# MDCBoard.net
KiCad netlist of a schematic drawn in EAGLE
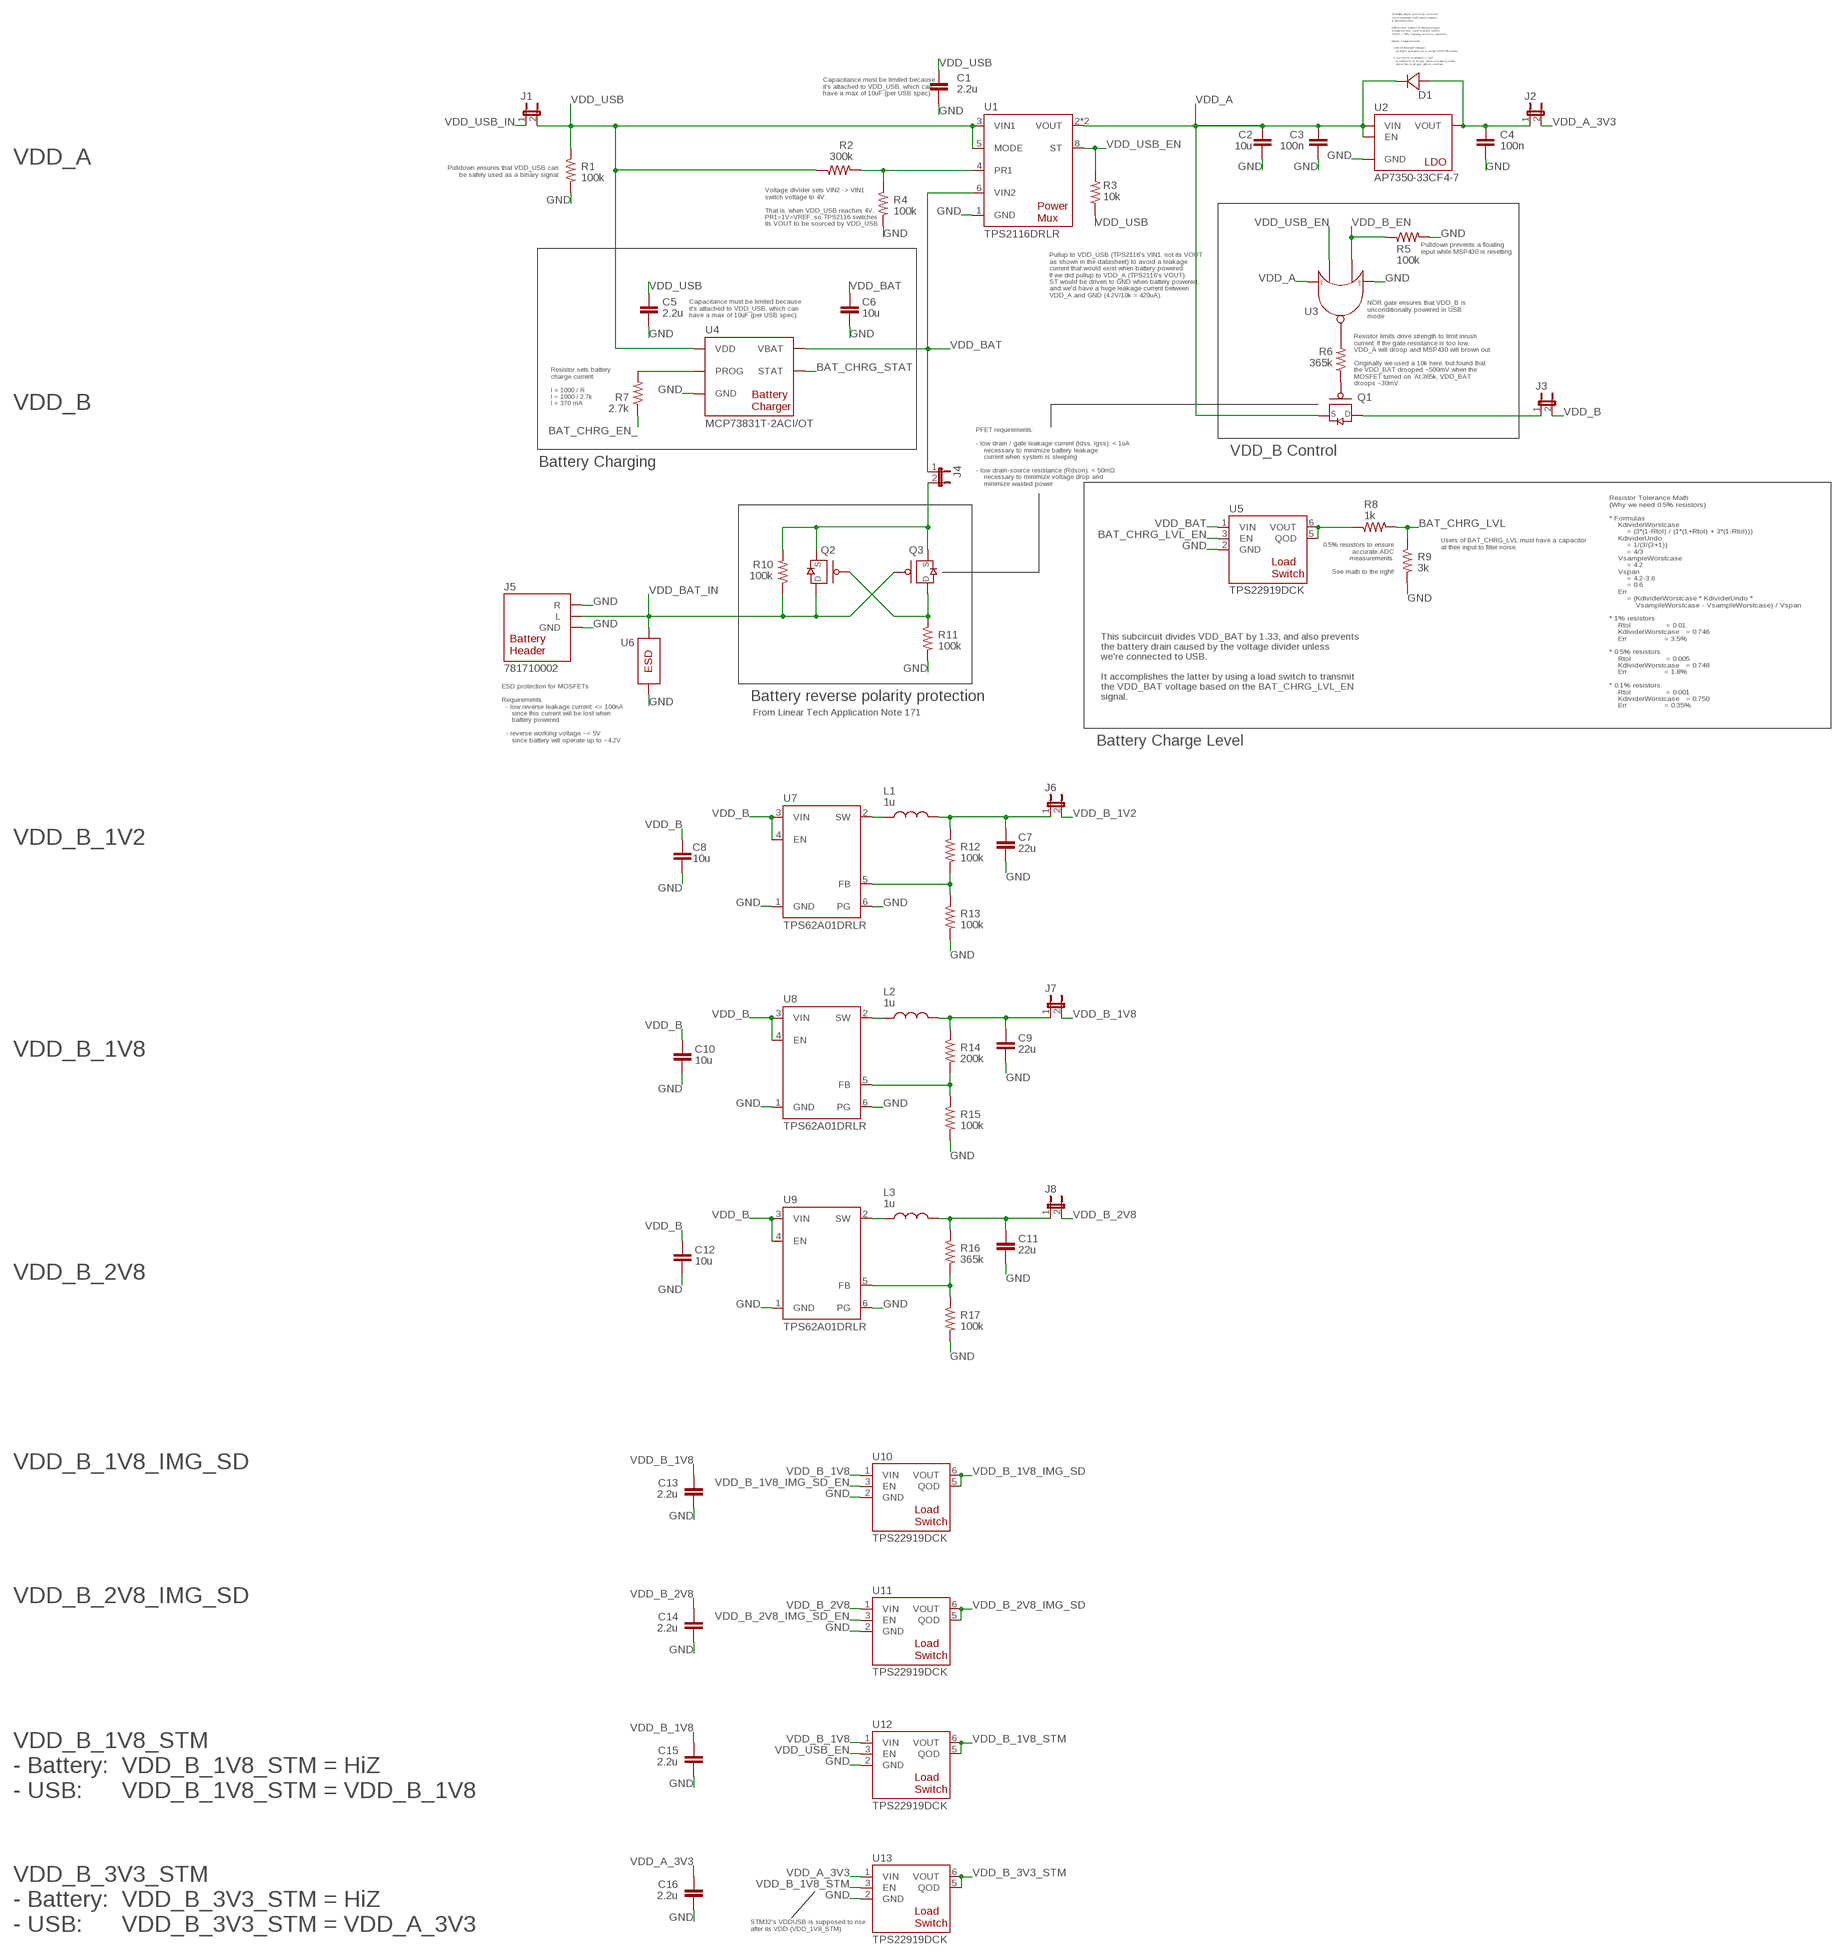
[diagram p0: schematic, sheet 1]
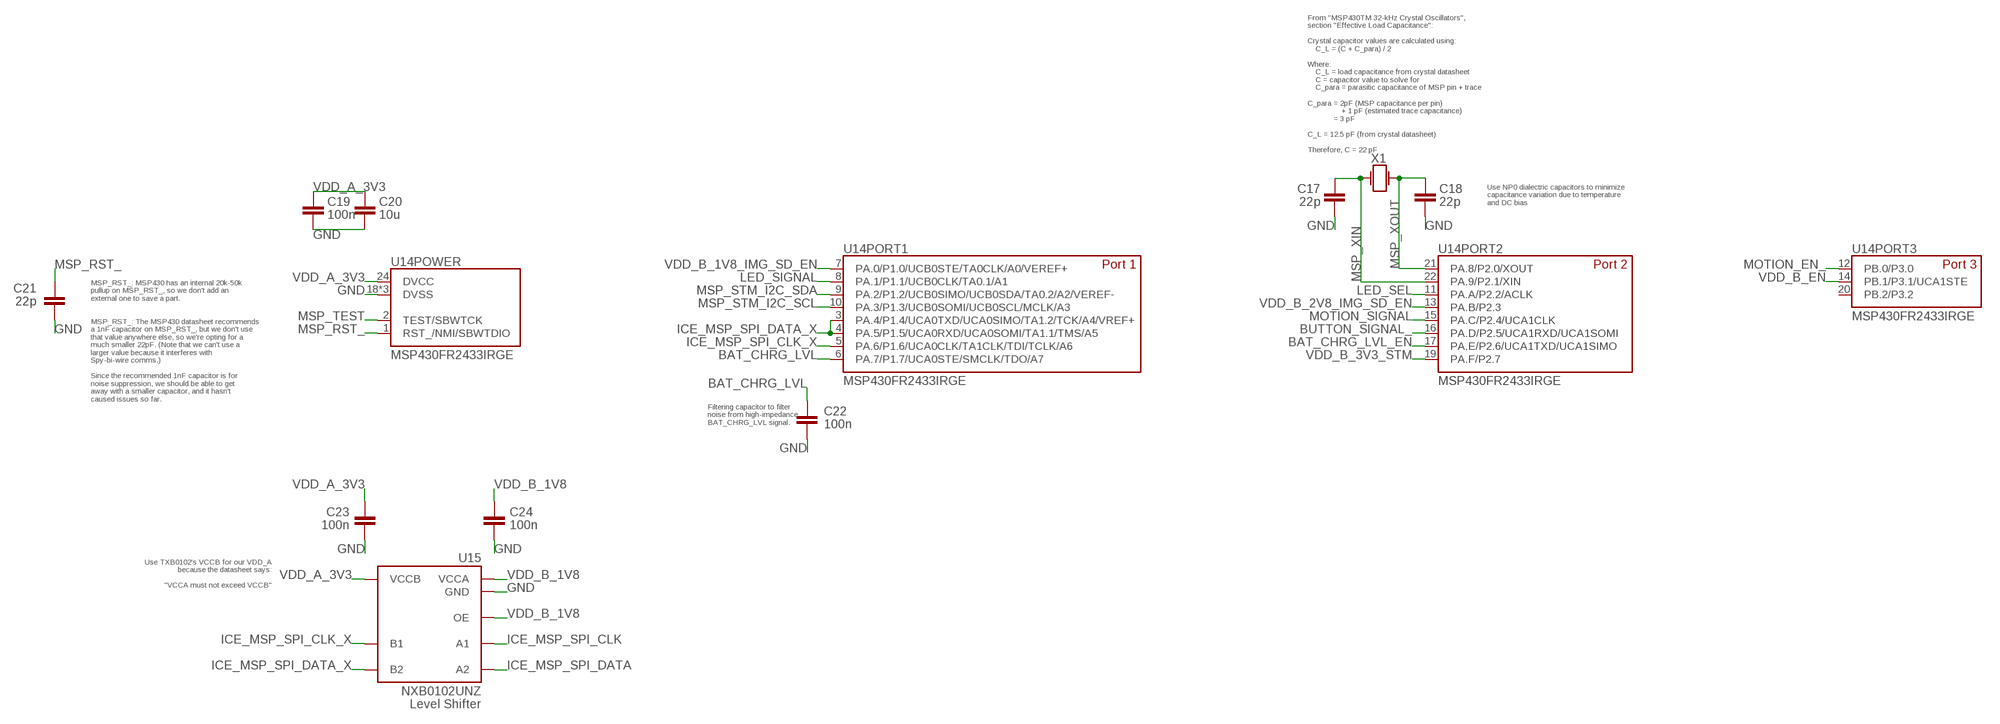
[diagram p1: schematic, sheet 2]
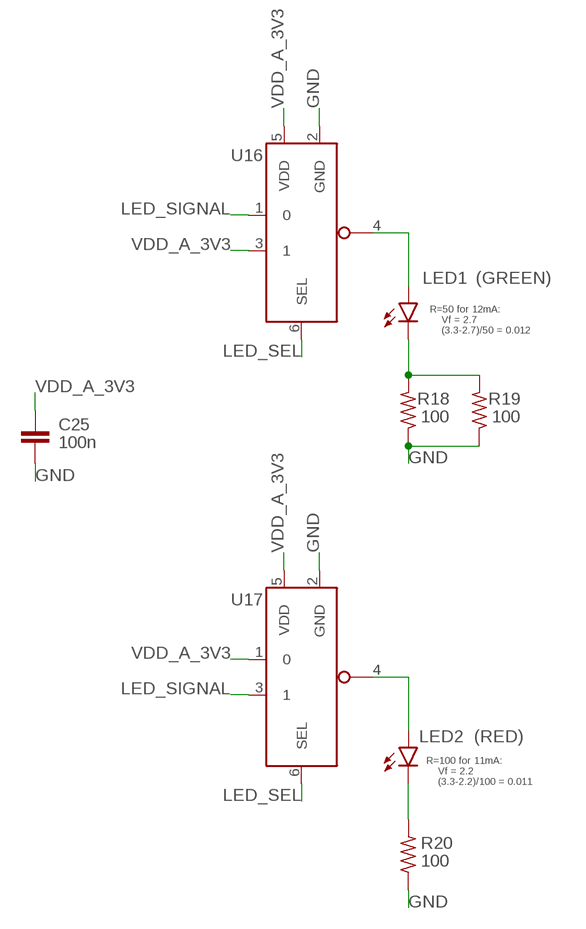
[diagram p2: schematic, sheet 3]
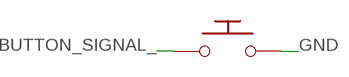
[diagram p3: schematic, sheet 4]
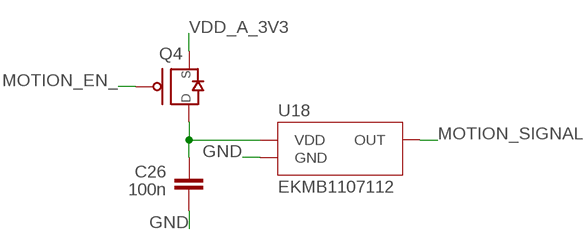
[diagram p4: schematic, sheet 5]
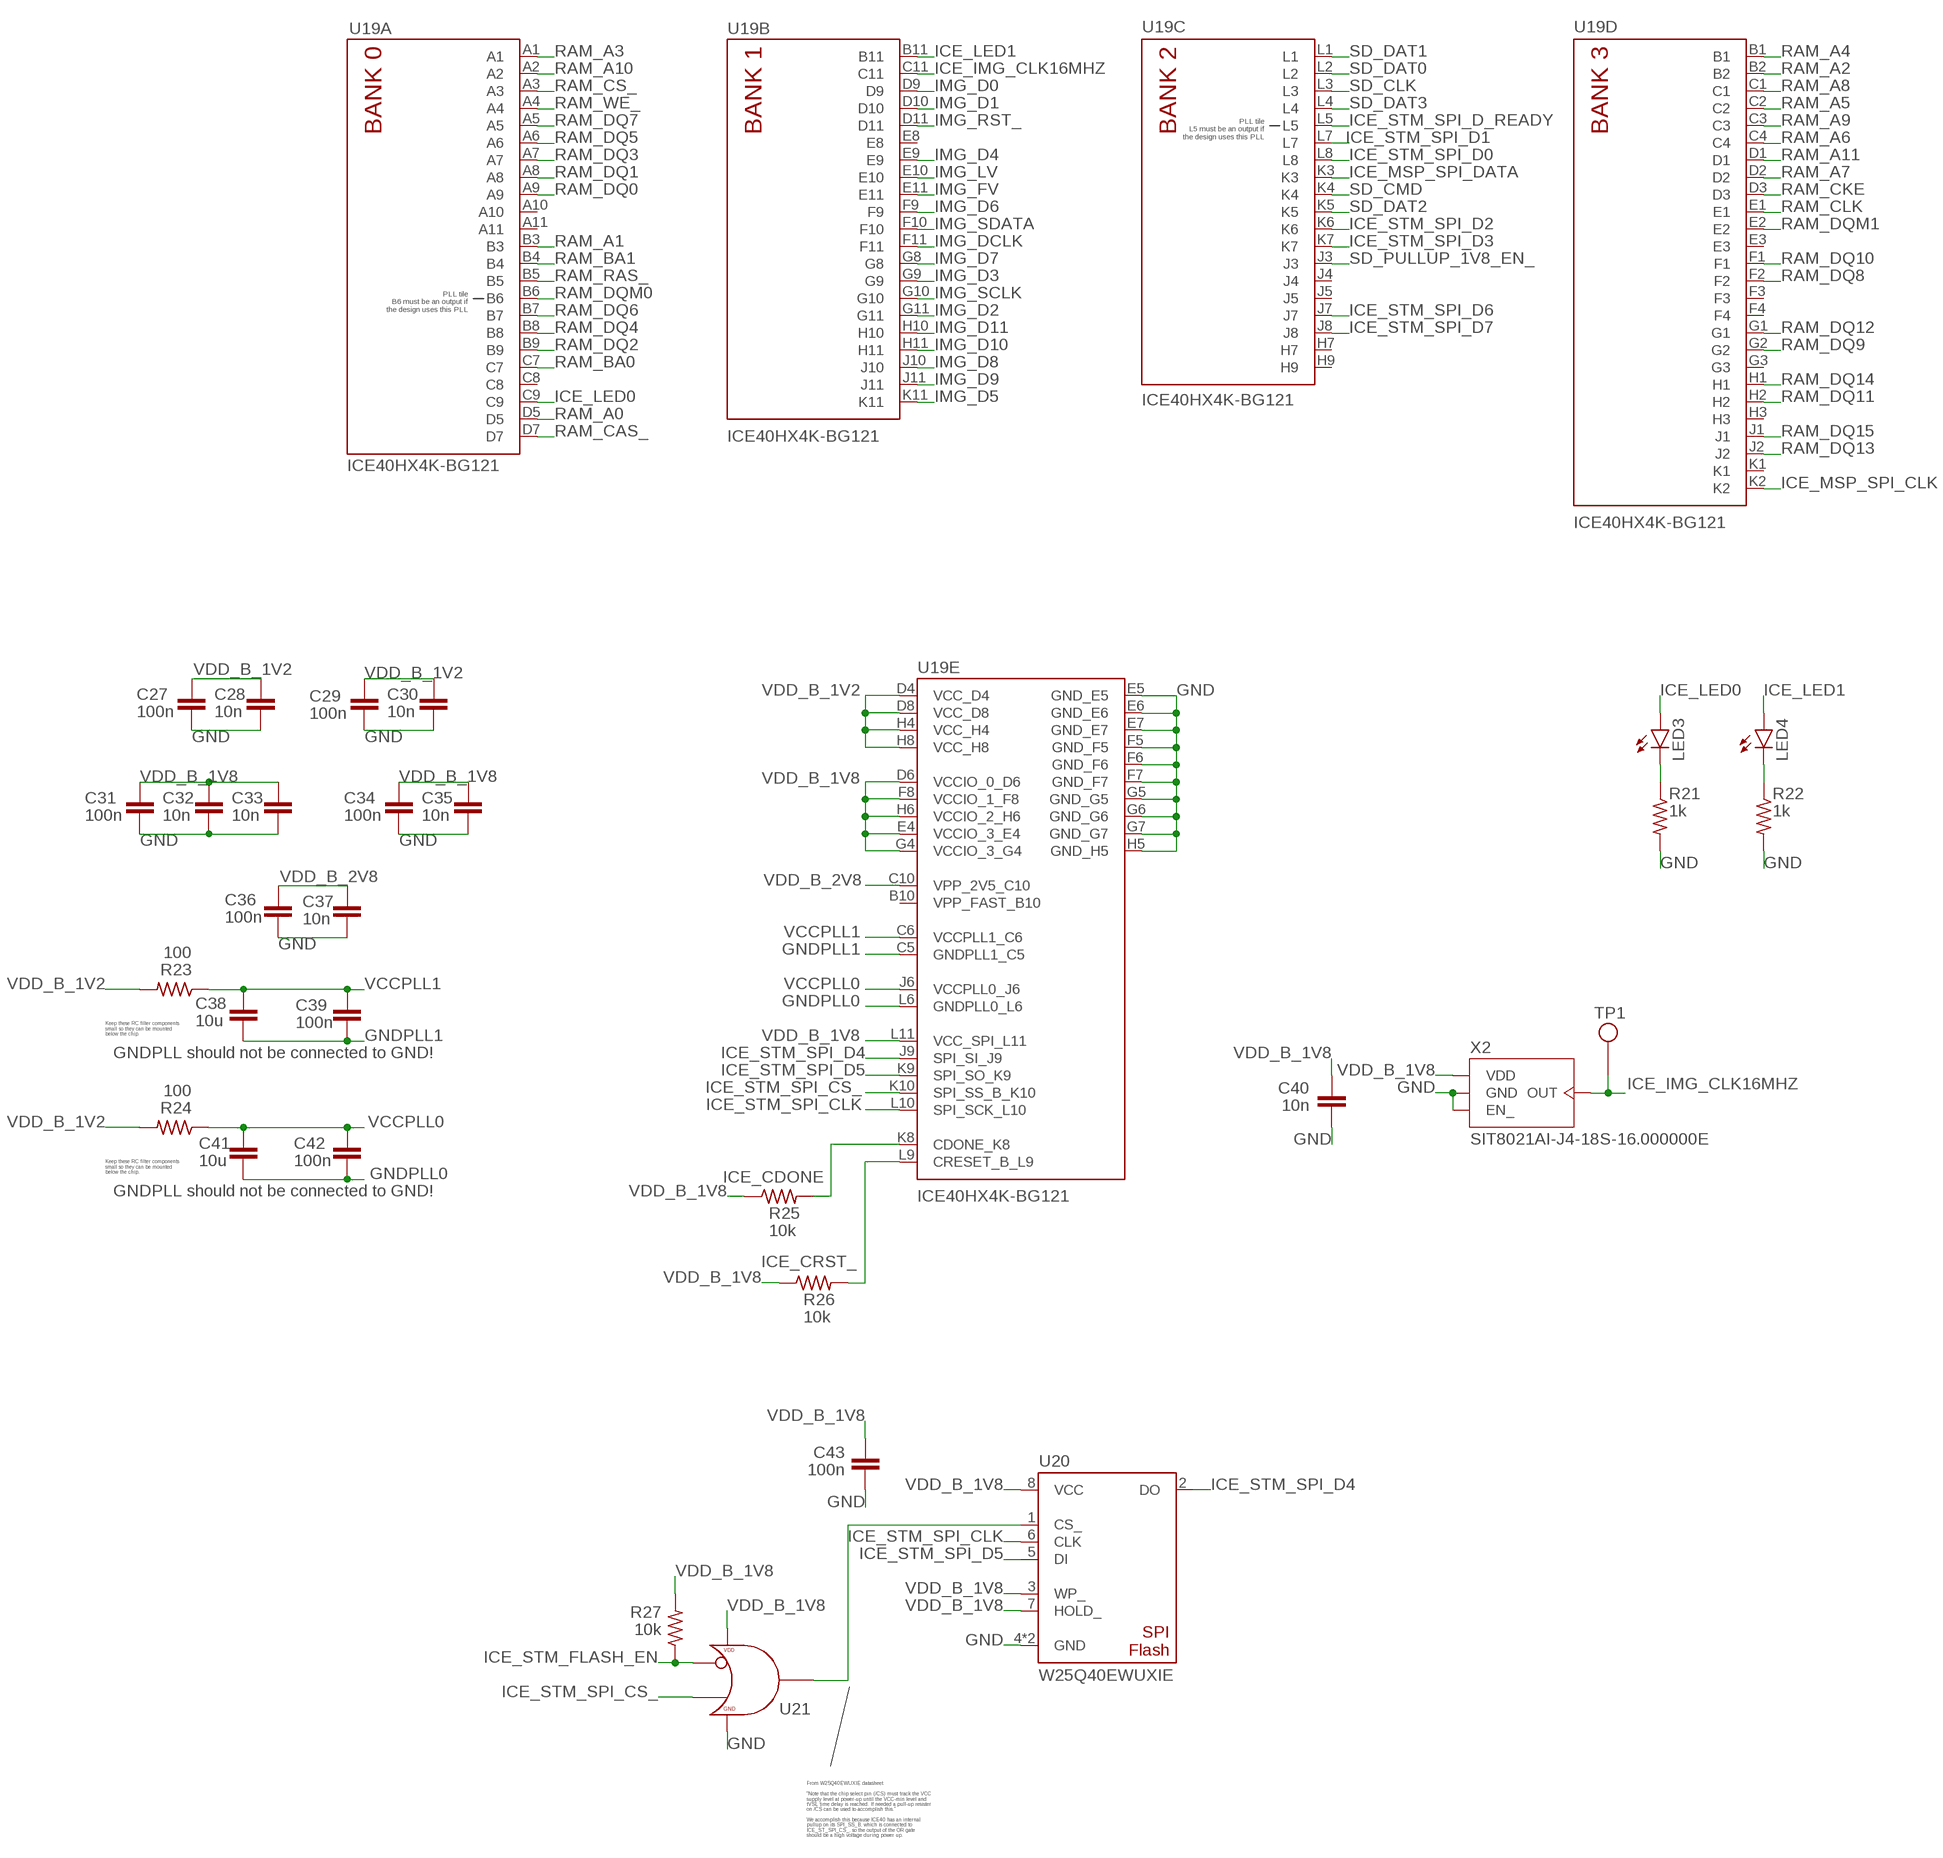
[diagram p5: schematic, sheet 6]
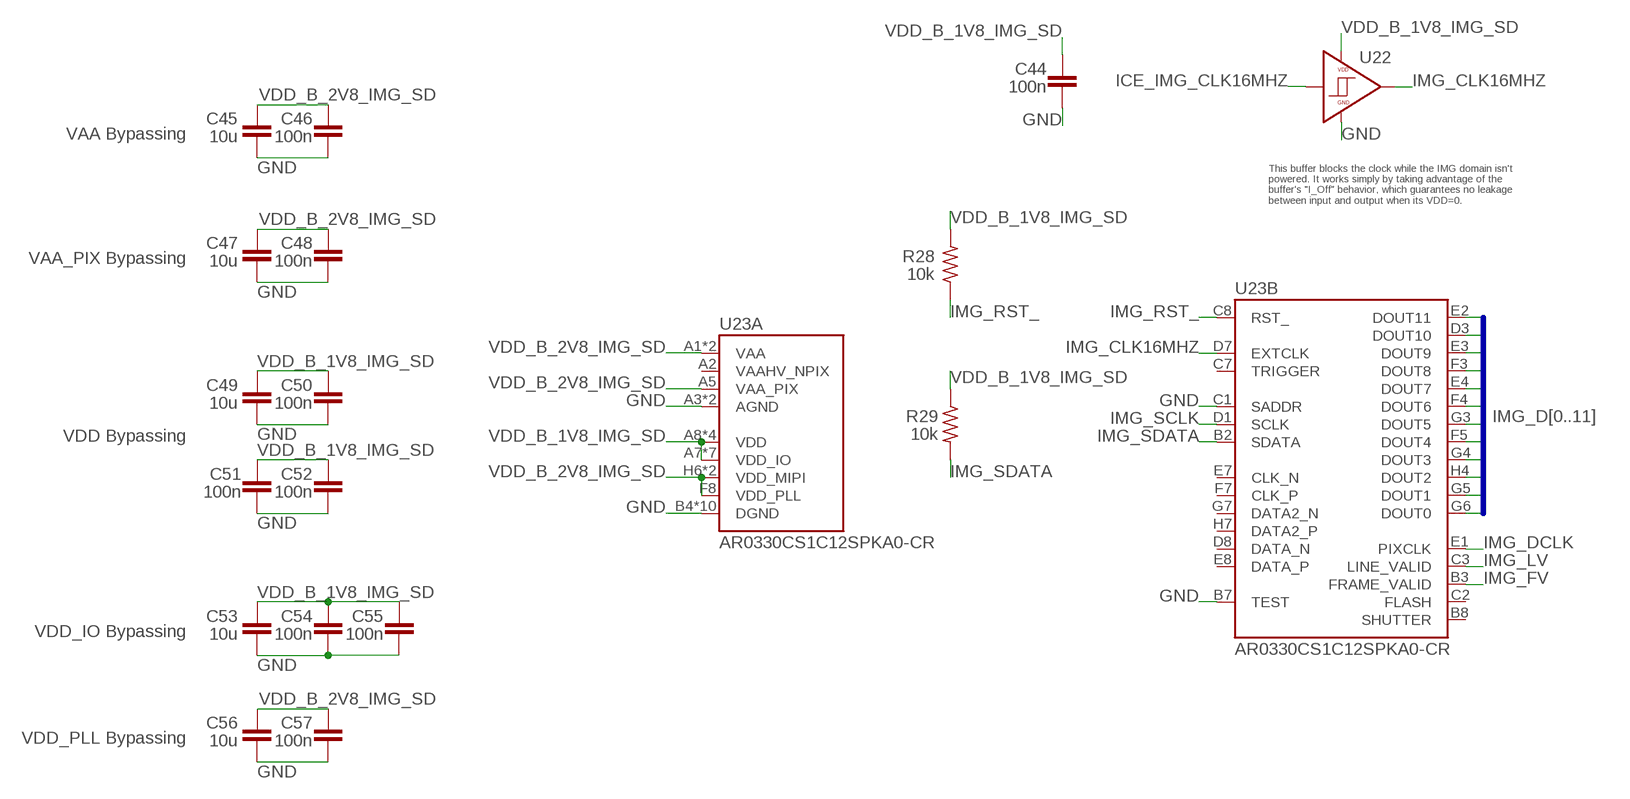
[diagram p6: schematic, sheet 7]
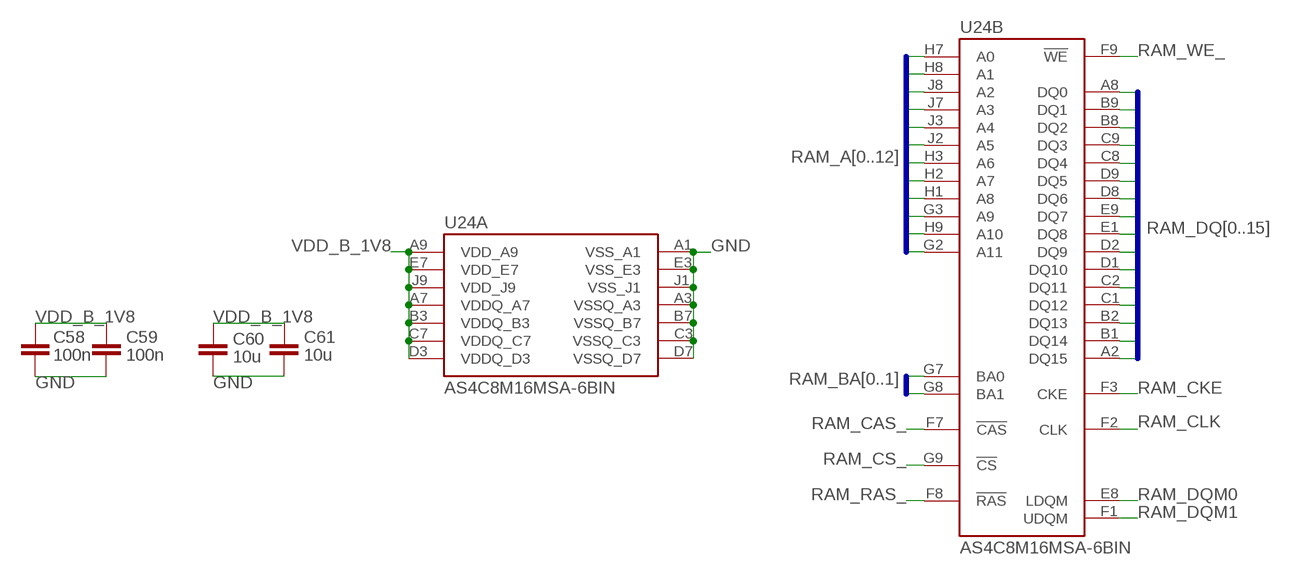
[diagram p7: schematic, sheet 8]
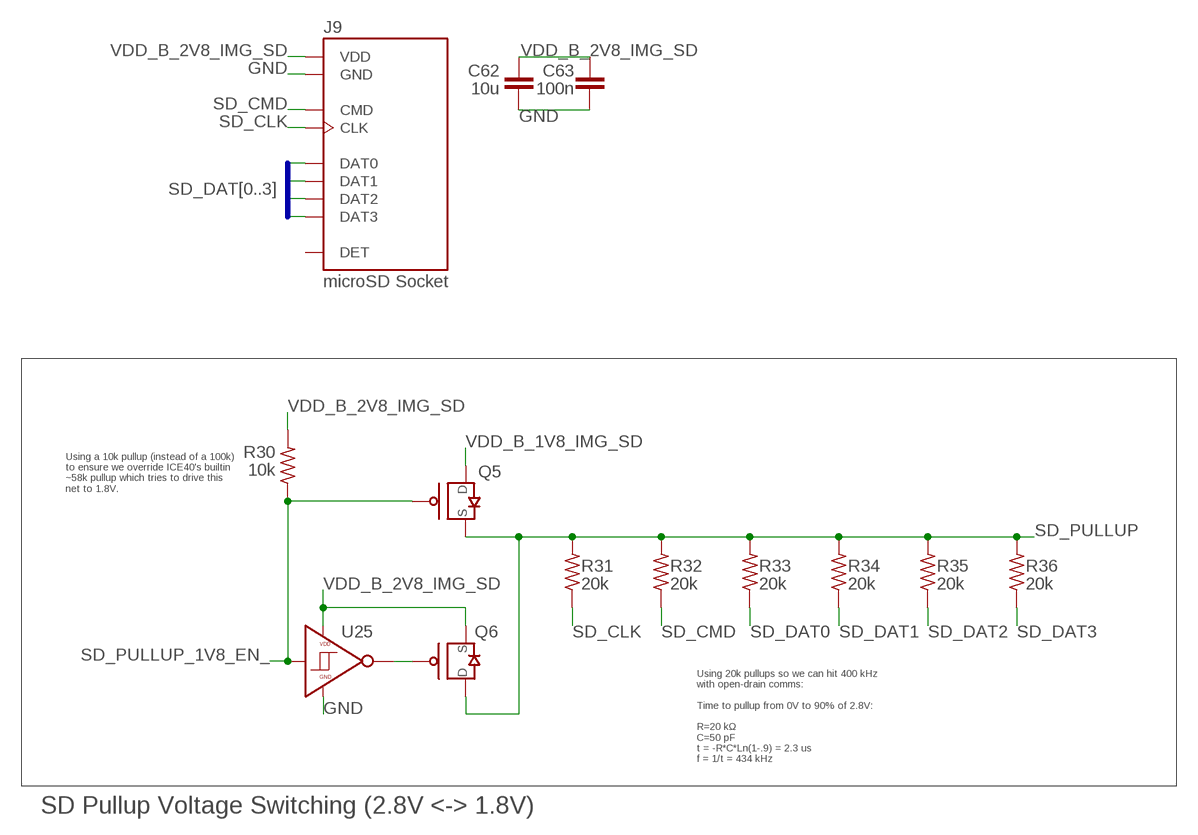
[diagram p8: schematic, sheet 9]
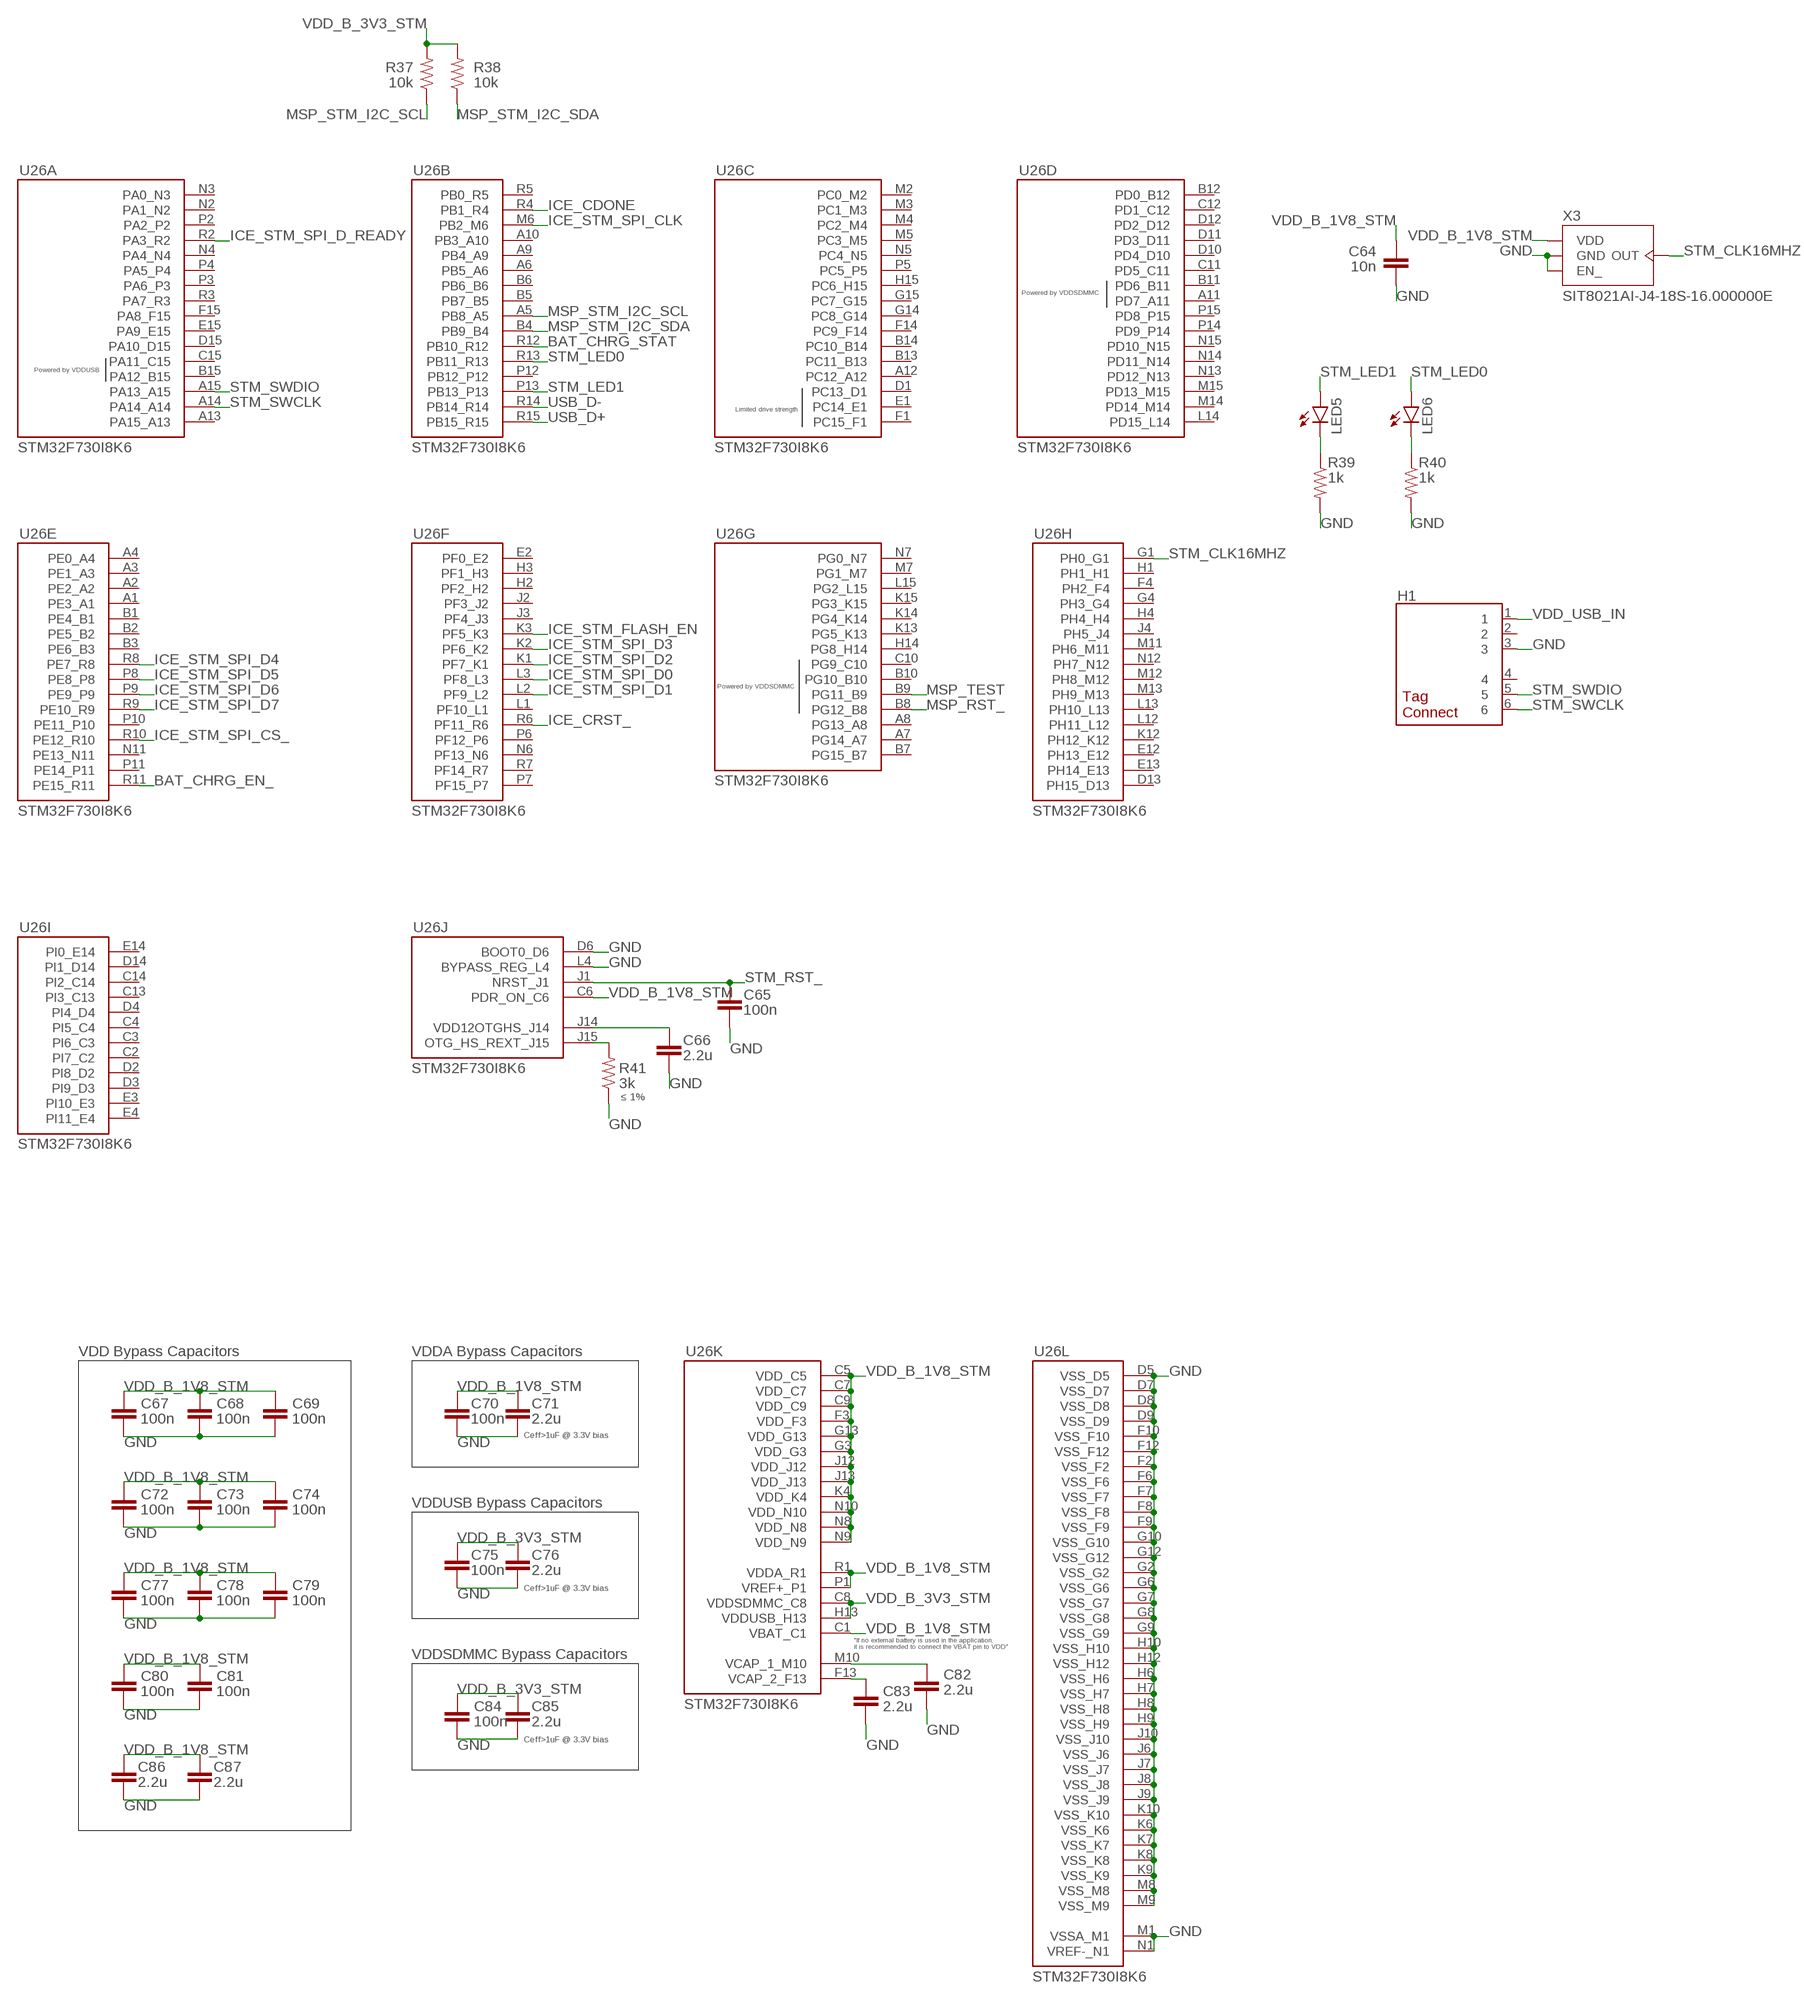
[diagram p9: schematic, sheet 10]
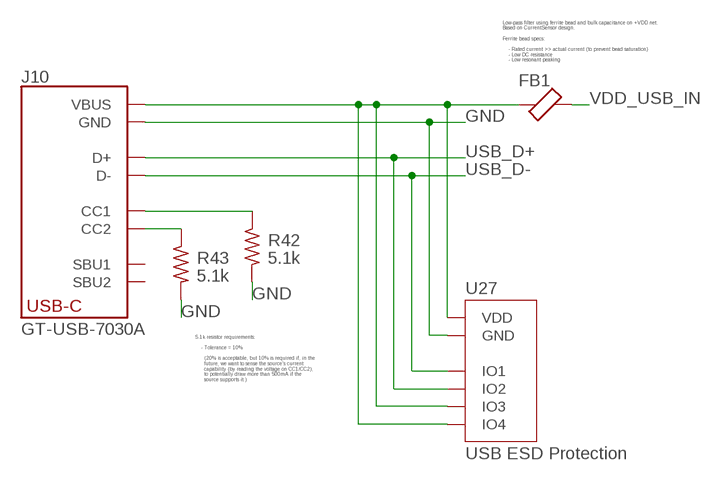
[diagram p10: schematic, sheet 11]
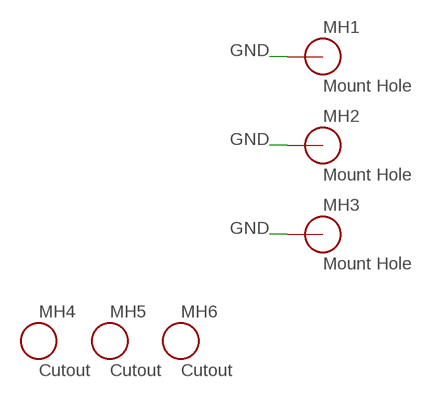
[diagram p11: schematic, sheet 12]

(export (version "E")
  (design (tool "Eeschema 10.0.6"))
  (components
    (comp (ref "C25")
      (value "100n")
      (footprint "eagle-import:0402")
      (fields (field (name "MFG") "Murata"))
      (libsource (lib "eagle-import") (part "CAPACITOR0402"))
    )
    (comp (ref "LED1")
      (value "LEDOSRAM-TOPLED-E1608")
      (footprint "eagle-import:OSRAM-TOPLED-E1608")
      (fields (field (name "MFG") "OSRAM"))
      (libsource (lib "eagle-import") (part "LEDOSRAM-TOPLED-E1608"))
    )
    (comp (ref "LED2")
      (value "LEDOSRAM-TOPLED-E1608")
      (footprint "eagle-import:OSRAM-TOPLED-E1608")
      (fields (field (name "MFG") "OSRAM"))
      (libsource (lib "eagle-import") (part "LEDOSRAM-TOPLED-E1608"))
    )
    (comp (ref "R18")
      (value "100")
      (footprint "eagle-import:0402")
      (fields (field (name "MFG") "Walsin"))
      (libsource (lib "eagle-import") (part "RESISTOR0402"))
    )
    (comp (ref "R19")
      (value "100")
      (footprint "eagle-import:0402")
      (fields (field (name "MFG") "Walsin"))
      (libsource (lib "eagle-import") (part "RESISTOR0402"))
    )
    (comp (ref "R20")
      (value "100")
      (footprint "eagle-import:0402")
      (fields (field (name "MFG") "Walsin"))
      (libsource (lib "eagle-import") (part "RESISTOR0402"))
    )
    (comp (ref "U16")
      (value "NEXPERIA-74LVC1G98-MUX-INV-OUTPUT")
      (footprint "eagle-import:NEXPERIA-SOT363")
      (fields (field (name "MFG") "Nexperia"))
      (libsource (lib "eagle-import") (part "NEXPERIA-74LVC1G98-MUX-INV-OUTPUT"))
    )
    (comp (ref "U17")
      (value "NEXPERIA-74LVC1G98-MUX-INV-OUTPUT")
      (footprint "eagle-import:NEXPERIA-SOT363")
      (fields (field (name "MFG") "Nexperia"))
      (libsource (lib "eagle-import") (part "NEXPERIA-74LVC1G98-MUX-INV-OUTPUT"))
    )
    (comp (ref "FB1")
      (value "FERRITE-BEAD0402")
      (footprint "eagle-import:0402")
      (fields (field (name "MFG") "Taiyo Yuden"))
      (libsource (lib "eagle-import") (part "FERRITE-BEAD0402"))
    )
    (comp (ref "J10")
      (value "USB-C-RECEPTACLE-GSWITCH-7030A")
      (footprint "eagle-import:GSWITCH-GT-USB-7030A")
      (fields (field (name "PN") "GT-USB-7030A") (field (name "MFG") "G-Switch"))
      (libsource (lib "eagle-import") (part "USB-C-RECEPTACLE-GSWITCH-7030A"))
    )
    (comp (ref "R42")
      (value "5.1k")
      (footprint "eagle-import:0402")
      (fields (field (name "MFG") "Yageo"))
      (libsource (lib "eagle-import") (part "RESISTOR0402"))
    )
    (comp (ref "R43")
      (value "5.1k")
      (footprint "eagle-import:0402")
      (fields (field (name "MFG") "Yageo"))
      (libsource (lib "eagle-import") (part "RESISTOR0402"))
    )
    (comp (ref "U27")
      (value "DIODESINC-DT1446-04V-7")
      (footprint "eagle-import:DIODESINC-DT1446-04V-7")
      (fields (field (name "MFG") "Diodes Incorporated"))
      (libsource (lib "eagle-import") (part "DIODESINC-DT1446-04V-7"))
    )
    (comp (ref "C64")
      (value "10n")
      (footprint "eagle-import:0402")
      (fields (field (name "MFG") "Samsung"))
      (libsource (lib "eagle-import") (part "CAPACITOR0402"))
    )
    (comp (ref "C65")
      (value "100n")
      (footprint "eagle-import:0402")
      (fields (field (name "MFG") "Murata"))
      (libsource (lib "eagle-import") (part "CAPACITOR0402"))
    )
    (comp (ref "C66")
      (value "2.2u")
      (footprint "eagle-import:0402")
      (fields (field (name "MFG") "Taiyo Yuden"))
      (libsource (lib "eagle-import") (part "CAPACITOR0402"))
    )
    (comp (ref "C67")
      (value "100n")
      (footprint "eagle-import:0402")
      (fields (field (name "MFG") "Murata"))
      (libsource (lib "eagle-import") (part "CAPACITOR0402"))
    )
    (comp (ref "C68")
      (value "100n")
      (footprint "eagle-import:0402")
      (fields (field (name "MFG") "Murata"))
      (libsource (lib "eagle-import") (part "CAPACITOR0402"))
    )
    (comp (ref "C69")
      (value "100n")
      (footprint "eagle-import:0402")
      (fields (field (name "MFG") "Murata"))
      (libsource (lib "eagle-import") (part "CAPACITOR0402"))
    )
    (comp (ref "C70")
      (value "100n")
      (footprint "eagle-import:0402")
      (fields (field (name "MFG") "Murata"))
      (libsource (lib "eagle-import") (part "CAPACITOR0402"))
    )
    (comp (ref "C71")
      (value "2.2u")
      (footprint "eagle-import:0402")
      (fields (field (name "MFG") "Taiyo Yuden"))
      (libsource (lib "eagle-import") (part "CAPACITOR0402"))
    )
    (comp (ref "C72")
      (value "100n")
      (footprint "eagle-import:0402")
      (fields (field (name "MFG") "Murata"))
      (libsource (lib "eagle-import") (part "CAPACITOR0402"))
    )
    (comp (ref "C73")
      (value "100n")
      (footprint "eagle-import:0402")
      (fields (field (name "MFG") "Murata"))
      (libsource (lib "eagle-import") (part "CAPACITOR0402"))
    )
    (comp (ref "C74")
      (value "100n")
      (footprint "eagle-import:0402")
      (fields (field (name "MFG") "Murata"))
      (libsource (lib "eagle-import") (part "CAPACITOR0402"))
    )
    (comp (ref "C75")
      (value "100n")
      (footprint "eagle-import:0402")
      (fields (field (name "MFG") "Murata"))
      (libsource (lib "eagle-import") (part "CAPACITOR0402"))
    )
    (comp (ref "C76")
      (value "2.2u")
      (footprint "eagle-import:0402")
      (fields (field (name "MFG") "Taiyo Yuden"))
      (libsource (lib "eagle-import") (part "CAPACITOR0402"))
    )
    (comp (ref "C77")
      (value "100n")
      (footprint "eagle-import:0402")
      (fields (field (name "MFG") "Murata"))
      (libsource (lib "eagle-import") (part "CAPACITOR0402"))
    )
    (comp (ref "C78")
      (value "100n")
      (footprint "eagle-import:0402")
      (fields (field (name "MFG") "Murata"))
      (libsource (lib "eagle-import") (part "CAPACITOR0402"))
    )
    (comp (ref "C79")
      (value "100n")
      (footprint "eagle-import:0402")
      (fields (field (name "MFG") "Murata"))
      (libsource (lib "eagle-import") (part "CAPACITOR0402"))
    )
    (comp (ref "C80")
      (value "100n")
      (footprint "eagle-import:0402")
      (fields (field (name "MFG") "Murata"))
      (libsource (lib "eagle-import") (part "CAPACITOR0402"))
    )
    (comp (ref "C81")
      (value "100n")
      (footprint "eagle-import:0402")
      (fields (field (name "MFG") "Murata"))
      (libsource (lib "eagle-import") (part "CAPACITOR0402"))
    )
    (comp (ref "C82")
      (value "2.2u")
      (footprint "eagle-import:0402")
      (fields (field (name "MFG") "Taiyo Yuden"))
      (libsource (lib "eagle-import") (part "CAPACITOR0402"))
    )
    (comp (ref "C83")
      (value "2.2u")
      (footprint "eagle-import:0402")
      (fields (field (name "MFG") "Taiyo Yuden"))
      (libsource (lib "eagle-import") (part "CAPACITOR0402"))
    )
    (comp (ref "C84")
      (value "100n")
      (footprint "eagle-import:0402")
      (fields (field (name "MFG") "Murata"))
      (libsource (lib "eagle-import") (part "CAPACITOR0402"))
    )
    (comp (ref "C85")
      (value "2.2u")
      (footprint "eagle-import:0402")
      (fields (field (name "MFG") "Taiyo Yuden"))
      (libsource (lib "eagle-import") (part "CAPACITOR0402"))
    )
    (comp (ref "C86")
      (value "2.2u")
      (footprint "eagle-import:0402")
      (fields (field (name "MFG") "Taiyo Yuden"))
      (libsource (lib "eagle-import") (part "CAPACITOR0402"))
    )
    (comp (ref "C87")
      (value "2.2u")
      (footprint "eagle-import:0402")
      (fields (field (name "MFG") "Taiyo Yuden"))
      (libsource (lib "eagle-import") (part "CAPACITOR0402"))
    )
    (comp (ref "H1")
      (value "TAGCONNECT-TC2030-NL")
      (footprint "eagle-import:TAGCONNECT-TC2030-NL")
      (libsource (lib "eagle-import") (part "TAGCONNECT-TC2030-NL"))
    )
    (comp (ref "LED5")
      (value "LEDLED-0603")
      (footprint "eagle-import:LED-0603")
      (fields (field (name "MFG") "OSRAM"))
      (libsource (lib "eagle-import") (part "LEDLED-0603"))
    )
    (comp (ref "LED6")
      (value "LEDLED-0603")
      (footprint "eagle-import:LED-0603")
      (fields (field (name "MFG") "OSRAM"))
      (libsource (lib "eagle-import") (part "LEDLED-0603"))
    )
    (comp (ref "R37")
      (value "10k")
      (footprint "eagle-import:0402")
      (fields (field (name "MFG") "Yageo"))
      (libsource (lib "eagle-import") (part "RESISTOR0402"))
    )
    (comp (ref "R38")
      (value "10k")
      (footprint "eagle-import:0402")
      (fields (field (name "MFG") "Yageo"))
      (libsource (lib "eagle-import") (part "RESISTOR0402"))
    )
    (comp (ref "R39")
      (value "1k")
      (footprint "eagle-import:0402")
      (fields (field (name "MFG") "Kamaya"))
      (libsource (lib "eagle-import") (part "RESISTOR0402"))
    )
    (comp (ref "R40")
      (value "1k")
      (footprint "eagle-import:0402")
      (fields (field (name "MFG") "Kamaya"))
      (libsource (lib "eagle-import") (part "RESISTOR0402"))
    )
    (comp (ref "R41")
      (value "3k")
      (footprint "eagle-import:0402")
      (fields (field (name "MFG") "Susumu"))
      (libsource (lib "eagle-import") (part "RESISTOR0402"))
    )
    (comp (ref "U26")
      (value "STM-STM32F730")
      (footprint "eagle-import:STM-STM32F730I8")
      (fields (field (name "MFG") "STMicroelectronics") (field (name "PN") "STM32F730I8K6"))
      (libsource (lib "eagle-import") (part "STM-STM32F730"))
    )
    (comp (ref "X3")
      (value "SITIME-SIT8021")
      (footprint "eagle-import:SITIME-SIT8021")
      (fields (field (name "MFG") "SiTime") (field (name "PN") "SIT8021AI-J4-18S-16.000000E"))
      (libsource (lib "eagle-import") (part "SITIME-SIT8021"))
    )
    (comp (ref "SW1")
      (value "TACTILE-SWITCH")
      (footprint "eagle-import:DEALON-TD-1624UR-180")
      (fields (field (name "MFG") "SHOU HAN"))
      (libsource (lib "eagle-import") (part "TACTILE-SWITCH"))
    )
    (comp (ref "C62")
      (value "10u")
      (footprint "eagle-import:0805")
      (fields (field (name "MFG") "Samsung"))
      (libsource (lib "eagle-import") (part "CAPACITOR0805"))
    )
    (comp (ref "C63")
      (value "100n")
      (footprint "eagle-import:0402")
      (fields (field (name "MFG") "Murata"))
      (libsource (lib "eagle-import") (part "CAPACITOR0402"))
    )
    (comp (ref "J9")
      (value "MICROSD-SOCKET")
      (footprint "eagle-import:MOLEX-1051620001")
      (fields (field (name "MFG") "Molex"))
      (libsource (lib "eagle-import") (part "MICROSD-SOCKET"))
    )
    (comp (ref "Q5")
      (value "DIODESINC-DMG2305UX")
      (footprint "eagle-import:DIODESINC-DMG2305UX")
      (fields (field (name "MFG") "Diodes Incorporated"))
      (libsource (lib "eagle-import") (part "DIODESINC-DMG2305UX"))
    )
    (comp (ref "Q6")
      (value "DIODESINC-DMG2305UX")
      (footprint "eagle-import:DIODESINC-DMG2305UX")
      (fields (field (name "MFG") "Diodes Incorporated"))
      (libsource (lib "eagle-import") (part "DIODESINC-DMG2305UX"))
    )
    (comp (ref "R30")
      (value "10k")
      (footprint "eagle-import:0402")
      (fields (field (name "MFG") "Yageo"))
      (libsource (lib "eagle-import") (part "RESISTOR0402"))
    )
    (comp (ref "R31")
      (value "20k")
      (footprint "eagle-import:0402")
      (fields (field (name "MFG") "Walsin"))
      (libsource (lib "eagle-import") (part "RESISTOR0402"))
    )
    (comp (ref "R32")
      (value "20k")
      (footprint "eagle-import:0402")
      (fields (field (name "MFG") "Walsin"))
      (libsource (lib "eagle-import") (part "RESISTOR0402"))
    )
    (comp (ref "R33")
      (value "20k")
      (footprint "eagle-import:0402")
      (fields (field (name "MFG") "Walsin"))
      (libsource (lib "eagle-import") (part "RESISTOR0402"))
    )
    (comp (ref "R34")
      (value "20k")
      (footprint "eagle-import:0402")
      (fields (field (name "MFG") "Walsin"))
      (libsource (lib "eagle-import") (part "RESISTOR0402"))
    )
    (comp (ref "R35")
      (value "20k")
      (footprint "eagle-import:0402")
      (fields (field (name "MFG") "Walsin"))
      (libsource (lib "eagle-import") (part "RESISTOR0402"))
    )
    (comp (ref "R36")
      (value "20k")
      (footprint "eagle-import:0402")
      (fields (field (name "MFG") "Walsin"))
      (libsource (lib "eagle-import") (part "RESISTOR0402"))
    )
    (comp (ref "U25")
      (value "NEXPERIA-74LVC1G98-INVERTER")
      (footprint "eagle-import:NEXPERIA-SOT363")
      (fields (field (name "MFG") "Nexperia"))
      (libsource (lib "eagle-import") (part "NEXPERIA-74LVC1G98-INVERTER"))
    )
    (comp (ref "C26")
      (value "100n")
      (footprint "eagle-import:0402")
      (fields (field (name "MFG") "Murata"))
      (libsource (lib "eagle-import") (part "CAPACITOR0402"))
    )
    (comp (ref "Q4")
      (value "DIODESINC-DMG2305UX")
      (footprint "eagle-import:DIODESINC-DMG2305UX")
      (fields (field (name "MFG") "Diodes Incorporated"))
      (libsource (lib "eagle-import") (part "DIODESINC-DMG2305UX"))
    )
    (comp (ref "U18")
      (value "PANASONIC-EKMB110711X")
      (footprint "eagle-import:PANASONIC-EKMB110711X")
      (fields (field (name "MFG") "Panasonic") (field (name "PN") "EKMB1107112"))
      (libsource (lib "eagle-import") (part "PANASONIC-EKMB110711X"))
    )
    (comp (ref "C58")
      (value "100n")
      (footprint "eagle-import:0402")
      (fields (field (name "MFG") "Murata"))
      (libsource (lib "eagle-import") (part "CAPACITOR0402"))
    )
    (comp (ref "C59")
      (value "100n")
      (footprint "eagle-import:0402")
      (fields (field (name "MFG") "Murata"))
      (libsource (lib "eagle-import") (part "CAPACITOR0402"))
    )
    (comp (ref "C60")
      (value "10u")
      (footprint "eagle-import:0805")
      (fields (field (name "MFG") "Samsung"))
      (libsource (lib "eagle-import") (part "CAPACITOR0805"))
    )
    (comp (ref "C61")
      (value "10u")
      (footprint "eagle-import:0805")
      (fields (field (name "MFG") "Samsung"))
      (libsource (lib "eagle-import") (part "CAPACITOR0805"))
    )
    (comp (ref "U24")
      (value "ALLIANCE-AS4C8M16MSA-6BIN")
      (footprint "eagle-import:ALLIANCE-AS4C8M16MSA-6BIN")
      (fields (field (name "PN") "AS4C8M16MSA-6BIN") (field (name "MFG") "Alliance Memory"))
      (libsource (lib "eagle-import") (part "ALLIANCE-AS4C8M16MSA-6BIN"))
    )
    (comp (ref "C1")
      (value "2.2u")
      (footprint "eagle-import:0402")
      (fields (field (name "MFG") "Taiyo Yuden"))
      (libsource (lib "eagle-import") (part "CAPACITOR0402"))
    )
    (comp (ref "C2")
      (value "10u")
      (footprint "eagle-import:0805")
      (fields (field (name "MFG") "Samsung"))
      (libsource (lib "eagle-import") (part "CAPACITOR0805"))
    )
    (comp (ref "C3")
      (value "100n")
      (footprint "eagle-import:0402")
      (fields (field (name "MFG") "Murata"))
      (libsource (lib "eagle-import") (part "CAPACITOR0402"))
    )
    (comp (ref "C4")
      (value "100n")
      (footprint "eagle-import:0402")
      (fields (field (name "MFG") "Murata"))
      (libsource (lib "eagle-import") (part "CAPACITOR0402"))
    )
    (comp (ref "C5")
      (value "2.2u")
      (footprint "eagle-import:0402")
      (fields (field (name "MFG") "Taiyo Yuden"))
      (libsource (lib "eagle-import") (part "CAPACITOR0402"))
    )
    (comp (ref "C6")
      (value "10u")
      (footprint "eagle-import:0805")
      (fields (field (name "MFG") "Samsung"))
      (libsource (lib "eagle-import") (part "CAPACITOR0805"))
    )
    (comp (ref "C7")
      (value "22u")
      (footprint "eagle-import:0805")
      (fields (field (name "MFG") "Samsung"))
      (libsource (lib "eagle-import") (part "CAPACITOR0805"))
    )
    (comp (ref "C8")
      (value "10u")
      (footprint "eagle-import:0805")
      (fields (field (name "MFG") "Samsung"))
      (libsource (lib "eagle-import") (part "CAPACITOR0805"))
    )
    (comp (ref "C9")
      (value "22u")
      (footprint "eagle-import:0805")
      (fields (field (name "MFG") "Samsung"))
      (libsource (lib "eagle-import") (part "CAPACITOR0805"))
    )
    (comp (ref "C10")
      (value "10u")
      (footprint "eagle-import:0805")
      (fields (field (name "MFG") "Samsung"))
      (libsource (lib "eagle-import") (part "CAPACITOR0805"))
    )
    (comp (ref "C11")
      (value "22u")
      (footprint "eagle-import:0805")
      (fields (field (name "MFG") "Samsung"))
      (libsource (lib "eagle-import") (part "CAPACITOR0805"))
    )
    (comp (ref "C12")
      (value "10u")
      (footprint "eagle-import:0805")
      (fields (field (name "MFG") "Samsung"))
      (libsource (lib "eagle-import") (part "CAPACITOR0805"))
    )
    (comp (ref "C13")
      (value "2.2u")
      (footprint "eagle-import:0402")
      (fields (field (name "MFG") "Taiyo Yuden"))
      (libsource (lib "eagle-import") (part "CAPACITOR0402"))
    )
    (comp (ref "C14")
      (value "2.2u")
      (footprint "eagle-import:0402")
      (fields (field (name "MFG") "Taiyo Yuden"))
      (libsource (lib "eagle-import") (part "CAPACITOR0402"))
    )
    (comp (ref "C15")
      (value "2.2u")
      (footprint "eagle-import:0402")
      (fields (field (name "MFG") "Taiyo Yuden"))
      (libsource (lib "eagle-import") (part "CAPACITOR0402"))
    )
    (comp (ref "C16")
      (value "2.2u")
      (footprint "eagle-import:0402")
      (fields (field (name "MFG") "Taiyo Yuden"))
      (libsource (lib "eagle-import") (part "CAPACITOR0402"))
    )
    (comp (ref "D1")
      (value "ROHM-RB168MM-40")
      (footprint "eagle-import:ROHM-SOD-123FL")
      (fields (field (name "MFG") "ROHM"))
      (libsource (lib "eagle-import") (part "ROHM-RB168MM-40"))
    )
    (comp (ref "J1")
      (value "JUMPER-SOLDER-CLOSED")
      (footprint "eagle-import:JUMPER-SOLDER-CLOSED")
      (libsource (lib "eagle-import") (part "JUMPER-SOLDER-CLOSED"))
    )
    (comp (ref "J2")
      (value "JUMPER-SOLDER-CLOSED")
      (footprint "eagle-import:JUMPER-SOLDER-CLOSED")
      (libsource (lib "eagle-import") (part "JUMPER-SOLDER-CLOSED"))
    )
    (comp (ref "J3")
      (value "JUMPER-SOLDER-CLOSED")
      (footprint "eagle-import:JUMPER-SOLDER-CLOSED")
      (libsource (lib "eagle-import") (part "JUMPER-SOLDER-CLOSED"))
    )
    (comp (ref "J4")
      (value "JUMPER-SOLDER-CLOSED")
      (footprint "eagle-import:JUMPER-SOLDER-CLOSED")
      (libsource (lib "eagle-import") (part "JUMPER-SOLDER-CLOSED"))
    )
    (comp (ref "J5")
      (value "BATTERY-HEADER-MOLEX-781710002")
      (footprint "eagle-import:MOLEX-781710002")
      (fields (field (name "PN") "781710002") (field (name "MFG") "Molex"))
      (libsource (lib "eagle-import") (part "BATTERY-HEADER-MOLEX-781710002"))
    )
    (comp (ref "J6")
      (value "JUMPER-SOLDER-CLOSED")
      (footprint "eagle-import:JUMPER-SOLDER-CLOSED")
      (libsource (lib "eagle-import") (part "JUMPER-SOLDER-CLOSED"))
    )
    (comp (ref "J7")
      (value "JUMPER-SOLDER-CLOSED")
      (footprint "eagle-import:JUMPER-SOLDER-CLOSED")
      (libsource (lib "eagle-import") (part "JUMPER-SOLDER-CLOSED"))
    )
    (comp (ref "J8")
      (value "JUMPER-SOLDER-CLOSED")
      (footprint "eagle-import:JUMPER-SOLDER-CLOSED")
      (libsource (lib "eagle-import") (part "JUMPER-SOLDER-CLOSED"))
    )
    (comp (ref "L1")
      (value "1u")
      (footprint "eagle-import:0806")
      (fields (field (name "MFG") "Samsung"))
      (libsource (lib "eagle-import") (part "INDUCTOR0806"))
    )
    (comp (ref "L2")
      (value "1u")
      (footprint "eagle-import:0806")
      (fields (field (name "MFG") "Samsung"))
      (libsource (lib "eagle-import") (part "INDUCTOR0806"))
    )
    (comp (ref "L3")
      (value "1u")
      (footprint "eagle-import:0806")
      (fields (field (name "MFG") "Samsung"))
      (libsource (lib "eagle-import") (part "INDUCTOR0806"))
    )
    (comp (ref "Q1")
      (value "PMOS-NEXPERIA-SOT1220")
      (footprint "eagle-import:NEXPERIA-SOT1220")
      (fields (field (name "MFG") "Nexperia"))
      (libsource (lib "eagle-import") (part "PMOS-NEXPERIA-SOT1220"))
    )
    (comp (ref "Q2")
      (value "PMOS-NEXPERIA-SOT1220")
      (footprint "eagle-import:NEXPERIA-SOT1220")
      (fields (field (name "MFG") "Nexperia"))
      (libsource (lib "eagle-import") (part "PMOS-NEXPERIA-SOT1220"))
    )
    (comp (ref "Q3")
      (value "PMOS-NEXPERIA-SOT1220")
      (footprint "eagle-import:NEXPERIA-SOT1220")
      (fields (field (name "MFG") "Nexperia"))
      (libsource (lib "eagle-import") (part "PMOS-NEXPERIA-SOT1220"))
    )
    (comp (ref "R1")
      (value "100k")
      (footprint "eagle-import:0402")
      (fields (field (name "MFG") "Yageo"))
      (libsource (lib "eagle-import") (part "RESISTOR0402"))
    )
    (comp (ref "R2")
      (value "300k")
      (footprint "eagle-import:0402")
      (fields (field (name "MFG") "Walsin"))
      (libsource (lib "eagle-import") (part "RESISTOR0402"))
    )
    (comp (ref "R3")
      (value "10k")
      (footprint "eagle-import:0402")
      (fields (field (name "MFG") "Yageo"))
      (libsource (lib "eagle-import") (part "RESISTOR0402"))
    )
    (comp (ref "R4")
      (value "100k")
      (footprint "eagle-import:0402")
      (fields (field (name "MFG") "Yageo"))
      (libsource (lib "eagle-import") (part "RESISTOR0402"))
    )
    (comp (ref "R5")
      (value "100k")
      (footprint "eagle-import:0402")
      (fields (field (name "MFG") "Yageo"))
      (libsource (lib "eagle-import") (part "RESISTOR0402"))
    )
    (comp (ref "R6")
      (value "365k")
      (footprint "eagle-import:0402")
      (fields (field (name "MFG") "Walsin"))
      (libsource (lib "eagle-import") (part "RESISTOR0402"))
    )
    (comp (ref "R7")
      (value "2.7k")
      (footprint "eagle-import:0402")
      (fields (field (name "MFG") "Bourns"))
      (libsource (lib "eagle-import") (part "RESISTOR0402"))
    )
    (comp (ref "R8")
      (value "1k")
      (footprint "eagle-import:0402")
      (fields (field (name "MFG") "Kamaya"))
      (libsource (lib "eagle-import") (part "RESISTOR0402"))
    )
    (comp (ref "R9")
      (value "3k")
      (footprint "eagle-import:0402")
      (fields (field (name "MFG") "Susumu"))
      (libsource (lib "eagle-import") (part "RESISTOR0402"))
    )
    (comp (ref "R10")
      (value "100k")
      (footprint "eagle-import:0402")
      (fields (field (name "MFG") "Yageo"))
      (libsource (lib "eagle-import") (part "RESISTOR0402"))
    )
    (comp (ref "R11")
      (value "100k")
      (footprint "eagle-import:0402")
      (fields (field (name "MFG") "Yageo"))
      (libsource (lib "eagle-import") (part "RESISTOR0402"))
    )
    (comp (ref "R12")
      (value "100k")
      (footprint "eagle-import:0402")
      (fields (field (name "MFG") "Yageo"))
      (libsource (lib "eagle-import") (part "RESISTOR0402"))
    )
    (comp (ref "R13")
      (value "100k")
      (footprint "eagle-import:0402")
      (fields (field (name "MFG") "Yageo"))
      (libsource (lib "eagle-import") (part "RESISTOR0402"))
    )
    (comp (ref "R14")
      (value "200k")
      (footprint "eagle-import:0402")
      (fields (field (name "MFG") "Yageo"))
      (libsource (lib "eagle-import") (part "RESISTOR0402"))
    )
    (comp (ref "R15")
      (value "100k")
      (footprint "eagle-import:0402")
      (fields (field (name "MFG") "Yageo"))
      (libsource (lib "eagle-import") (part "RESISTOR0402"))
    )
    (comp (ref "R16")
      (value "365k")
      (footprint "eagle-import:0402")
      (fields (field (name "MFG") "Walsin"))
      (libsource (lib "eagle-import") (part "RESISTOR0402"))
    )
    (comp (ref "R17")
      (value "100k")
      (footprint "eagle-import:0402")
      (fields (field (name "MFG") "Yageo"))
      (libsource (lib "eagle-import") (part "RESISTOR0402"))
    )
    (comp (ref "U1")
      (value "TI-TPS2116")
      (footprint "eagle-import:TI-TPS2116DRLR")
      (fields (field (name "MFG") "Texas Instruments") (field (name "PN") "TPS2116DRLR"))
      (libsource (lib "eagle-import") (part "TI-TPS2116"))
    )
    (comp (ref "U2")
      (value "DIODESINC-AP7350")
      (footprint "eagle-import:DIODESINC-AP7350")
      (fields (field (name "MFG") "Diodes Incorporated") (field (name "PN") "AP7350-33CF4-7"))
      (libsource (lib "eagle-import") (part "DIODESINC-AP7350"))
    )
    (comp (ref "U3")
      (value "NEXPERIA-74LVC1G98-NOR")
      (footprint "eagle-import:NEXPERIA-SOT363")
      (fields (field (name "MFG") "Nexperia"))
      (libsource (lib "eagle-import") (part "NEXPERIA-74LVC1G98-NOR"))
    )
    (comp (ref "U4")
      (value "MICROCHIP-MCP7383X")
      (footprint "eagle-import:MICROCHIP-MIC550X-SOT23-5")
      (fields (field (name "MFG") "Microchip") (field (name "PN") "MCP73831T-2ACI/OT"))
      (libsource (lib "eagle-import") (part "MICROCHIP-MCP7383X"))
    )
    (comp (ref "U5")
      (value "TI-TPS22919DCK")
      (footprint "eagle-import:TI-TPS22919DCK")
      (fields (field (name "PN") "TPS22919DCK") (field (name "MFG") "Texas Instruments"))
      (libsource (lib "eagle-import") (part "TI-TPS22919DCK"))
    )
    (comp (ref "U6")
      (value "EATON-STN101")
      (footprint "eagle-import:EATON-STN101")
      (fields (field (name "MFG") "Eaton"))
      (libsource (lib "eagle-import") (part "EATON-STN101"))
    )
    (comp (ref "U7")
      (value "TI-TPS62A01")
      (footprint "eagle-import:TI-TPS62A01DRLR")
      (fields (field (name "PN") "TPS62A01DRLR") (field (name "MFG") "Texas Instruments"))
      (libsource (lib "eagle-import") (part "TI-TPS62A01"))
    )
    (comp (ref "U8")
      (value "TI-TPS62A01")
      (footprint "eagle-import:TI-TPS62A01DRLR")
      (fields (field (name "PN") "TPS62A01DRLR") (field (name "MFG") "Texas Instruments"))
      (libsource (lib "eagle-import") (part "TI-TPS62A01"))
    )
    (comp (ref "U9")
      (value "TI-TPS62A01")
      (footprint "eagle-import:TI-TPS62A01DRLR")
      (fields (field (name "PN") "TPS62A01DRLR") (field (name "MFG") "Texas Instruments"))
      (libsource (lib "eagle-import") (part "TI-TPS62A01"))
    )
    (comp (ref "U10")
      (value "TI-TPS22919DCK")
      (footprint "eagle-import:TI-TPS22919DCK")
      (fields (field (name "PN") "TPS22919DCK") (field (name "MFG") "Texas Instruments"))
      (libsource (lib "eagle-import") (part "TI-TPS22919DCK"))
    )
    (comp (ref "U11")
      (value "TI-TPS22919DCK")
      (footprint "eagle-import:TI-TPS22919DCK")
      (fields (field (name "PN") "TPS22919DCK") (field (name "MFG") "Texas Instruments"))
      (libsource (lib "eagle-import") (part "TI-TPS22919DCK"))
    )
    (comp (ref "U12")
      (value "TI-TPS22919DCK")
      (footprint "eagle-import:TI-TPS22919DCK")
      (fields (field (name "PN") "TPS22919DCK") (field (name "MFG") "Texas Instruments"))
      (libsource (lib "eagle-import") (part "TI-TPS22919DCK"))
    )
    (comp (ref "U13")
      (value "TI-TPS22919DCK")
      (footprint "eagle-import:TI-TPS22919DCK")
      (fields (field (name "PN") "TPS22919DCK") (field (name "MFG") "Texas Instruments"))
      (libsource (lib "eagle-import") (part "TI-TPS22919DCK"))
    )
    (comp (ref "C27")
      (value "100n")
      (footprint "eagle-import:0402")
      (fields (field (name "MFG") "Murata"))
      (libsource (lib "eagle-import") (part "CAPACITOR0402"))
    )
    (comp (ref "C28")
      (value "10n")
      (footprint "eagle-import:0402")
      (fields (field (name "MFG") "Samsung"))
      (libsource (lib "eagle-import") (part "CAPACITOR0402"))
    )
    (comp (ref "C29")
      (value "100n")
      (footprint "eagle-import:0402")
      (fields (field (name "MFG") "Murata"))
      (libsource (lib "eagle-import") (part "CAPACITOR0402"))
    )
    (comp (ref "C30")
      (value "10n")
      (footprint "eagle-import:0402")
      (fields (field (name "MFG") "Samsung"))
      (libsource (lib "eagle-import") (part "CAPACITOR0402"))
    )
    (comp (ref "C31")
      (value "100n")
      (footprint "eagle-import:0402")
      (fields (field (name "MFG") "Murata"))
      (libsource (lib "eagle-import") (part "CAPACITOR0402"))
    )
    (comp (ref "C32")
      (value "10n")
      (footprint "eagle-import:0402")
      (fields (field (name "MFG") "Samsung"))
      (libsource (lib "eagle-import") (part "CAPACITOR0402"))
    )
    (comp (ref "C33")
      (value "10n")
      (footprint "eagle-import:0402")
      (fields (field (name "MFG") "Samsung"))
      (libsource (lib "eagle-import") (part "CAPACITOR0402"))
    )
    (comp (ref "C34")
      (value "100n")
      (footprint "eagle-import:0402")
      (fields (field (name "MFG") "Murata"))
      (libsource (lib "eagle-import") (part "CAPACITOR0402"))
    )
    (comp (ref "C35")
      (value "10n")
      (footprint "eagle-import:0402")
      (fields (field (name "MFG") "Samsung"))
      (libsource (lib "eagle-import") (part "CAPACITOR0402"))
    )
    (comp (ref "C36")
      (value "100n")
      (footprint "eagle-import:0402")
      (fields (field (name "MFG") "Murata"))
      (libsource (lib "eagle-import") (part "CAPACITOR0402"))
    )
    (comp (ref "C37")
      (value "10n")
      (footprint "eagle-import:0402")
      (fields (field (name "MFG") "Samsung"))
      (libsource (lib "eagle-import") (part "CAPACITOR0402"))
    )
    (comp (ref "C38")
      (value "10u")
      (footprint "eagle-import:0805")
      (fields (field (name "MFG") "Samsung"))
      (libsource (lib "eagle-import") (part "CAPACITOR0805"))
    )
    (comp (ref "C39")
      (value "100n")
      (footprint "eagle-import:0402")
      (fields (field (name "MFG") "Murata"))
      (libsource (lib "eagle-import") (part "CAPACITOR0402"))
    )
    (comp (ref "C40")
      (value "10n")
      (footprint "eagle-import:0402")
      (fields (field (name "MFG") "Samsung"))
      (libsource (lib "eagle-import") (part "CAPACITOR0402"))
    )
    (comp (ref "C41")
      (value "10u")
      (footprint "eagle-import:0805")
      (fields (field (name "MFG") "Samsung"))
      (libsource (lib "eagle-import") (part "CAPACITOR0805"))
    )
    (comp (ref "C42")
      (value "100n")
      (footprint "eagle-import:0402")
      (fields (field (name "MFG") "Murata"))
      (libsource (lib "eagle-import") (part "CAPACITOR0402"))
    )
    (comp (ref "C43")
      (value "100n")
      (footprint "eagle-import:0402")
      (fields (field (name "MFG") "Murata"))
      (libsource (lib "eagle-import") (part "CAPACITOR0402"))
    )
    (comp (ref "LED3")
      (value "LEDLED-0603")
      (footprint "eagle-import:LED-0603")
      (fields (field (name "MFG") "OSRAM"))
      (libsource (lib "eagle-import") (part "LEDLED-0603"))
    )
    (comp (ref "LED4")
      (value "LEDLED-0603")
      (footprint "eagle-import:LED-0603")
      (fields (field (name "MFG") "OSRAM"))
      (libsource (lib "eagle-import") (part "LEDLED-0603"))
    )
    (comp (ref "R21")
      (value "1k")
      (footprint "eagle-import:0402")
      (fields (field (name "MFG") "Kamaya"))
      (libsource (lib "eagle-import") (part "RESISTOR0402"))
    )
    (comp (ref "R22")
      (value "1k")
      (footprint "eagle-import:0402")
      (fields (field (name "MFG") "Kamaya"))
      (libsource (lib "eagle-import") (part "RESISTOR0402"))
    )
    (comp (ref "R23")
      (value "100")
      (footprint "eagle-import:0402")
      (fields (field (name "MFG") "Walsin"))
      (libsource (lib "eagle-import") (part "RESISTOR0402"))
    )
    (comp (ref "R24")
      (value "100")
      (footprint "eagle-import:0402")
      (fields (field (name "MFG") "Walsin"))
      (libsource (lib "eagle-import") (part "RESISTOR0402"))
    )
    (comp (ref "R25")
      (value "10k")
      (footprint "eagle-import:0402")
      (fields (field (name "MFG") "Yageo"))
      (libsource (lib "eagle-import") (part "RESISTOR0402"))
    )
    (comp (ref "R26")
      (value "10k")
      (footprint "eagle-import:0402")
      (fields (field (name "MFG") "Yageo"))
      (libsource (lib "eagle-import") (part "RESISTOR0402"))
    )
    (comp (ref "R27")
      (value "10k")
      (footprint "eagle-import:0402")
      (fields (field (name "MFG") "Yageo"))
      (libsource (lib "eagle-import") (part "RESISTOR0402"))
    )
    (comp (ref "TP1")
      (value "TEST-POINT")
      (footprint "eagle-import:TEST-POINT")
      (libsource (lib "eagle-import") (part "TEST-POINT"))
    )
    (comp (ref "U19")
      (value "LATTICE-ICE40HX4K-BG121")
      (footprint "eagle-import:LATTICE-ICE40HX4K-BG121")
      (fields (field (name "MFG") "Lattice"))
      (libsource (lib "eagle-import") (part "LATTICE-ICE40HX4K-BG121"))
    )
    (comp (ref "U20")
      (value "WINBOND-W25Q40EW")
      (footprint "eagle-import:WINBOND-W25Q40EWUXIE")
      (fields (field (name "MFG") "Winbond") (field (name "PN") "W25Q40EWUXIE"))
      (libsource (lib "eagle-import") (part "WINBOND-W25Q40EW"))
    )
    (comp (ref "U21")
      (value "NEXPERIA-74LVC1G98-OR-INV-INPUT")
      (footprint "eagle-import:NEXPERIA-SOT363")
      (fields (field (name "MFG") "Nexperia"))
      (libsource (lib "eagle-import") (part "NEXPERIA-74LVC1G98-OR-INV-INPUT"))
    )
    (comp (ref "X2")
      (value "SITIME-SIT8021")
      (footprint "eagle-import:SITIME-SIT8021")
      (fields (field (name "MFG") "SiTime") (field (name "PN") "SIT8021AI-J4-18S-16.000000E"))
      (libsource (lib "eagle-import") (part "SITIME-SIT8021"))
    )
    (comp (ref "C44")
      (value "100n")
      (footprint "eagle-import:0402")
      (fields (field (name "MFG") "Murata"))
      (libsource (lib "eagle-import") (part "CAPACITOR0402"))
    )
    (comp (ref "C45")
      (value "10u")
      (footprint "eagle-import:0805")
      (fields (field (name "MFG") "Samsung"))
      (libsource (lib "eagle-import") (part "CAPACITOR0805"))
    )
    (comp (ref "C46")
      (value "100n")
      (footprint "eagle-import:0402")
      (fields (field (name "MFG") "Murata"))
      (libsource (lib "eagle-import") (part "CAPACITOR0402"))
    )
    (comp (ref "C47")
      (value "10u")
      (footprint "eagle-import:0805")
      (fields (field (name "MFG") "Samsung"))
      (libsource (lib "eagle-import") (part "CAPACITOR0805"))
    )
    (comp (ref "C48")
      (value "100n")
      (footprint "eagle-import:0402")
      (fields (field (name "MFG") "Murata"))
      (libsource (lib "eagle-import") (part "CAPACITOR0402"))
    )
    (comp (ref "C49")
      (value "10u")
      (footprint "eagle-import:0805")
      (fields (field (name "MFG") "Samsung"))
      (libsource (lib "eagle-import") (part "CAPACITOR0805"))
    )
    (comp (ref "C50")
      (value "100n")
      (footprint "eagle-import:0402")
      (fields (field (name "MFG") "Murata"))
      (libsource (lib "eagle-import") (part "CAPACITOR0402"))
    )
    (comp (ref "C51")
      (value "100n")
      (footprint "eagle-import:0402")
      (fields (field (name "MFG") "Murata"))
      (libsource (lib "eagle-import") (part "CAPACITOR0402"))
    )
    (comp (ref "C52")
      (value "100n")
      (footprint "eagle-import:0402")
      (fields (field (name "MFG") "Murata"))
      (libsource (lib "eagle-import") (part "CAPACITOR0402"))
    )
    (comp (ref "C53")
      (value "10u")
      (footprint "eagle-import:0805")
      (fields (field (name "MFG") "Samsung"))
      (libsource (lib "eagle-import") (part "CAPACITOR0805"))
    )
    (comp (ref "C54")
      (value "100n")
      (footprint "eagle-import:0402")
      (fields (field (name "MFG") "Murata"))
      (libsource (lib "eagle-import") (part "CAPACITOR0402"))
    )
    (comp (ref "C55")
      (value "100n")
      (footprint "eagle-import:0402")
      (fields (field (name "MFG") "Murata"))
      (libsource (lib "eagle-import") (part "CAPACITOR0402"))
    )
    (comp (ref "C56")
      (value "10u")
      (footprint "eagle-import:0805")
      (fields (field (name "MFG") "Samsung"))
      (libsource (lib "eagle-import") (part "CAPACITOR0805"))
    )
    (comp (ref "C57")
      (value "100n")
      (footprint "eagle-import:0402")
      (fields (field (name "MFG") "Murata"))
      (libsource (lib "eagle-import") (part "CAPACITOR0402"))
    )
    (comp (ref "R28")
      (value "10k")
      (footprint "eagle-import:0402")
      (fields (field (name "MFG") "Yageo"))
      (libsource (lib "eagle-import") (part "RESISTOR0402"))
    )
    (comp (ref "R29")
      (value "10k")
      (footprint "eagle-import:0402")
      (fields (field (name "MFG") "Yageo"))
      (libsource (lib "eagle-import") (part "RESISTOR0402"))
    )
    (comp (ref "U22")
      (value "NEXPERIA-74LVC1G98-BUFFER")
      (footprint "eagle-import:NEXPERIA-SOT363")
      (fields (field (name "MFG") "Nexperia"))
      (libsource (lib "eagle-import") (part "NEXPERIA-74LVC1G98-BUFFER"))
    )
    (comp (ref "U23")
      (value "ON-AR0330CS1C12SPKA0")
      (footprint "eagle-import:ON-AR0330CS1C12SPKA0")
      (fields (field (name "MFG") "ON Semiconductor") (field (name "PN") "AR0330CS1C12SPKA0-CR"))
      (libsource (lib "eagle-import") (part "ON-AR0330CS1C12SPKA0"))
    )
    (comp (ref "C17")
      (value "22p")
      (footprint "eagle-import:0402")
      (fields (field (name "MFG") "Murata"))
      (libsource (lib "eagle-import") (part "CAPACITOR0402"))
    )
    (comp (ref "C18")
      (value "22p")
      (footprint "eagle-import:0402")
      (fields (field (name "MFG") "Murata"))
      (libsource (lib "eagle-import") (part "CAPACITOR0402"))
    )
    (comp (ref "C19")
      (value "100n")
      (footprint "eagle-import:0402")
      (fields (field (name "MFG") "Murata"))
      (libsource (lib "eagle-import") (part "CAPACITOR0402"))
    )
    (comp (ref "C20")
      (value "10u")
      (footprint "eagle-import:0805")
      (fields (field (name "MFG") "Samsung"))
      (libsource (lib "eagle-import") (part "CAPACITOR0805"))
    )
    (comp (ref "C21")
      (value "22p")
      (footprint "eagle-import:0402")
      (fields (field (name "MFG") "Murata"))
      (libsource (lib "eagle-import") (part "CAPACITOR0402"))
    )
    (comp (ref "C22")
      (value "100n")
      (footprint "eagle-import:0402")
      (fields (field (name "MFG") "Murata"))
      (libsource (lib "eagle-import") (part "CAPACITOR0402"))
    )
    (comp (ref "C23")
      (value "100n")
      (footprint "eagle-import:0402")
      (fields (field (name "MFG") "Murata"))
      (libsource (lib "eagle-import") (part "CAPACITOR0402"))
    )
    (comp (ref "C24")
      (value "100n")
      (footprint "eagle-import:0402")
      (fields (field (name "MFG") "Murata"))
      (libsource (lib "eagle-import") (part "CAPACITOR0402"))
    )
    (comp (ref "U14")
      (value "TI-MSP430FR2433IRGE")
      (footprint "eagle-import:TI-MSP430FR2433IRGE")
      (fields (field (name "MFG") "Texas Instruments"))
      (libsource (lib "eagle-import") (part "TI-MSP430FR2433IRGE"))
    )
    (comp (ref "U15")
      (value "NEXPERIA-NXB0102")
      (footprint "eagle-import:NEXPERIA-NXB0102UN")
      (fields
        (field (name "PN") "NXB0102UN")
        (field (name "MFG") "Nexperia")
        (field (name "PN_1") "NXB0102UNZ")
      )
      (libsource (lib "eagle-import") (part "NEXPERIA-NXB0102"))
    )
    (comp (ref "X1")
      (value "EPSON-FC-135")
      (footprint "eagle-import:EPSON-FC-135")
      (fields (field (name "MFG") "Epson") (field (name "PN") "Q13FC13500005"))
      (libsource (lib "eagle-import") (part "EPSON-FC-135"))
    )
    (comp (ref "MH1")
      (value "MDC-MOUNT-HOLE")
      (footprint "eagle-import:MDC-MOUNT-HOLE")
      (libsource (lib "eagle-import") (part "MDC-MOUNT-HOLE"))
    )
    (comp (ref "MH2")
      (value "MDC-MOUNT-HOLE")
      (footprint "eagle-import:MDC-MOUNT-HOLE")
      (libsource (lib "eagle-import") (part "MDC-MOUNT-HOLE"))
    )
    (comp (ref "MH3")
      (value "MDC-MOUNT-HOLE")
      (footprint "eagle-import:MDC-MOUNT-HOLE")
      (libsource (lib "eagle-import") (part "MDC-MOUNT-HOLE"))
    )
    (comp (ref "MH4")
      (value "MDC-CUTOUT-HALF")
      (footprint "eagle-import:MDC-CUTOUT-HALF")
      (libsource (lib "eagle-import") (part "MDC-CUTOUT-HALF"))
    )
    (comp (ref "MH5")
      (value "MDC-CUTOUT-HALF")
      (footprint "eagle-import:MDC-CUTOUT-HALF")
      (libsource (lib "eagle-import") (part "MDC-CUTOUT-HALF"))
    )
    (comp (ref "MH6")
      (value "MDC-CUTOUT-HALF")
      (footprint "eagle-import:MDC-CUTOUT-HALF")
      (libsource (lib "eagle-import") (part "MDC-CUTOUT-HALF"))
    )
  )
  (nets
    (net (code "7") (name "BAT_CHRG_EN_") (class "Default")
      (node (ref "R7") (pin "1") (pinfunction "1_1") (pintype "bidirectional"))
      (node (ref "U26") (pin "R11") (pinfunction "PE15_R11_R11") (pintype "bidirectional"))
    )
    (net (code "8") (name "BAT_CHRG_LVL") (class "Default")
      (node (ref "C22") (pin "1") (pinfunction "1_1") (pintype "bidirectional"))
      (node (ref "R8") (pin "2") (pinfunction "2_2") (pintype "bidirectional"))
      (node (ref "R9") (pin "1") (pinfunction "1_1") (pintype "bidirectional"))
      (node (ref "U14") (pin "6") (pinfunction "PA.7/P1.7/UCA0STE/SMCLK/TDO/A7_6") (pintype "bidirectional"))
    )
    (net (code "9") (name "BAT_CHRG_LVL_EN") (class "Default")
      (node (ref "U14") (pin "17") (pinfunction "PA.E/P2.6/UCA1TXD/UCA1SIMO_17") (pintype "bidirectional"))
      (node (ref "U5") (pin "3") (pinfunction "EN_3") (pintype "bidirectional"))
    )
    (net (code "10") (name "BAT_CHRG_STAT") (class "Default")
      (node (ref "U26") (pin "R12") (pinfunction "PB10_R12_R12") (pintype "bidirectional"))
      (node (ref "U4") (pin "1") (pinfunction "STAT_1") (pintype "bidirectional"))
    )
    (net (code "11") (name "BUTTON_SIGNAL_") (class "Default")
      (node (ref "SW1") (pin "1") (pinfunction "1_1") (pintype "bidirectional"))
      (node (ref "U14") (pin "16") (pinfunction "PA.D/P2.5/UCA1RXD/UCA1SOMI_16") (pintype "bidirectional"))
    )
    (net (code "12") (name "GND") (class "Default")
      (node (ref "C1") (pin "2") (pinfunction "2_2") (pintype "bidirectional"))
      (node (ref "C10") (pin "2") (pinfunction "2_2") (pintype "bidirectional"))
      (node (ref "C11") (pin "2") (pinfunction "2_2") (pintype "bidirectional"))
      (node (ref "C12") (pin "2") (pinfunction "2_2") (pintype "bidirectional"))
      (node (ref "C13") (pin "2") (pinfunction "2_2") (pintype "bidirectional"))
      (node (ref "C14") (pin "2") (pinfunction "2_2") (pintype "bidirectional"))
      (node (ref "C15") (pin "2") (pinfunction "2_2") (pintype "bidirectional"))
      (node (ref "C16") (pin "2") (pinfunction "2_2") (pintype "bidirectional"))
      (node (ref "C17") (pin "2") (pinfunction "2_2") (pintype "bidirectional"))
      (node (ref "C18") (pin "2") (pinfunction "2_2") (pintype "bidirectional"))
      (node (ref "C19") (pin "2") (pinfunction "2_2") (pintype "bidirectional"))
      (node (ref "C2") (pin "2") (pinfunction "2_2") (pintype "bidirectional"))
      (node (ref "C20") (pin "2") (pinfunction "2_2") (pintype "bidirectional"))
      (node (ref "C21") (pin "2") (pinfunction "2_2") (pintype "bidirectional"))
      (node (ref "C22") (pin "2") (pinfunction "2_2") (pintype "bidirectional"))
      (node (ref "C23") (pin "2") (pinfunction "2_2") (pintype "bidirectional"))
      (node (ref "C24") (pin "2") (pinfunction "2_2") (pintype "bidirectional"))
      (node (ref "C25") (pin "2") (pinfunction "2_2") (pintype "bidirectional"))
      (node (ref "C26") (pin "2") (pinfunction "2_2") (pintype "bidirectional"))
      (node (ref "C27") (pin "2") (pinfunction "2_2") (pintype "bidirectional"))
      (node (ref "C28") (pin "2") (pinfunction "2_2") (pintype "bidirectional"))
      (node (ref "C29") (pin "2") (pinfunction "2_2") (pintype "bidirectional"))
      (node (ref "C3") (pin "2") (pinfunction "2_2") (pintype "bidirectional"))
      (node (ref "C30") (pin "2") (pinfunction "2_2") (pintype "bidirectional"))
      (node (ref "C31") (pin "2") (pinfunction "2_2") (pintype "bidirectional"))
      (node (ref "C32") (pin "2") (pinfunction "2_2") (pintype "bidirectional"))
      (node (ref "C33") (pin "2") (pinfunction "2_2") (pintype "bidirectional"))
      (node (ref "C34") (pin "2") (pinfunction "2_2") (pintype "bidirectional"))
      (node (ref "C35") (pin "2") (pinfunction "2_2") (pintype "bidirectional"))
      (node (ref "C36") (pin "2") (pinfunction "2_2") (pintype "bidirectional"))
      (node (ref "C37") (pin "2") (pinfunction "2_2") (pintype "bidirectional"))
      (node (ref "C4") (pin "2") (pinfunction "2_2") (pintype "bidirectional"))
      (node (ref "C40") (pin "2") (pinfunction "2_2") (pintype "bidirectional"))
      (node (ref "C43") (pin "2") (pinfunction "2_2") (pintype "bidirectional"))
      (node (ref "C44") (pin "2") (pinfunction "2_2") (pintype "bidirectional"))
      (node (ref "C45") (pin "2") (pinfunction "2_2") (pintype "bidirectional"))
      (node (ref "C46") (pin "2") (pinfunction "2_2") (pintype "bidirectional"))
      (node (ref "C47") (pin "2") (pinfunction "2_2") (pintype "bidirectional"))
      (node (ref "C48") (pin "2") (pinfunction "2_2") (pintype "bidirectional"))
      (node (ref "C49") (pin "2") (pinfunction "2_2") (pintype "bidirectional"))
      (node (ref "C5") (pin "2") (pinfunction "2_2") (pintype "bidirectional"))
      (node (ref "C50") (pin "2") (pinfunction "2_2") (pintype "bidirectional"))
      (node (ref "C51") (pin "2") (pinfunction "2_2") (pintype "bidirectional"))
      (node (ref "C52") (pin "2") (pinfunction "2_2") (pintype "bidirectional"))
      (node (ref "C53") (pin "2") (pinfunction "2_2") (pintype "bidirectional"))
      (node (ref "C54") (pin "2") (pinfunction "2_2") (pintype "bidirectional"))
      (node (ref "C55") (pin "2") (pinfunction "2_2") (pintype "bidirectional"))
      (node (ref "C56") (pin "2") (pinfunction "2_2") (pintype "bidirectional"))
      (node (ref "C57") (pin "2") (pinfunction "2_2") (pintype "bidirectional"))
      (node (ref "C58") (pin "2") (pinfunction "2_2") (pintype "bidirectional"))
      (node (ref "C59") (pin "2") (pinfunction "2_2") (pintype "bidirectional"))
      (node (ref "C6") (pin "2") (pinfunction "2_2") (pintype "bidirectional"))
      (node (ref "C60") (pin "2") (pinfunction "2_2") (pintype "bidirectional"))
      (node (ref "C61") (pin "2") (pinfunction "2_2") (pintype "bidirectional"))
      (node (ref "C62") (pin "2") (pinfunction "2_2") (pintype "bidirectional"))
      (node (ref "C63") (pin "2") (pinfunction "2_2") (pintype "bidirectional"))
      (node (ref "C64") (pin "2") (pinfunction "2_2") (pintype "bidirectional"))
      (node (ref "C65") (pin "2") (pinfunction "2_2") (pintype "bidirectional"))
      (node (ref "C66") (pin "2") (pinfunction "2_2") (pintype "bidirectional"))
      (node (ref "C67") (pin "2") (pinfunction "2_2") (pintype "bidirectional"))
      (node (ref "C68") (pin "2") (pinfunction "2_2") (pintype "bidirectional"))
      (node (ref "C69") (pin "2") (pinfunction "2_2") (pintype "bidirectional"))
      (node (ref "C7") (pin "2") (pinfunction "2_2") (pintype "bidirectional"))
      (node (ref "C70") (pin "2") (pinfunction "2_2") (pintype "bidirectional"))
      (node (ref "C71") (pin "2") (pinfunction "2_2") (pintype "bidirectional"))
      (node (ref "C72") (pin "2") (pinfunction "2_2") (pintype "bidirectional"))
      (node (ref "C73") (pin "2") (pinfunction "2_2") (pintype "bidirectional"))
      (node (ref "C74") (pin "2") (pinfunction "2_2") (pintype "bidirectional"))
      (node (ref "C75") (pin "2") (pinfunction "2_2") (pintype "bidirectional"))
      (node (ref "C76") (pin "2") (pinfunction "2_2") (pintype "bidirectional"))
      (node (ref "C77") (pin "2") (pinfunction "2_2") (pintype "bidirectional"))
      (node (ref "C78") (pin "2") (pinfunction "2_2") (pintype "bidirectional"))
      (node (ref "C79") (pin "2") (pinfunction "2_2") (pintype "bidirectional"))
      (node (ref "C8") (pin "2") (pinfunction "2_2") (pintype "bidirectional"))
      (node (ref "C80") (pin "2") (pinfunction "2_2") (pintype "bidirectional"))
      (node (ref "C81") (pin "2") (pinfunction "2_2") (pintype "bidirectional"))
      (node (ref "C82") (pin "2") (pinfunction "2_2") (pintype "bidirectional"))
      (node (ref "C83") (pin "2") (pinfunction "2_2") (pintype "bidirectional"))
      (node (ref "C84") (pin "2") (pinfunction "2_2") (pintype "bidirectional"))
      (node (ref "C85") (pin "2") (pinfunction "2_2") (pintype "bidirectional"))
      (node (ref "C86") (pin "2") (pinfunction "2_2") (pintype "bidirectional"))
      (node (ref "C87") (pin "2") (pinfunction "2_2") (pintype "bidirectional"))
      (node (ref "C9") (pin "2") (pinfunction "2_2") (pintype "bidirectional"))
      (node (ref "H1") (pin "3") (pinfunction "3_3") (pintype "bidirectional"))
      (node (ref "J10") (pin "A12B1") (pinfunction "GND_A12B1") (pintype "bidirectional"))
      (node (ref "J10") (pin "B12A1") (pinfunction "GND_B12A1") (pintype "bidirectional"))
      (node (ref "J10") (pin "GND1") (pinfunction "GND_GND1") (pintype "bidirectional"))
      (node (ref "J10") (pin "GND2") (pinfunction "GND_GND2") (pintype "bidirectional"))
      (node (ref "J10") (pin "GND3") (pinfunction "GND_GND3") (pintype "bidirectional"))
      (node (ref "J10") (pin "GND4") (pinfunction "GND_GND4") (pintype "bidirectional"))
      (node (ref "J5") (pin "2") (pinfunction "R_2") (pintype "bidirectional"))
      (node (ref "J5") (pin "3") (pinfunction "GND_3") (pintype "bidirectional"))
      (node (ref "J5") (pin "4") (pinfunction "GND_4") (pintype "bidirectional"))
      (node (ref "J9") (pin "GND1") (pinfunction "GND_GND1") (pintype "bidirectional"))
      (node (ref "J9") (pin "GND2") (pinfunction "GND_GND2") (pintype "bidirectional"))
      (node (ref "J9") (pin "GND3") (pinfunction "GND_GND3") (pintype "bidirectional"))
      (node (ref "J9") (pin "GND4") (pinfunction "GND_GND4") (pintype "bidirectional"))
      (node (ref "J9") (pin "VSS") (pinfunction "GND_VSS") (pintype "bidirectional"))
      (node (ref "MH1") (pin "1") (pinfunction "1_1") (pintype "bidirectional"))
      (node (ref "MH2") (pin "1") (pinfunction "1_1") (pintype "bidirectional"))
      (node (ref "MH3") (pin "1") (pinfunction "1_1") (pintype "bidirectional"))
      (node (ref "R1") (pin "2") (pinfunction "2_2") (pintype "bidirectional"))
      (node (ref "R11") (pin "2") (pinfunction "2_2") (pintype "bidirectional"))
      (node (ref "R13") (pin "2") (pinfunction "2_2") (pintype "bidirectional"))
      (node (ref "R15") (pin "2") (pinfunction "2_2") (pintype "bidirectional"))
      (node (ref "R17") (pin "2") (pinfunction "2_2") (pintype "bidirectional"))
      (node (ref "R18") (pin "1") (pinfunction "1_1") (pintype "bidirectional"))
      (node (ref "R19") (pin "1") (pinfunction "1_1") (pintype "bidirectional"))
      (node (ref "R20") (pin "1") (pinfunction "1_1") (pintype "bidirectional"))
      (node (ref "R21") (pin "2") (pinfunction "2_2") (pintype "bidirectional"))
      (node (ref "R22") (pin "2") (pinfunction "2_2") (pintype "bidirectional"))
      (node (ref "R39") (pin "2") (pinfunction "2_2") (pintype "bidirectional"))
      (node (ref "R4") (pin "2") (pinfunction "2_2") (pintype "bidirectional"))
      (node (ref "R40") (pin "2") (pinfunction "2_2") (pintype "bidirectional"))
      (node (ref "R41") (pin "1") (pinfunction "1_1") (pintype "bidirectional"))
      (node (ref "R42") (pin "2") (pinfunction "2_2") (pintype "bidirectional"))
      (node (ref "R43") (pin "2") (pinfunction "2_2") (pintype "bidirectional"))
      (node (ref "R5") (pin "2") (pinfunction "2_2") (pintype "bidirectional"))
      (node (ref "R9") (pin "2") (pinfunction "2_2") (pintype "bidirectional"))
      (node (ref "SW1") (pin "2") (pinfunction "2_2") (pintype "bidirectional"))
      (node (ref "U1") (pin "1") (pinfunction "GND_1") (pintype "bidirectional"))
      (node (ref "U10") (pin "2") (pinfunction "GND_2") (pintype "bidirectional"))
      (node (ref "U11") (pin "2") (pinfunction "GND_2") (pintype "bidirectional"))
      (node (ref "U12") (pin "2") (pinfunction "GND_2") (pintype "bidirectional"))
      (node (ref "U13") (pin "2") (pinfunction "GND_2") (pintype "bidirectional"))
      (node (ref "U14") (pin "18") (pinfunction "DVSS_18") (pintype "bidirectional"))
      (node (ref "U14") (pin "23") (pinfunction "DVSS_23") (pintype "bidirectional"))
      (node (ref "U14") (pin "25") (pinfunction "DVSS_25") (pintype "bidirectional"))
      (node (ref "U15") (pin "B1") (pinfunction "GND_B1") (pintype "bidirectional"))
      (node (ref "U16") (pin "2") (pinfunction "GND_2") (pintype "bidirectional"))
      (node (ref "U17") (pin "2") (pinfunction "GND_2") (pintype "bidirectional"))
      (node (ref "U18") (pin "3") (pinfunction "GND_3") (pintype "bidirectional"))
      (node (ref "U19") (pin "E5") (pinfunction "GND_E5_E5") (pintype "bidirectional"))
      (node (ref "U19") (pin "E6") (pinfunction "GND_E6_E6") (pintype "bidirectional"))
      (node (ref "U19") (pin "E7") (pinfunction "GND_E7_E7") (pintype "bidirectional"))
      (node (ref "U19") (pin "F5") (pinfunction "GND_F5_F5") (pintype "bidirectional"))
      (node (ref "U19") (pin "F6") (pinfunction "GND_F6_F6") (pintype "bidirectional"))
      (node (ref "U19") (pin "F7") (pinfunction "GND_F7_F7") (pintype "bidirectional"))
      (node (ref "U19") (pin "G5") (pinfunction "GND_G5_G5") (pintype "bidirectional"))
      (node (ref "U19") (pin "G6") (pinfunction "GND_G6_G6") (pintype "bidirectional"))
      (node (ref "U19") (pin "G7") (pinfunction "GND_G7_G7") (pintype "bidirectional"))
      (node (ref "U19") (pin "H5") (pinfunction "GND_H5_H5") (pintype "bidirectional"))
      (node (ref "U2") (pin "2") (pinfunction "GND_2") (pintype "bidirectional"))
      (node (ref "U20") (pin "4") (pinfunction "GND_4") (pintype "bidirectional"))
      (node (ref "U20") (pin "9") (pinfunction "GND_9") (pintype "bidirectional"))
      (node (ref "U21") (pin "2") (pinfunction "GND_2") (pintype "bidirectional"))
      (node (ref "U21") (pin "3") (pinfunction "GND_3") (pintype "bidirectional"))
      (node (ref "U22") (pin "2") (pinfunction "GND_2") (pintype "bidirectional"))
      (node (ref "U22") (pin "3") (pinfunction "GND_3") (pintype "bidirectional"))
      (node (ref "U23") (pin "A3") (pinfunction "AGND_A3") (pintype "bidirectional"))
      (node (ref "U23") (pin "B4") (pinfunction "DGND_B4") (pintype "bidirectional"))
      (node (ref "U23") (pin "B5") (pinfunction "AGND_B5") (pintype "bidirectional"))
      (node (ref "U23") (pin "B6") (pinfunction "DGND_B6") (pintype "bidirectional"))
      (node (ref "U23") (pin "B7") (pinfunction "TEST_B7") (pintype "bidirectional"))
      (node (ref "U23") (pin "C1") (pinfunction "SADDR_C1") (pintype "bidirectional"))
      (node (ref "U23") (pin "C4") (pinfunction "DGND_C4") (pintype "bidirectional"))
      (node (ref "U23") (pin "C5") (pinfunction "DGND_C5") (pintype "bidirectional"))
      (node (ref "U23") (pin "C6") (pinfunction "DGND_C6") (pintype "bidirectional"))
      (node (ref "U23") (pin "D4") (pinfunction "DGND_D4") (pintype "bidirectional"))
      (node (ref "U23") (pin "E6") (pinfunction "DGND_E6") (pintype "bidirectional"))
      (node (ref "U23") (pin "G1") (pinfunction "DGND_G1") (pintype "bidirectional"))
      (node (ref "U23") (pin "H2") (pinfunction "DGND_H2") (pintype "bidirectional"))
      (node (ref "U23") (pin "H3") (pinfunction "DGND_H3") (pintype "bidirectional"))
      (node (ref "U24") (pin "A1") (pinfunction "VSS_A1_A1") (pintype "bidirectional"))
      (node (ref "U24") (pin "A3") (pinfunction "VSSQ_A3_A3") (pintype "bidirectional"))
      (node (ref "U24") (pin "B7") (pinfunction "VSSQ_B7_B7") (pintype "bidirectional"))
      (node (ref "U24") (pin "C3") (pinfunction "VSSQ_C3_C3") (pintype "bidirectional"))
      (node (ref "U24") (pin "D7") (pinfunction "VSSQ_D7_D7") (pintype "bidirectional"))
      (node (ref "U24") (pin "E3") (pinfunction "VSS_E3_E3") (pintype "bidirectional"))
      (node (ref "U24") (pin "J1") (pinfunction "VSS_J1_J1") (pintype "bidirectional"))
      (node (ref "U25") (pin "2") (pinfunction "GND_2") (pintype "bidirectional"))
      (node (ref "U25") (pin "3") (pinfunction "GND_3") (pintype "bidirectional"))
      (node (ref "U25") (pin "6") (pinfunction "GND_6") (pintype "bidirectional"))
      (node (ref "U26") (pin "D5") (pinfunction "VSS_D5_D5") (pintype "bidirectional"))
      (node (ref "U26") (pin "D6") (pinfunction "BOOT0_D6_D6") (pintype "bidirectional"))
      (node (ref "U26") (pin "D7") (pinfunction "VSS_D7_D7") (pintype "bidirectional"))
      (node (ref "U26") (pin "D8") (pinfunction "VSS_D8_D8") (pintype "bidirectional"))
      (node (ref "U26") (pin "D9") (pinfunction "VSS_D9_D9") (pintype "bidirectional"))
      (node (ref "U26") (pin "F10") (pinfunction "VSS_F10_F10") (pintype "bidirectional"))
      (node (ref "U26") (pin "F12") (pinfunction "VSS_F12_F12") (pintype "bidirectional"))
      (node (ref "U26") (pin "F2") (pinfunction "VSS_F2_F2") (pintype "bidirectional"))
      (node (ref "U26") (pin "F6") (pinfunction "VSS_F6_F6") (pintype "bidirectional"))
      (node (ref "U26") (pin "F7") (pinfunction "VSS_F7_F7") (pintype "bidirectional"))
      (node (ref "U26") (pin "F8") (pinfunction "VSS_F8_F8") (pintype "bidirectional"))
      (node (ref "U26") (pin "F9") (pinfunction "VSS_F9_F9") (pintype "bidirectional"))
      (node (ref "U26") (pin "G10") (pinfunction "VSS_G10_G10") (pintype "bidirectional"))
      (node (ref "U26") (pin "G12") (pinfunction "VSS_G12_G12") (pintype "bidirectional"))
      (node (ref "U26") (pin "G2") (pinfunction "VSS_G2_G2") (pintype "bidirectional"))
      (node (ref "U26") (pin "G6") (pinfunction "VSS_G6_G6") (pintype "bidirectional"))
      (node (ref "U26") (pin "G7") (pinfunction "VSS_G7_G7") (pintype "bidirectional"))
      (node (ref "U26") (pin "G8") (pinfunction "VSS_G8_G8") (pintype "bidirectional"))
      (node (ref "U26") (pin "G9") (pinfunction "VSS_G9_G9") (pintype "bidirectional"))
      (node (ref "U26") (pin "H10") (pinfunction "VSS_H10_H10") (pintype "bidirectional"))
      (node (ref "U26") (pin "H12") (pinfunction "VSS_H12_H12") (pintype "bidirectional"))
      (node (ref "U26") (pin "H6") (pinfunction "VSS_H6_H6") (pintype "bidirectional"))
      (node (ref "U26") (pin "H7") (pinfunction "VSS_H7_H7") (pintype "bidirectional"))
      (node (ref "U26") (pin "H8") (pinfunction "VSS_H8_H8") (pintype "bidirectional"))
      (node (ref "U26") (pin "H9") (pinfunction "VSS_H9_H9") (pintype "bidirectional"))
      (node (ref "U26") (pin "J10") (pinfunction "VSS_J10_J10") (pintype "bidirectional"))
      (node (ref "U26") (pin "J6") (pinfunction "VSS_J6_J6") (pintype "bidirectional"))
      (node (ref "U26") (pin "J7") (pinfunction "VSS_J7_J7") (pintype "bidirectional"))
      (node (ref "U26") (pin "J8") (pinfunction "VSS_J8_J8") (pintype "bidirectional"))
      (node (ref "U26") (pin "J9") (pinfunction "VSS_J9_J9") (pintype "bidirectional"))
      (node (ref "U26") (pin "K10") (pinfunction "VSS_K10_K10") (pintype "bidirectional"))
      (node (ref "U26") (pin "K6") (pinfunction "VSS_K6_K6") (pintype "bidirectional"))
      (node (ref "U26") (pin "K7") (pinfunction "VSS_K7_K7") (pintype "bidirectional"))
      (node (ref "U26") (pin "K8") (pinfunction "VSS_K8_K8") (pintype "bidirectional"))
      (node (ref "U26") (pin "K9") (pinfunction "VSS_K9_K9") (pintype "bidirectional"))
      (node (ref "U26") (pin "L4") (pinfunction "BYPASS_REG_L4_L4") (pintype "bidirectional"))
      (node (ref "U26") (pin "M1") (pinfunction "VSSA_M1_M1") (pintype "bidirectional"))
      (node (ref "U26") (pin "M8") (pinfunction "VSS_M8_M8") (pintype "bidirectional"))
      (node (ref "U26") (pin "M9") (pinfunction "VSS_M9_M9") (pintype "bidirectional"))
      (node (ref "U26") (pin "N1") (pinfunction "VREF-_N1_N1") (pintype "bidirectional"))
      (node (ref "U27") (pin "2") (pinfunction "GND_2") (pintype "bidirectional"))
      (node (ref "U3") (pin "2") (pinfunction "GND_2") (pintype "bidirectional"))
      (node (ref "U4") (pin "2") (pinfunction "GND_2") (pintype "bidirectional"))
      (node (ref "U5") (pin "2") (pinfunction "GND_2") (pintype "bidirectional"))
      (node (ref "U6") (pin "2") (pinfunction "2_2") (pintype "bidirectional"))
      (node (ref "U7") (pin "1") (pinfunction "GND_1") (pintype "bidirectional"))
      (node (ref "U7") (pin "6") (pinfunction "PG_6") (pintype "bidirectional"))
      (node (ref "U8") (pin "1") (pinfunction "GND_1") (pintype "bidirectional"))
      (node (ref "U8") (pin "6") (pinfunction "PG_6") (pintype "bidirectional"))
      (node (ref "U9") (pin "1") (pinfunction "GND_1") (pintype "bidirectional"))
      (node (ref "U9") (pin "6") (pinfunction "PG_6") (pintype "bidirectional"))
      (node (ref "X2") (pin "1") (pinfunction "EN__1") (pintype "input"))
      (node (ref "X2") (pin "4") (pinfunction "GND_4") (pintype "bidirectional"))
      (node (ref "X3") (pin "1") (pinfunction "EN__1") (pintype "input"))
      (node (ref "X3") (pin "4") (pinfunction "GND_4") (pintype "bidirectional"))
    )
    (net (code "13") (name "GNDPLL0") (class "Default")
      (node (ref "C41") (pin "2") (pinfunction "2_2") (pintype "bidirectional"))
      (node (ref "C42") (pin "2") (pinfunction "2_2") (pintype "bidirectional"))
      (node (ref "U19") (pin "L6") (pinfunction "GNDPLL0_L6_L6") (pintype "bidirectional"))
    )
    (net (code "14") (name "GNDPLL1") (class "Default")
      (node (ref "C38") (pin "2") (pinfunction "2_2") (pintype "bidirectional"))
      (node (ref "C39") (pin "2") (pinfunction "2_2") (pintype "bidirectional"))
      (node (ref "U19") (pin "C5") (pinfunction "GNDPLL1_C5_C5") (pintype "bidirectional"))
    )
    (net (code "15") (name "ICE_CDONE") (class "Default")
      (node (ref "R25") (pin "2") (pinfunction "2_2") (pintype "bidirectional"))
      (node (ref "U19") (pin "K8") (pinfunction "CDONE_K8_K8") (pintype "bidirectional"))
      (node (ref "U26") (pin "R4") (pinfunction "PB1_R4_R4") (pintype "bidirectional"))
    )
    (net (code "16") (name "ICE_CRST_") (class "Default")
      (node (ref "R26") (pin "2") (pinfunction "2_2") (pintype "bidirectional"))
      (node (ref "U19") (pin "L9") (pinfunction "CRESET_B_L9_L9") (pintype "bidirectional"))
      (node (ref "U26") (pin "R6") (pinfunction "PF11_R6_R6") (pintype "bidirectional"))
    )
    (net (code "17") (name "ICE_IMG_CLK16MHZ") (class "Default")
      (node (ref "TP1") (pin "X") (pinfunction "X_X") (pintype "bidirectional"))
      (node (ref "U19") (pin "C11") (pinfunction "C11_C11") (pintype "bidirectional"))
      (node (ref "U22") (pin "6") (pinfunction "IN_6") (pintype "bidirectional"))
      (node (ref "X2") (pin "2") (pinfunction "OUT_2") (pintype "bidirectional"))
    )
    (net (code "18") (name "ICE_LED0") (class "Default")
      (node (ref "LED3") (pin "A") (pinfunction "A_A") (pintype "bidirectional"))
      (node (ref "U19") (pin "C9") (pinfunction "C9_C9") (pintype "bidirectional"))
    )
    (net (code "19") (name "ICE_LED1") (class "Default")
      (node (ref "LED4") (pin "A") (pinfunction "A_A") (pintype "bidirectional"))
      (node (ref "U19") (pin "B11") (pinfunction "B11_B11") (pintype "bidirectional"))
    )
    (net (code "20") (name "ICE_MSP_SPI_CLK") (class "Default")
      (node (ref "U15") (pin "D2") (pinfunction "A1_D2") (pintype "bidirectional"))
      (node (ref "U19") (pin "K2") (pinfunction "K2_K2") (pintype "bidirectional"))
    )
    (net (code "21") (name "ICE_MSP_SPI_CLK_X") (class "Default")
      (node (ref "U14") (pin "5") (pinfunction "PA.6/P1.6/UCA0CLK/TA1CLK/TDI/TCLK/A6_5") (pintype "bidirectional"))
      (node (ref "U15") (pin "A2") (pinfunction "B1_A2") (pintype "bidirectional"))
    )
    (net (code "22") (name "ICE_MSP_SPI_DATA") (class "Default")
      (node (ref "U15") (pin "D1") (pinfunction "A2_D1") (pintype "bidirectional"))
      (node (ref "U19") (pin "K3") (pinfunction "K3_K3") (pintype "bidirectional"))
    )
    (net (code "23") (name "ICE_MSP_SPI_DATA_X") (class "Default")
      (node (ref "U14") (pin "3") (pinfunction "PA.4/P1.4/UCA0TXD/UCA0SIMO/TA1.2/TCK/A4/VREF+_3") (pintype "bidirectional"))
      (node (ref "U14") (pin "4") (pinfunction "PA.5/P1.5/UCA0RXD/UCA0SOMI/TA1.1/TMS/A5_4") (pintype "bidirectional"))
      (node (ref "U15") (pin "A1") (pinfunction "B2_A1") (pintype "bidirectional"))
    )
    (net (code "24") (name "ICE_STM_FLASH_EN") (class "Default")
      (node (ref "R27") (pin "1") (pinfunction "1_1") (pintype "bidirectional"))
      (node (ref "U21") (pin "1") (pinfunction "IN1_1") (pintype "bidirectional"))
      (node (ref "U26") (pin "K3") (pinfunction "PF5_K3_K3") (pintype "bidirectional"))
    )
    (net (code "25") (name "ICE_STM_SPI_CLK") (class "Default")
      (node (ref "U19") (pin "L10") (pinfunction "SPI_SCK_L10_L10") (pintype "bidirectional"))
      (node (ref "U20") (pin "6") (pinfunction "CLK_6") (pintype "bidirectional"))
      (node (ref "U26") (pin "M6") (pinfunction "PB2_M6_M6") (pintype "bidirectional"))
    )
    (net (code "26") (name "ICE_STM_SPI_CS_") (class "Default")
      (node (ref "U19") (pin "K10") (pinfunction "SPI_SS_B_K10_K10") (pintype "bidirectional"))
      (node (ref "U21") (pin "6") (pinfunction "IN2_6") (pintype "bidirectional"))
      (node (ref "U26") (pin "R10") (pinfunction "PE12_R10_R10") (pintype "bidirectional"))
    )
    (net (code "27") (name "ICE_STM_SPI_D0") (class "Default")
      (node (ref "U19") (pin "L8") (pinfunction "L8_L8") (pintype "bidirectional"))
      (node (ref "U26") (pin "L3") (pinfunction "PF8_L3_L3") (pintype "bidirectional"))
    )
    (net (code "28") (name "ICE_STM_SPI_D1") (class "Default")
      (node (ref "U19") (pin "L7") (pinfunction "L7_L7") (pintype "bidirectional"))
      (node (ref "U26") (pin "L2") (pinfunction "PF9_L2_L2") (pintype "bidirectional"))
    )
    (net (code "29") (name "ICE_STM_SPI_D2") (class "Default")
      (node (ref "U19") (pin "K6") (pinfunction "K6_K6") (pintype "bidirectional"))
      (node (ref "U26") (pin "K1") (pinfunction "PF7_K1_K1") (pintype "bidirectional"))
    )
    (net (code "30") (name "ICE_STM_SPI_D3") (class "Default")
      (node (ref "U19") (pin "K7") (pinfunction "K7_K7") (pintype "bidirectional"))
      (node (ref "U26") (pin "K2") (pinfunction "PF6_K2_K2") (pintype "bidirectional"))
    )
    (net (code "31") (name "ICE_STM_SPI_D4") (class "Default")
      (node (ref "U19") (pin "J9") (pinfunction "SPI_SI_J9_J9") (pintype "bidirectional"))
      (node (ref "U20") (pin "2") (pinfunction "DO_2") (pintype "bidirectional"))
      (node (ref "U26") (pin "R8") (pinfunction "PE7_R8_R8") (pintype "bidirectional"))
    )
    (net (code "32") (name "ICE_STM_SPI_D5") (class "Default")
      (node (ref "U19") (pin "K9") (pinfunction "SPI_SO_K9_K9") (pintype "bidirectional"))
      (node (ref "U20") (pin "5") (pinfunction "DI_5") (pintype "bidirectional"))
      (node (ref "U26") (pin "P8") (pinfunction "PE8_P8_P8") (pintype "bidirectional"))
    )
    (net (code "33") (name "ICE_STM_SPI_D6") (class "Default")
      (node (ref "U19") (pin "J7") (pinfunction "J7_J7") (pintype "bidirectional"))
      (node (ref "U26") (pin "P9") (pinfunction "PE9_P9_P9") (pintype "bidirectional"))
    )
    (net (code "34") (name "ICE_STM_SPI_D7") (class "Default")
      (node (ref "U19") (pin "J8") (pinfunction "J8_J8") (pintype "bidirectional"))
      (node (ref "U26") (pin "R9") (pinfunction "PE10_R9_R9") (pintype "bidirectional"))
    )
    (net (code "35") (name "ICE_STM_SPI_D_READY") (class "Default")
      (node (ref "U19") (pin "L5") (pinfunction "L5_L5") (pintype "bidirectional"))
      (node (ref "U26") (pin "R2") (pinfunction "PA3_R2_R2") (pintype "bidirectional"))
    )
    (net (code "36") (name "IMG_CLK16MHZ") (class "Default")
      (node (ref "U22") (pin "4") (pinfunction "OUT_4") (pintype "bidirectional"))
      (node (ref "U23") (pin "D7") (pinfunction "EXTCLK_D7") (pintype "bidirectional"))
    )
    (net (code "37") (name "IMG_D0") (class "Default")
      (node (ref "U19") (pin "D9") (pinfunction "D9_D9") (pintype "bidirectional"))
      (node (ref "U23") (pin "G6") (pinfunction "DOUT0_G6") (pintype "bidirectional"))
    )
    (net (code "38") (name "IMG_D1") (class "Default")
      (node (ref "U19") (pin "D10") (pinfunction "D10_D10") (pintype "bidirectional"))
      (node (ref "U23") (pin "G5") (pinfunction "DOUT1_G5") (pintype "bidirectional"))
    )
    (net (code "39") (name "IMG_D2") (class "Default")
      (node (ref "U19") (pin "G11") (pinfunction "G11_G11") (pintype "bidirectional"))
      (node (ref "U23") (pin "H4") (pinfunction "DOUT2_H4") (pintype "bidirectional"))
    )
    (net (code "40") (name "IMG_D3") (class "Default")
      (node (ref "U19") (pin "G9") (pinfunction "G9_G9") (pintype "bidirectional"))
      (node (ref "U23") (pin "G4") (pinfunction "DOUT3_G4") (pintype "bidirectional"))
    )
    (net (code "41") (name "IMG_D4") (class "Default")
      (node (ref "U19") (pin "E9") (pinfunction "E9_E9") (pintype "bidirectional"))
      (node (ref "U23") (pin "F5") (pinfunction "DOUT4_F5") (pintype "bidirectional"))
    )
    (net (code "42") (name "IMG_D5") (class "Default")
      (node (ref "U19") (pin "K11") (pinfunction "K11_K11") (pintype "bidirectional"))
      (node (ref "U23") (pin "G3") (pinfunction "DOUT5_G3") (pintype "bidirectional"))
    )
    (net (code "43") (name "IMG_D6") (class "Default")
      (node (ref "U19") (pin "F9") (pinfunction "F9_F9") (pintype "bidirectional"))
      (node (ref "U23") (pin "F4") (pinfunction "DOUT6_F4") (pintype "bidirectional"))
    )
    (net (code "44") (name "IMG_D7") (class "Default")
      (node (ref "U19") (pin "G8") (pinfunction "G8_G8") (pintype "bidirectional"))
      (node (ref "U23") (pin "E4") (pinfunction "DOUT7_E4") (pintype "bidirectional"))
    )
    (net (code "45") (name "IMG_D8") (class "Default")
      (node (ref "U19") (pin "J10") (pinfunction "J10_J10") (pintype "bidirectional"))
      (node (ref "U23") (pin "F3") (pinfunction "DOUT8_F3") (pintype "bidirectional"))
    )
    (net (code "46") (name "IMG_D9") (class "Default")
      (node (ref "U19") (pin "J11") (pinfunction "J11_J11") (pintype "bidirectional"))
      (node (ref "U23") (pin "E3") (pinfunction "DOUT9_E3") (pintype "bidirectional"))
    )
    (net (code "47") (name "IMG_D10") (class "Default")
      (node (ref "U19") (pin "H11") (pinfunction "H11_H11") (pintype "bidirectional"))
      (node (ref "U23") (pin "D3") (pinfunction "DOUT10_D3") (pintype "bidirectional"))
    )
    (net (code "48") (name "IMG_D11") (class "Default")
      (node (ref "U19") (pin "H10") (pinfunction "H10_H10") (pintype "bidirectional"))
      (node (ref "U23") (pin "E2") (pinfunction "DOUT11_E2") (pintype "bidirectional"))
    )
    (net (code "49") (name "IMG_DCLK") (class "Default")
      (node (ref "U19") (pin "F11") (pinfunction "F11_F11") (pintype "bidirectional"))
      (node (ref "U23") (pin "E1") (pinfunction "PIXCLK_E1") (pintype "bidirectional"))
    )
    (net (code "50") (name "IMG_FV") (class "Default")
      (node (ref "U19") (pin "E11") (pinfunction "E11_E11") (pintype "bidirectional"))
      (node (ref "U23") (pin "B3") (pinfunction "FRAME_VALID_B3") (pintype "bidirectional"))
    )
    (net (code "51") (name "IMG_LV") (class "Default")
      (node (ref "U19") (pin "E10") (pinfunction "E10_E10") (pintype "bidirectional"))
      (node (ref "U23") (pin "C3") (pinfunction "LINE_VALID_C3") (pintype "bidirectional"))
    )
    (net (code "52") (name "IMG_RST_") (class "Default")
      (node (ref "R28") (pin "1") (pinfunction "1_1") (pintype "bidirectional"))
      (node (ref "U19") (pin "D11") (pinfunction "D11_D11") (pintype "bidirectional"))
      (node (ref "U23") (pin "C8") (pinfunction "RST__C8") (pintype "bidirectional"))
    )
    (net (code "53") (name "IMG_SCLK") (class "Default")
      (node (ref "U19") (pin "G10") (pinfunction "G10_G10") (pintype "bidirectional"))
      (node (ref "U23") (pin "D1") (pinfunction "SCLK_D1") (pintype "bidirectional"))
    )
    (net (code "54") (name "IMG_SDATA") (class "Default")
      (node (ref "R29") (pin "2") (pinfunction "2_2") (pintype "bidirectional"))
      (node (ref "U19") (pin "F10") (pinfunction "F10_F10") (pintype "bidirectional"))
      (node (ref "U23") (pin "B2") (pinfunction "SDATA_B2") (pintype "bidirectional"))
    )
    (net (code "55") (name "LED_SEL") (class "Default")
      (node (ref "U14") (pin "11") (pinfunction "PA.A/P2.2/ACLK_11") (pintype "bidirectional"))
      (node (ref "U16") (pin "6") (pinfunction "SEL_6") (pintype "bidirectional"))
      (node (ref "U17") (pin "6") (pinfunction "SEL_6") (pintype "bidirectional"))
    )
    (net (code "56") (name "LED_SIGNAL") (class "Default")
      (node (ref "U14") (pin "8") (pinfunction "PA.1/P1.1/UCB0CLK/TA0.1/A1_8") (pintype "bidirectional"))
      (node (ref "U16") (pin "1") (pinfunction "0_1") (pintype "bidirectional"))
      (node (ref "U17") (pin "3") (pinfunction "1_3") (pintype "bidirectional"))
    )
    (net (code "57") (name "MOTION_EN_") (class "Default")
      (node (ref "Q4") (pin "G") (pinfunction "G_G") (pintype "bidirectional"))
      (node (ref "U14") (pin "12") (pinfunction "PB.0/P3.0_12") (pintype "bidirectional"))
    )
    (net (code "58") (name "MOTION_SIGNAL") (class "Default")
      (node (ref "U14") (pin "15") (pinfunction "PA.C/P2.4/UCA1CLK_15") (pintype "bidirectional"))
      (node (ref "U18") (pin "2") (pinfunction "OUT_2") (pintype "bidirectional"))
    )
    (net (code "59") (name "MSP_RST_") (class "Default")
      (node (ref "C21") (pin "1") (pinfunction "1_1") (pintype "bidirectional"))
      (node (ref "U14") (pin "1") (pinfunction "RST_/NMI/SBWTDIO_1") (pintype "bidirectional"))
      (node (ref "U26") (pin "B8") (pinfunction "PG12_B8_B8") (pintype "bidirectional"))
    )
    (net (code "60") (name "MSP_STM_I2C_SCL") (class "Default")
      (node (ref "R37") (pin "1") (pinfunction "1_1") (pintype "bidirectional"))
      (node (ref "U14") (pin "10") (pinfunction "PA.3/P1.3/UCB0SOMI/UCB0SCL/MCLK/A3_10") (pintype "bidirectional"))
      (node (ref "U26") (pin "A5") (pinfunction "PB8_A5_A5") (pintype "bidirectional"))
    )
    (net (code "61") (name "MSP_STM_I2C_SDA") (class "Default")
      (node (ref "R38") (pin "1") (pinfunction "1_1") (pintype "bidirectional"))
      (node (ref "U14") (pin "9") (pinfunction "PA.2/P1.2/UCB0SIMO/UCB0SDA/TA0.2/A2/VEREF-_9") (pintype "bidirectional"))
      (node (ref "U26") (pin "B4") (pinfunction "PB9_B4_B4") (pintype "bidirectional"))
    )
    (net (code "62") (name "MSP_TEST") (class "Default")
      (node (ref "U14") (pin "2") (pinfunction "TEST/SBWTCK_2") (pintype "bidirectional"))
      (node (ref "U26") (pin "B9") (pinfunction "PG11_B9_B9") (pintype "bidirectional"))
    )
    (net (code "63") (name "MSP_XIN") (class "Default")
      (node (ref "C17") (pin "1") (pinfunction "1_1") (pintype "bidirectional"))
      (node (ref "U14") (pin "22") (pinfunction "PA.9/P2.1/XIN_22") (pintype "bidirectional"))
      (node (ref "X1") (pin "2") (pinfunction "B_2") (pintype "bidirectional"))
    )
    (net (code "64") (name "MSP_XOUT") (class "Default")
      (node (ref "C18") (pin "1") (pinfunction "1_1") (pintype "bidirectional"))
      (node (ref "U14") (pin "21") (pinfunction "PA.8/P2.0/XOUT_21") (pintype "bidirectional"))
      (node (ref "X1") (pin "1") (pinfunction "A_1") (pintype "bidirectional"))
    )
    (net (code "65") (name "Net-(C7-Pad1)") (class "Default")
      (node (ref "C7") (pin "1") (pinfunction "1_1") (pintype "bidirectional"))
      (node (ref "J6") (pin "1") (pinfunction "1_1") (pintype "bidirectional"))
      (node (ref "L1") (pin "2") (pinfunction "2_2") (pintype "bidirectional"))
      (node (ref "R12") (pin "1") (pinfunction "1_1") (pintype "bidirectional"))
    )
    (net (code "66") (name "Net-(C9-Pad1)") (class "Default")
      (node (ref "C9") (pin "1") (pinfunction "1_1") (pintype "bidirectional"))
      (node (ref "J7") (pin "1") (pinfunction "1_1") (pintype "bidirectional"))
      (node (ref "L2") (pin "2") (pinfunction "2_2") (pintype "bidirectional"))
      (node (ref "R14") (pin "1") (pinfunction "1_1") (pintype "bidirectional"))
    )
    (net (code "67") (name "Net-(C11-Pad1)") (class "Default")
      (node (ref "C11") (pin "1") (pinfunction "1_1") (pintype "bidirectional"))
      (node (ref "J8") (pin "1") (pinfunction "1_1") (pintype "bidirectional"))
      (node (ref "L3") (pin "2") (pinfunction "2_2") (pintype "bidirectional"))
      (node (ref "R16") (pin "1") (pinfunction "1_1") (pintype "bidirectional"))
    )
    (net (code "68") (name "Net-(FB1-P$1)") (class "Default")
      (node (ref "FB1") (pin "1") (pinfunction "P$1_1") (pintype "bidirectional"))
      (node (ref "J10") (pin "A9B4") (pinfunction "VBUS_A9B4") (pintype "bidirectional"))
      (node (ref "J10") (pin "B9A4") (pinfunction "VBUS_B9A4") (pintype "bidirectional"))
      (node (ref "U27") (pin "4") (pinfunction "IO3_4") (pintype "bidirectional"))
      (node (ref "U27") (pin "5") (pinfunction "VDD_5") (pintype "bidirectional"))
      (node (ref "U27") (pin "6") (pinfunction "IO4_6") (pintype "bidirectional"))
    )
    (net (code "69") (name "Net-(J3-Pad1)") (class "Default")
      (node (ref "J3") (pin "1") (pinfunction "1_1") (pintype "bidirectional"))
      (node (ref "Q1") (pin "1") (pinfunction "D_1") (pintype "bidirectional"))
      (node (ref "Q1") (pin "2") (pinfunction "D_2") (pintype "bidirectional"))
      (node (ref "Q1") (pin "5") (pinfunction "D_5") (pintype "bidirectional"))
      (node (ref "Q1") (pin "6") (pinfunction "D_6") (pintype "bidirectional"))
      (node (ref "Q1") (pin "7") (pinfunction "D_7") (pintype "bidirectional"))
    )
    (net (code "70") (name "Net-(J4-Pad2)") (class "Default")
      (node (ref "J4") (pin "2") (pinfunction "2_2") (pintype "bidirectional"))
      (node (ref "Q2") (pin "4") (pinfunction "S_4") (pintype "bidirectional"))
      (node (ref "Q2") (pin "8") (pinfunction "S_8") (pintype "bidirectional"))
      (node (ref "Q3") (pin "4") (pinfunction "S_4") (pintype "bidirectional"))
      (node (ref "Q3") (pin "8") (pinfunction "S_8") (pintype "bidirectional"))
      (node (ref "R10") (pin "2") (pinfunction "2_2") (pintype "bidirectional"))
    )
    (net (code "71") (name "Net-(J10-CC1)") (class "Default")
      (node (ref "J10") (pin "A5") (pinfunction "CC1_A5") (pintype "bidirectional"))
      (node (ref "R42") (pin "1") (pinfunction "1_1") (pintype "bidirectional"))
    )
    (net (code "72") (name "Net-(J10-CC2)") (class "Default")
      (node (ref "J10") (pin "B5") (pinfunction "CC2_B5") (pintype "bidirectional"))
      (node (ref "R43") (pin "1") (pinfunction "1_1") (pintype "bidirectional"))
    )
    (net (code "73") (name "Net-(LED1-PadC)") (class "Default")
      (node (ref "LED1") (pin "C") (pinfunction "C_C") (pintype "bidirectional"))
      (node (ref "R18") (pin "2") (pinfunction "2_2") (pintype "bidirectional"))
      (node (ref "R19") (pin "2") (pinfunction "2_2") (pintype "bidirectional"))
    )
    (net (code "74") (name "Net-(LED2-PadC)") (class "Default")
      (node (ref "LED2") (pin "C") (pinfunction "C_C") (pintype "bidirectional"))
      (node (ref "R20") (pin "2") (pinfunction "2_2") (pintype "bidirectional"))
    )
    (net (code "75") (name "Net-(LED3-PadC)") (class "Default")
      (node (ref "LED3") (pin "C") (pinfunction "C_C") (pintype "bidirectional"))
      (node (ref "R21") (pin "1") (pinfunction "1_1") (pintype "bidirectional"))
    )
    (net (code "76") (name "Net-(LED4-PadC)") (class "Default")
      (node (ref "LED4") (pin "C") (pinfunction "C_C") (pintype "bidirectional"))
      (node (ref "R22") (pin "1") (pinfunction "1_1") (pintype "bidirectional"))
    )
    (net (code "77") (name "Net-(LED5-PadC)") (class "Default")
      (node (ref "LED5") (pin "C") (pinfunction "C_C") (pintype "bidirectional"))
      (node (ref "R39") (pin "1") (pinfunction "1_1") (pintype "bidirectional"))
    )
    (net (code "78") (name "Net-(LED6-PadC)") (class "Default")
      (node (ref "LED6") (pin "C") (pinfunction "C_C") (pintype "bidirectional"))
      (node (ref "R40") (pin "1") (pinfunction "1_1") (pintype "bidirectional"))
    )
    (net (code "79") (name "Net-(Q1-G)") (class "Default")
      (node (ref "Q1") (pin "3") (pinfunction "G_3") (pintype "bidirectional"))
      (node (ref "R6") (pin "1") (pinfunction "1_1") (pintype "bidirectional"))
    )
    (net (code "80") (name "Net-(Q2-G)") (class "Default")
      (node (ref "Q2") (pin "3") (pinfunction "G_3") (pintype "bidirectional"))
      (node (ref "Q3") (pin "1") (pinfunction "D_1") (pintype "bidirectional"))
      (node (ref "Q3") (pin "2") (pinfunction "D_2") (pintype "bidirectional"))
      (node (ref "Q3") (pin "5") (pinfunction "D_5") (pintype "bidirectional"))
      (node (ref "Q3") (pin "6") (pinfunction "D_6") (pintype "bidirectional"))
      (node (ref "Q3") (pin "7") (pinfunction "D_7") (pintype "bidirectional"))
      (node (ref "R11") (pin "1") (pinfunction "1_1") (pintype "bidirectional"))
    )
    (net (code "81") (name "Net-(U1-PR1)") (class "Default")
      (node (ref "R2") (pin "2") (pinfunction "2_2") (pintype "bidirectional"))
      (node (ref "R4") (pin "1") (pinfunction "1_1") (pintype "bidirectional"))
      (node (ref "U1") (pin "4") (pinfunction "PR1_4") (pintype "bidirectional"))
    )
    (net (code "82") (name "Net-(U2-VOUT)") (class "Default")
      (node (ref "C4") (pin "1") (pinfunction "1_1") (pintype "bidirectional"))
      (node (ref "D1") (pin "A") (pinfunction "A_A") (pintype "bidirectional"))
      (node (ref "J2") (pin "1") (pinfunction "1_1") (pintype "bidirectional"))
      (node (ref "U2") (pin "3") (pinfunction "VOUT_3") (pintype "bidirectional"))
    )
    (net (code "83") (name "Net-(U3-OUT)") (class "Default")
      (node (ref "R6") (pin "2") (pinfunction "2_2") (pintype "bidirectional"))
      (node (ref "U3") (pin "4") (pinfunction "OUT_4") (pintype "bidirectional"))
    )
    (net (code "84") (name "Net-(U4-PROG)") (class "Default")
      (node (ref "R7") (pin "2") (pinfunction "2_2") (pintype "bidirectional"))
      (node (ref "U4") (pin "5") (pinfunction "PROG_5") (pintype "bidirectional"))
    )
    (net (code "85") (name "Net-(U5-QOD)") (class "Default")
      (node (ref "R8") (pin "1") (pinfunction "1_1") (pintype "bidirectional"))
      (node (ref "U5") (pin "5") (pinfunction "QOD_5") (pintype "bidirectional"))
      (node (ref "U5") (pin "6") (pinfunction "VOUT_6") (pintype "bidirectional"))
    )
    (net (code "86") (name "Net-(U7-FB)") (class "Default")
      (node (ref "R12") (pin "2") (pinfunction "2_2") (pintype "bidirectional"))
      (node (ref "R13") (pin "1") (pinfunction "1_1") (pintype "bidirectional"))
      (node (ref "U7") (pin "5") (pinfunction "FB_5") (pintype "bidirectional"))
    )
    (net (code "87") (name "Net-(U7-SW)") (class "Default")
      (node (ref "L1") (pin "1") (pinfunction "1_1") (pintype "bidirectional"))
      (node (ref "U7") (pin "2") (pinfunction "SW_2") (pintype "bidirectional"))
    )
    (net (code "88") (name "Net-(U8-FB)") (class "Default")
      (node (ref "R14") (pin "2") (pinfunction "2_2") (pintype "bidirectional"))
      (node (ref "R15") (pin "1") (pinfunction "1_1") (pintype "bidirectional"))
      (node (ref "U8") (pin "5") (pinfunction "FB_5") (pintype "bidirectional"))
    )
    (net (code "89") (name "Net-(U8-SW)") (class "Default")
      (node (ref "L2") (pin "1") (pinfunction "1_1") (pintype "bidirectional"))
      (node (ref "U8") (pin "2") (pinfunction "SW_2") (pintype "bidirectional"))
    )
    (net (code "90") (name "Net-(U9-FB)") (class "Default")
      (node (ref "R16") (pin "2") (pinfunction "2_2") (pintype "bidirectional"))
      (node (ref "R17") (pin "1") (pinfunction "1_1") (pintype "bidirectional"))
      (node (ref "U9") (pin "5") (pinfunction "FB_5") (pintype "bidirectional"))
    )
    (net (code "91") (name "Net-(U9-SW)") (class "Default")
      (node (ref "L3") (pin "1") (pinfunction "1_1") (pintype "bidirectional"))
      (node (ref "U9") (pin "2") (pinfunction "SW_2") (pintype "bidirectional"))
    )
    (net (code "92") (name "Net-(U16-OUT)") (class "Default")
      (node (ref "LED1") (pin "A") (pinfunction "A_A") (pintype "bidirectional"))
      (node (ref "U16") (pin "4") (pinfunction "OUT_4") (pintype "bidirectional"))
    )
    (net (code "93") (name "Net-(U17-OUT)") (class "Default")
      (node (ref "LED2") (pin "A") (pinfunction "A_A") (pintype "bidirectional"))
      (node (ref "U17") (pin "4") (pinfunction "OUT_4") (pintype "bidirectional"))
    )
    (net (code "94") (name "Net-(U18-VDD)") (class "Default")
      (node (ref "C26") (pin "1") (pinfunction "1_1") (pintype "bidirectional"))
      (node (ref "Q4") (pin "D") (pinfunction "D_D") (pintype "bidirectional"))
      (node (ref "U18") (pin "1") (pinfunction "VDD_1") (pintype "bidirectional"))
    )
    (net (code "95") (name "Net-(U20-CS_)") (class "Default")
      (node (ref "U20") (pin "1") (pinfunction "CS__1") (pintype "bidirectional"))
      (node (ref "U21") (pin "4") (pinfunction "OUT_4") (pintype "bidirectional"))
    )
    (net (code "96") (name "Net-(U25-OUT)") (class "Default")
      (node (ref "Q6") (pin "G") (pinfunction "G_G") (pintype "bidirectional"))
      (node (ref "U25") (pin "4") (pinfunction "OUT_4") (pintype "bidirectional"))
    )
    (net (code "97") (name "Net-(U26J-OTG_HS_REXT_J15)") (class "Default")
      (node (ref "R41") (pin "2") (pinfunction "2_2") (pintype "bidirectional"))
      (node (ref "U26") (pin "J15") (pinfunction "OTG_HS_REXT_J15_J15") (pintype "bidirectional"))
    )
    (net (code "98") (name "Net-(U26J-VDD12OTGHS_J14)") (class "Default")
      (node (ref "C66") (pin "1") (pinfunction "1_1") (pintype "bidirectional"))
      (node (ref "U26") (pin "J14") (pinfunction "VDD12OTGHS_J14_J14") (pintype "bidirectional"))
    )
    (net (code "99") (name "Net-(U26K-VCAP_1_M10)") (class "Default")
      (node (ref "C82") (pin "1") (pinfunction "1_1") (pintype "bidirectional"))
      (node (ref "U26") (pin "M10") (pinfunction "VCAP_1_M10_M10") (pintype "bidirectional"))
    )
    (net (code "100") (name "Net-(U26K-VCAP_2_F13)") (class "Default")
      (node (ref "C83") (pin "1") (pinfunction "1_1") (pintype "bidirectional"))
      (node (ref "U26") (pin "F13") (pinfunction "VCAP_2_F13_F13") (pintype "bidirectional"))
    )
    (net (code "101") (name "RAM_A0") (class "Default")
      (node (ref "U19") (pin "D5") (pinfunction "D5_D5") (pintype "bidirectional"))
      (node (ref "U24") (pin "H7") (pinfunction "A0_H7") (pintype "bidirectional"))
    )
    (net (code "102") (name "RAM_A1") (class "Default")
      (node (ref "U19") (pin "B3") (pinfunction "B3_B3") (pintype "bidirectional"))
      (node (ref "U24") (pin "H8") (pinfunction "A1_H8") (pintype "bidirectional"))
    )
    (net (code "103") (name "RAM_A2") (class "Default")
      (node (ref "U19") (pin "B2") (pinfunction "B2_B2") (pintype "bidirectional"))
      (node (ref "U24") (pin "J8") (pinfunction "A2_J8") (pintype "bidirectional"))
    )
    (net (code "104") (name "RAM_A3") (class "Default")
      (node (ref "U19") (pin "A1") (pinfunction "A1_A1") (pintype "bidirectional"))
      (node (ref "U24") (pin "J7") (pinfunction "A3_J7") (pintype "bidirectional"))
    )
    (net (code "105") (name "RAM_A4") (class "Default")
      (node (ref "U19") (pin "B1") (pinfunction "B1_B1") (pintype "bidirectional"))
      (node (ref "U24") (pin "J3") (pinfunction "A4_J3") (pintype "bidirectional"))
    )
    (net (code "106") (name "RAM_A5") (class "Default")
      (node (ref "U19") (pin "C2") (pinfunction "C2_C2") (pintype "bidirectional"))
      (node (ref "U24") (pin "J2") (pinfunction "A5_J2") (pintype "bidirectional"))
    )
    (net (code "107") (name "RAM_A6") (class "Default")
      (node (ref "U19") (pin "C4") (pinfunction "C4_C4") (pintype "bidirectional"))
      (node (ref "U24") (pin "H3") (pinfunction "A6_H3") (pintype "bidirectional"))
    )
    (net (code "108") (name "RAM_A7") (class "Default")
      (node (ref "U19") (pin "D2") (pinfunction "D2_D2") (pintype "bidirectional"))
      (node (ref "U24") (pin "H2") (pinfunction "A7_H2") (pintype "bidirectional"))
    )
    (net (code "109") (name "RAM_A8") (class "Default")
      (node (ref "U19") (pin "C1") (pinfunction "C1_C1") (pintype "bidirectional"))
      (node (ref "U24") (pin "H1") (pinfunction "A8_H1") (pintype "bidirectional"))
    )
    (net (code "110") (name "RAM_A9") (class "Default")
      (node (ref "U19") (pin "C3") (pinfunction "C3_C3") (pintype "bidirectional"))
      (node (ref "U24") (pin "G3") (pinfunction "A9_G3") (pintype "bidirectional"))
    )
    (net (code "111") (name "RAM_A10") (class "Default")
      (node (ref "U19") (pin "A2") (pinfunction "A2_A2") (pintype "bidirectional"))
      (node (ref "U24") (pin "H9") (pinfunction "A10_H9") (pintype "bidirectional"))
    )
    (net (code "112") (name "RAM_A11") (class "Default")
      (node (ref "U19") (pin "D1") (pinfunction "D1_D1") (pintype "bidirectional"))
      (node (ref "U24") (pin "G2") (pinfunction "A11_G2") (pintype "bidirectional"))
    )
    (net (code "113") (name "RAM_BA0") (class "Default")
      (node (ref "U19") (pin "C7") (pinfunction "C7_C7") (pintype "bidirectional"))
      (node (ref "U24") (pin "G7") (pinfunction "BA0_G7") (pintype "bidirectional"))
    )
    (net (code "114") (name "RAM_BA1") (class "Default")
      (node (ref "U19") (pin "B4") (pinfunction "B4_B4") (pintype "bidirectional"))
      (node (ref "U24") (pin "G8") (pinfunction "BA1_G8") (pintype "bidirectional"))
    )
    (net (code "115") (name "RAM_CAS_") (class "Default")
      (node (ref "U19") (pin "D7") (pinfunction "D7_D7") (pintype "bidirectional"))
      (node (ref "U24") (pin "F7") (pinfunction "~{CAS}_F7") (pintype "bidirectional"))
    )
    (net (code "116") (name "RAM_CKE") (class "Default")
      (node (ref "U19") (pin "D3") (pinfunction "D3_D3") (pintype "bidirectional"))
      (node (ref "U24") (pin "F3") (pinfunction "CKE_F3") (pintype "bidirectional"))
    )
    (net (code "117") (name "RAM_CLK") (class "Default")
      (node (ref "U19") (pin "E1") (pinfunction "E1_E1") (pintype "bidirectional"))
      (node (ref "U24") (pin "F2") (pinfunction "CLK_F2") (pintype "bidirectional"))
    )
    (net (code "118") (name "RAM_CS_") (class "Default")
      (node (ref "U19") (pin "A3") (pinfunction "A3_A3") (pintype "bidirectional"))
      (node (ref "U24") (pin "G9") (pinfunction "~{CS}_G9") (pintype "bidirectional"))
    )
    (net (code "119") (name "RAM_DQ0") (class "Default")
      (node (ref "U19") (pin "A9") (pinfunction "A9_A9") (pintype "bidirectional"))
      (node (ref "U24") (pin "A8") (pinfunction "DQ0_A8") (pintype "bidirectional"))
    )
    (net (code "120") (name "RAM_DQ1") (class "Default")
      (node (ref "U19") (pin "A8") (pinfunction "A8_A8") (pintype "bidirectional"))
      (node (ref "U24") (pin "B9") (pinfunction "DQ1_B9") (pintype "bidirectional"))
    )
    (net (code "121") (name "RAM_DQ2") (class "Default")
      (node (ref "U19") (pin "B9") (pinfunction "B9_B9") (pintype "bidirectional"))
      (node (ref "U24") (pin "B8") (pinfunction "DQ2_B8") (pintype "bidirectional"))
    )
    (net (code "122") (name "RAM_DQ3") (class "Default")
      (node (ref "U19") (pin "A7") (pinfunction "A7_A7") (pintype "bidirectional"))
      (node (ref "U24") (pin "C9") (pinfunction "DQ3_C9") (pintype "bidirectional"))
    )
    (net (code "123") (name "RAM_DQ4") (class "Default")
      (node (ref "U19") (pin "B8") (pinfunction "B8_B8") (pintype "bidirectional"))
      (node (ref "U24") (pin "C8") (pinfunction "DQ4_C8") (pintype "bidirectional"))
    )
    (net (code "124") (name "RAM_DQ5") (class "Default")
      (node (ref "U19") (pin "A6") (pinfunction "A6_A6") (pintype "bidirectional"))
      (node (ref "U24") (pin "D9") (pinfunction "DQ5_D9") (pintype "bidirectional"))
    )
    (net (code "125") (name "RAM_DQ6") (class "Default")
      (node (ref "U19") (pin "B7") (pinfunction "B7_B7") (pintype "bidirectional"))
      (node (ref "U24") (pin "D8") (pinfunction "DQ6_D8") (pintype "bidirectional"))
    )
    (net (code "126") (name "RAM_DQ7") (class "Default")
      (node (ref "U19") (pin "A5") (pinfunction "A5_A5") (pintype "bidirectional"))
      (node (ref "U24") (pin "E9") (pinfunction "DQ7_E9") (pintype "bidirectional"))
    )
    (net (code "127") (name "RAM_DQ8") (class "Default")
      (node (ref "U19") (pin "F2") (pinfunction "F2_F2") (pintype "bidirectional"))
      (node (ref "U24") (pin "E1") (pinfunction "DQ8_E1") (pintype "bidirectional"))
    )
    (net (code "128") (name "RAM_DQ9") (class "Default")
      (node (ref "U19") (pin "G2") (pinfunction "G2_G2") (pintype "bidirectional"))
      (node (ref "U24") (pin "D2") (pinfunction "DQ9_D2") (pintype "bidirectional"))
    )
    (net (code "129") (name "RAM_DQ10") (class "Default")
      (node (ref "U19") (pin "F1") (pinfunction "F1_F1") (pintype "bidirectional"))
      (node (ref "U24") (pin "D1") (pinfunction "DQ10_D1") (pintype "bidirectional"))
    )
    (net (code "130") (name "RAM_DQ11") (class "Default")
      (node (ref "U19") (pin "H2") (pinfunction "H2_H2") (pintype "bidirectional"))
      (node (ref "U24") (pin "C2") (pinfunction "DQ11_C2") (pintype "bidirectional"))
    )
    (net (code "131") (name "RAM_DQ12") (class "Default")
      (node (ref "U19") (pin "G1") (pinfunction "G1_G1") (pintype "bidirectional"))
      (node (ref "U24") (pin "C1") (pinfunction "DQ12_C1") (pintype "bidirectional"))
    )
    (net (code "132") (name "RAM_DQ13") (class "Default")
      (node (ref "U19") (pin "J2") (pinfunction "J2_J2") (pintype "bidirectional"))
      (node (ref "U24") (pin "B2") (pinfunction "DQ13_B2") (pintype "bidirectional"))
    )
    (net (code "133") (name "RAM_DQ14") (class "Default")
      (node (ref "U19") (pin "H1") (pinfunction "H1_H1") (pintype "bidirectional"))
      (node (ref "U24") (pin "B1") (pinfunction "DQ14_B1") (pintype "bidirectional"))
    )
    (net (code "134") (name "RAM_DQ15") (class "Default")
      (node (ref "U19") (pin "J1") (pinfunction "J1_J1") (pintype "bidirectional"))
      (node (ref "U24") (pin "A2") (pinfunction "DQ15_A2") (pintype "bidirectional"))
    )
    (net (code "135") (name "RAM_DQM0") (class "Default")
      (node (ref "U19") (pin "B6") (pinfunction "B6_B6") (pintype "bidirectional"))
      (node (ref "U24") (pin "E8") (pinfunction "LDQM_E8") (pintype "bidirectional"))
    )
    (net (code "136") (name "RAM_DQM1") (class "Default")
      (node (ref "U19") (pin "E2") (pinfunction "E2_E2") (pintype "bidirectional"))
      (node (ref "U24") (pin "F1") (pinfunction "UDQM_F1") (pintype "bidirectional"))
    )
    (net (code "137") (name "RAM_RAS_") (class "Default")
      (node (ref "U19") (pin "B5") (pinfunction "B5_B5") (pintype "bidirectional"))
      (node (ref "U24") (pin "F8") (pinfunction "~{RAS}_F8") (pintype "bidirectional"))
    )
    (net (code "138") (name "RAM_WE_") (class "Default")
      (node (ref "U19") (pin "A4") (pinfunction "A4_A4") (pintype "bidirectional"))
      (node (ref "U24") (pin "F9") (pinfunction "~{WE}_F9") (pintype "bidirectional"))
    )
    (net (code "139") (name "SD_CLK") (class "Default")
      (node (ref "J9") (pin "CLK") (pinfunction "CLK_CLK") (pintype "bidirectional"))
      (node (ref "R31") (pin "1") (pinfunction "1_1") (pintype "bidirectional"))
      (node (ref "U19") (pin "L3") (pinfunction "L3_L3") (pintype "bidirectional"))
    )
    (net (code "140") (name "SD_CMD") (class "Default")
      (node (ref "J9") (pin "CMD") (pinfunction "CMD_CMD") (pintype "bidirectional"))
      (node (ref "R32") (pin "1") (pinfunction "1_1") (pintype "bidirectional"))
      (node (ref "U19") (pin "K4") (pinfunction "K4_K4") (pintype "bidirectional"))
    )
    (net (code "141") (name "SD_DAT0") (class "Default")
      (node (ref "J9") (pin "DAT0") (pinfunction "DAT0_DAT0") (pintype "bidirectional"))
      (node (ref "R33") (pin "1") (pinfunction "1_1") (pintype "bidirectional"))
      (node (ref "U19") (pin "L2") (pinfunction "L2_L2") (pintype "bidirectional"))
    )
    (net (code "142") (name "SD_DAT1") (class "Default")
      (node (ref "J9") (pin "DAT1") (pinfunction "DAT1_DAT1") (pintype "bidirectional"))
      (node (ref "R34") (pin "1") (pinfunction "1_1") (pintype "bidirectional"))
      (node (ref "U19") (pin "L1") (pinfunction "L1_L1") (pintype "bidirectional"))
    )
    (net (code "143") (name "SD_DAT2") (class "Default")
      (node (ref "J9") (pin "DAT2") (pinfunction "DAT2_DAT2") (pintype "bidirectional"))
      (node (ref "R35") (pin "1") (pinfunction "1_1") (pintype "bidirectional"))
      (node (ref "U19") (pin "K5") (pinfunction "K5_K5") (pintype "bidirectional"))
    )
    (net (code "144") (name "SD_DAT3") (class "Default")
      (node (ref "J9") (pin "DAT3") (pinfunction "DAT3_DAT3") (pintype "bidirectional"))
      (node (ref "R36") (pin "1") (pinfunction "1_1") (pintype "bidirectional"))
      (node (ref "U19") (pin "L4") (pinfunction "L4_L4") (pintype "bidirectional"))
    )
    (net (code "145") (name "SD_PULLUP") (class "Default")
      (node (ref "Q5") (pin "S") (pinfunction "S_S") (pintype "bidirectional"))
      (node (ref "Q6") (pin "D") (pinfunction "D_D") (pintype "bidirectional"))
      (node (ref "R31") (pin "2") (pinfunction "2_2") (pintype "bidirectional"))
      (node (ref "R32") (pin "2") (pinfunction "2_2") (pintype "bidirectional"))
      (node (ref "R33") (pin "2") (pinfunction "2_2") (pintype "bidirectional"))
      (node (ref "R34") (pin "2") (pinfunction "2_2") (pintype "bidirectional"))
      (node (ref "R35") (pin "2") (pinfunction "2_2") (pintype "bidirectional"))
      (node (ref "R36") (pin "2") (pinfunction "2_2") (pintype "bidirectional"))
    )
    (net (code "146") (name "SD_PULLUP_1V8_EN_") (class "Default")
      (node (ref "Q5") (pin "G") (pinfunction "G_G") (pintype "bidirectional"))
      (node (ref "R30") (pin "1") (pinfunction "1_1") (pintype "bidirectional"))
      (node (ref "U19") (pin "J3") (pinfunction "J3_J3") (pintype "bidirectional"))
      (node (ref "U25") (pin "1") (pinfunction "IN_1") (pintype "bidirectional"))
    )
    (net (code "147") (name "STM_CLK16MHZ") (class "Default")
      (node (ref "U26") (pin "G1") (pinfunction "PH0_G1_G1") (pintype "bidirectional"))
      (node (ref "X3") (pin "2") (pinfunction "OUT_2") (pintype "bidirectional"))
    )
    (net (code "148") (name "STM_LED0") (class "Default")
      (node (ref "LED6") (pin "A") (pinfunction "A_A") (pintype "bidirectional"))
      (node (ref "U26") (pin "R13") (pinfunction "PB11_R13_R13") (pintype "bidirectional"))
    )
    (net (code "149") (name "STM_LED1") (class "Default")
      (node (ref "LED5") (pin "A") (pinfunction "A_A") (pintype "bidirectional"))
      (node (ref "U26") (pin "P13") (pinfunction "PB13_P13_P13") (pintype "bidirectional"))
    )
    (net (code "150") (name "STM_RST_") (class "Default")
      (node (ref "C65") (pin "1") (pinfunction "1_1") (pintype "bidirectional"))
      (node (ref "U26") (pin "J1") (pinfunction "NRST_J1_J1") (pintype "bidirectional"))
    )
    (net (code "151") (name "STM_SWCLK") (class "Default")
      (node (ref "H1") (pin "6") (pinfunction "6_6") (pintype "bidirectional"))
      (node (ref "U26") (pin "A14") (pinfunction "PA14_A14_A14") (pintype "bidirectional"))
    )
    (net (code "152") (name "STM_SWDIO") (class "Default")
      (node (ref "H1") (pin "5") (pinfunction "5_5") (pintype "bidirectional"))
      (node (ref "U26") (pin "A15") (pinfunction "PA13_A15_A15") (pintype "bidirectional"))
    )
    (net (code "153") (name "USB_D+") (class "Default")
      (node (ref "J10") (pin "A6") (pinfunction "D+_A6") (pintype "bidirectional"))
      (node (ref "J10") (pin "B6") (pinfunction "D+_B6") (pintype "bidirectional"))
      (node (ref "U26") (pin "R15") (pinfunction "PB15_R15_R15") (pintype "bidirectional"))
      (node (ref "U27") (pin "3") (pinfunction "IO2_3") (pintype "bidirectional"))
    )
    (net (code "154") (name "USB_D-") (class "Default")
      (node (ref "J10") (pin "A7") (pinfunction "D-_A7") (pintype "bidirectional"))
      (node (ref "J10") (pin "B7") (pinfunction "D-_B7") (pintype "bidirectional"))
      (node (ref "U26") (pin "R14") (pinfunction "PB14_R14_R14") (pintype "bidirectional"))
      (node (ref "U27") (pin "1") (pinfunction "IO1_1") (pintype "bidirectional"))
    )
    (net (code "155") (name "VCCPLL0") (class "Default")
      (node (ref "C41") (pin "1") (pinfunction "1_1") (pintype "bidirectional"))
      (node (ref "C42") (pin "1") (pinfunction "1_1") (pintype "bidirectional"))
      (node (ref "R24") (pin "1") (pinfunction "1_1") (pintype "bidirectional"))
      (node (ref "U19") (pin "J6") (pinfunction "VCCPLL0_J6_J6") (pintype "bidirectional"))
    )
    (net (code "156") (name "VCCPLL1") (class "Default")
      (node (ref "C38") (pin "1") (pinfunction "1_1") (pintype "bidirectional"))
      (node (ref "C39") (pin "1") (pinfunction "1_1") (pintype "bidirectional"))
      (node (ref "R23") (pin "1") (pinfunction "1_1") (pintype "bidirectional"))
      (node (ref "U19") (pin "C6") (pinfunction "VCCPLL1_C6_C6") (pintype "bidirectional"))
    )
    (net (code "157") (name "VDD_A") (class "Default")
      (node (ref "C2") (pin "1") (pinfunction "1_1") (pintype "bidirectional"))
      (node (ref "C3") (pin "1") (pinfunction "1_1") (pintype "bidirectional"))
      (node (ref "D1") (pin "C") (pinfunction "C_C") (pintype "bidirectional"))
      (node (ref "Q1") (pin "4") (pinfunction "S_4") (pintype "bidirectional"))
      (node (ref "Q1") (pin "8") (pinfunction "S_8") (pintype "bidirectional"))
      (node (ref "U1") (pin "2") (pinfunction "VOUT_2") (pintype "bidirectional"))
      (node (ref "U1") (pin "7") (pinfunction "VOUT_7") (pintype "bidirectional"))
      (node (ref "U2") (pin "1") (pinfunction "EN_1") (pintype "bidirectional"))
      (node (ref "U2") (pin "4") (pinfunction "VIN_4") (pintype "bidirectional"))
      (node (ref "U3") (pin "3") (pinfunction "VDD_3") (pintype "bidirectional"))
      (node (ref "U3") (pin "5") (pinfunction "VDD_5") (pintype "bidirectional"))
    )
    (net (code "158") (name "VDD_A_3V3") (class "Default")
      (node (ref "C16") (pin "1") (pinfunction "1_1") (pintype "bidirectional"))
      (node (ref "C19") (pin "1") (pinfunction "1_1") (pintype "bidirectional"))
      (node (ref "C20") (pin "1") (pinfunction "1_1") (pintype "bidirectional"))
      (node (ref "C23") (pin "1") (pinfunction "1_1") (pintype "bidirectional"))
      (node (ref "C25") (pin "1") (pinfunction "1_1") (pintype "bidirectional"))
      (node (ref "J2") (pin "2") (pinfunction "2_2") (pintype "bidirectional"))
      (node (ref "Q4") (pin "S") (pinfunction "S_S") (pintype "bidirectional"))
      (node (ref "U13") (pin "1") (pinfunction "VIN_1") (pintype "bidirectional"))
      (node (ref "U14") (pin "24") (pinfunction "DVCC_24") (pintype "bidirectional"))
      (node (ref "U15") (pin "B2") (pinfunction "VCCB_B2") (pintype "bidirectional"))
      (node (ref "U16") (pin "3") (pinfunction "1_3") (pintype "bidirectional"))
      (node (ref "U16") (pin "5") (pinfunction "VDD_5") (pintype "bidirectional"))
      (node (ref "U17") (pin "1") (pinfunction "0_1") (pintype "bidirectional"))
      (node (ref "U17") (pin "5") (pinfunction "VDD_5") (pintype "bidirectional"))
    )
    (net (code "159") (name "VDD_B") (class "Default")
      (node (ref "C10") (pin "1") (pinfunction "1_1") (pintype "bidirectional"))
      (node (ref "C12") (pin "1") (pinfunction "1_1") (pintype "bidirectional"))
      (node (ref "C8") (pin "1") (pinfunction "1_1") (pintype "bidirectional"))
      (node (ref "J3") (pin "2") (pinfunction "2_2") (pintype "bidirectional"))
      (node (ref "U7") (pin "3") (pinfunction "VIN_3") (pintype "bidirectional"))
      (node (ref "U7") (pin "4") (pinfunction "EN_4") (pintype "bidirectional"))
      (node (ref "U8") (pin "3") (pinfunction "VIN_3") (pintype "bidirectional"))
      (node (ref "U8") (pin "4") (pinfunction "EN_4") (pintype "bidirectional"))
      (node (ref "U9") (pin "3") (pinfunction "VIN_3") (pintype "bidirectional"))
      (node (ref "U9") (pin "4") (pinfunction "EN_4") (pintype "bidirectional"))
    )
    (net (code "160") (name "VDD_BAT") (class "Default")
      (node (ref "C6") (pin "1") (pinfunction "1_1") (pintype "bidirectional"))
      (node (ref "J4") (pin "1") (pinfunction "1_1") (pintype "bidirectional"))
      (node (ref "U1") (pin "6") (pinfunction "VIN2_6") (pintype "bidirectional"))
      (node (ref "U4") (pin "3") (pinfunction "VBAT_3") (pintype "bidirectional"))
      (node (ref "U5") (pin "1") (pinfunction "VIN_1") (pintype "bidirectional"))
    )
    (net (code "161") (name "VDD_BAT_IN") (class "Default")
      (node (ref "J5") (pin "1") (pinfunction "L_1") (pintype "bidirectional"))
      (node (ref "Q2") (pin "1") (pinfunction "D_1") (pintype "bidirectional"))
      (node (ref "Q2") (pin "2") (pinfunction "D_2") (pintype "bidirectional"))
      (node (ref "Q2") (pin "5") (pinfunction "D_5") (pintype "bidirectional"))
      (node (ref "Q2") (pin "6") (pinfunction "D_6") (pintype "bidirectional"))
      (node (ref "Q2") (pin "7") (pinfunction "D_7") (pintype "bidirectional"))
      (node (ref "Q3") (pin "3") (pinfunction "G_3") (pintype "bidirectional"))
      (node (ref "R10") (pin "1") (pinfunction "1_1") (pintype "bidirectional"))
      (node (ref "U6") (pin "1") (pinfunction "1_1") (pintype "bidirectional"))
    )
    (net (code "162") (name "VDD_B_1V2") (class "Default")
      (node (ref "C27") (pin "1") (pinfunction "1_1") (pintype "bidirectional"))
      (node (ref "C28") (pin "1") (pinfunction "1_1") (pintype "bidirectional"))
      (node (ref "C29") (pin "1") (pinfunction "1_1") (pintype "bidirectional"))
      (node (ref "C30") (pin "1") (pinfunction "1_1") (pintype "bidirectional"))
      (node (ref "J6") (pin "2") (pinfunction "2_2") (pintype "bidirectional"))
      (node (ref "R23") (pin "2") (pinfunction "2_2") (pintype "bidirectional"))
      (node (ref "R24") (pin "2") (pinfunction "2_2") (pintype "bidirectional"))
      (node (ref "U19") (pin "D4") (pinfunction "VCC_D4_D4") (pintype "bidirectional"))
      (node (ref "U19") (pin "D8") (pinfunction "VCC_D8_D8") (pintype "bidirectional"))
      (node (ref "U19") (pin "H4") (pinfunction "VCC_H4_H4") (pintype "bidirectional"))
      (node (ref "U19") (pin "H8") (pinfunction "VCC_H8_H8") (pintype "bidirectional"))
    )
    (net (code "163") (name "VDD_B_1V8") (class "Default")
      (node (ref "C13") (pin "1") (pinfunction "1_1") (pintype "bidirectional"))
      (node (ref "C15") (pin "1") (pinfunction "1_1") (pintype "bidirectional"))
      (node (ref "C24") (pin "1") (pinfunction "1_1") (pintype "bidirectional"))
      (node (ref "C31") (pin "1") (pinfunction "1_1") (pintype "bidirectional"))
      (node (ref "C32") (pin "1") (pinfunction "1_1") (pintype "bidirectional"))
      (node (ref "C33") (pin "1") (pinfunction "1_1") (pintype "bidirectional"))
      (node (ref "C34") (pin "1") (pinfunction "1_1") (pintype "bidirectional"))
      (node (ref "C35") (pin "1") (pinfunction "1_1") (pintype "bidirectional"))
      (node (ref "C40") (pin "1") (pinfunction "1_1") (pintype "bidirectional"))
      (node (ref "C43") (pin "1") (pinfunction "1_1") (pintype "bidirectional"))
      (node (ref "C58") (pin "1") (pinfunction "1_1") (pintype "bidirectional"))
      (node (ref "C59") (pin "1") (pinfunction "1_1") (pintype "bidirectional"))
      (node (ref "C60") (pin "1") (pinfunction "1_1") (pintype "bidirectional"))
      (node (ref "C61") (pin "1") (pinfunction "1_1") (pintype "bidirectional"))
      (node (ref "J7") (pin "2") (pinfunction "2_2") (pintype "bidirectional"))
      (node (ref "R25") (pin "1") (pinfunction "1_1") (pintype "bidirectional"))
      (node (ref "R26") (pin "1") (pinfunction "1_1") (pintype "bidirectional"))
      (node (ref "R27") (pin "2") (pinfunction "2_2") (pintype "bidirectional"))
      (node (ref "U10") (pin "1") (pinfunction "VIN_1") (pintype "bidirectional"))
      (node (ref "U12") (pin "1") (pinfunction "VIN_1") (pintype "bidirectional"))
      (node (ref "U15") (pin "C1") (pinfunction "VCCA_C1") (pintype "bidirectional"))
      (node (ref "U15") (pin "C2") (pinfunction "OE_C2") (pintype "bidirectional"))
      (node (ref "U19") (pin "D6") (pinfunction "VCCIO_0_D6_D6") (pintype "bidirectional"))
      (node (ref "U19") (pin "E4") (pinfunction "VCCIO_3_E4_E4") (pintype "bidirectional"))
      (node (ref "U19") (pin "F8") (pinfunction "VCCIO_1_F8_F8") (pintype "bidirectional"))
      (node (ref "U19") (pin "G4") (pinfunction "VCCIO_3_G4_G4") (pintype "bidirectional"))
      (node (ref "U19") (pin "H6") (pinfunction "VCCIO_2_H6_H6") (pintype "bidirectional"))
      (node (ref "U19") (pin "L11") (pinfunction "VCC_SPI_L11_L11") (pintype "bidirectional"))
      (node (ref "U20") (pin "3") (pinfunction "WP__3") (pintype "bidirectional"))
      (node (ref "U20") (pin "7") (pinfunction "HOLD__7") (pintype "bidirectional"))
      (node (ref "U20") (pin "8") (pinfunction "VCC_8") (pintype "bidirectional"))
      (node (ref "U21") (pin "5") (pinfunction "VDD_5") (pintype "bidirectional"))
      (node (ref "U24") (pin "A7") (pinfunction "VDDQ_A7_A7") (pintype "bidirectional"))
      (node (ref "U24") (pin "A9") (pinfunction "VDD_A9_A9") (pintype "bidirectional"))
      (node (ref "U24") (pin "B3") (pinfunction "VDDQ_B3_B3") (pintype "bidirectional"))
      (node (ref "U24") (pin "C7") (pinfunction "VDDQ_C7_C7") (pintype "bidirectional"))
      (node (ref "U24") (pin "D3") (pinfunction "VDDQ_D3_D3") (pintype "bidirectional"))
      (node (ref "U24") (pin "E7") (pinfunction "VDD_E7_E7") (pintype "bidirectional"))
      (node (ref "U24") (pin "J9") (pinfunction "VDD_J9_J9") (pintype "bidirectional"))
      (node (ref "X2") (pin "3") (pinfunction "VDD_3") (pintype "bidirectional"))
    )
    (net (code "164") (name "VDD_B_1V8_IMG_SD") (class "Default")
      (node (ref "C44") (pin "1") (pinfunction "1_1") (pintype "bidirectional"))
      (node (ref "C49") (pin "1") (pinfunction "1_1") (pintype "bidirectional"))
      (node (ref "C50") (pin "1") (pinfunction "1_1") (pintype "bidirectional"))
      (node (ref "C51") (pin "1") (pinfunction "1_1") (pintype "bidirectional"))
      (node (ref "C52") (pin "1") (pinfunction "1_1") (pintype "bidirectional"))
      (node (ref "C53") (pin "1") (pinfunction "1_1") (pintype "bidirectional"))
      (node (ref "C54") (pin "1") (pinfunction "1_1") (pintype "bidirectional"))
      (node (ref "C55") (pin "1") (pinfunction "1_1") (pintype "bidirectional"))
      (node (ref "Q5") (pin "D") (pinfunction "D_D") (pintype "bidirectional"))
      (node (ref "R28") (pin "2") (pinfunction "2_2") (pintype "bidirectional"))
      (node (ref "R29") (pin "1") (pinfunction "1_1") (pintype "bidirectional"))
      (node (ref "U10") (pin "5") (pinfunction "QOD_5") (pintype "bidirectional"))
      (node (ref "U10") (pin "6") (pinfunction "VOUT_6") (pintype "bidirectional"))
      (node (ref "U22") (pin "1") (pinfunction "VDD_1") (pintype "bidirectional"))
      (node (ref "U22") (pin "5") (pinfunction "VDD_5") (pintype "bidirectional"))
      (node (ref "U23") (pin "A7") (pinfunction "VDD_IO_A7") (pintype "bidirectional"))
      (node (ref "U23") (pin "A8") (pinfunction "VDD_A8") (pintype "bidirectional"))
      (node (ref "U23") (pin "B1") (pinfunction "VDD_B1") (pintype "bidirectional"))
      (node (ref "U23") (pin "D2") (pinfunction "VDD_IO_D2") (pintype "bidirectional"))
      (node (ref "U23") (pin "D5") (pinfunction "VDD_IO_D5") (pintype "bidirectional"))
      (node (ref "U23") (pin "D6") (pinfunction "VDD_IO_D6") (pintype "bidirectional"))
      (node (ref "U23") (pin "E5") (pinfunction "VDD_IO_E5") (pintype "bidirectional"))
      (node (ref "U23") (pin "F6") (pinfunction "VDD_IO_F6") (pintype "bidirectional"))
      (node (ref "U23") (pin "G2") (pinfunction "VDD_G2") (pintype "bidirectional"))
      (node (ref "U23") (pin "G8") (pinfunction "VDD_G8") (pintype "bidirectional"))
      (node (ref "U23") (pin "H5") (pinfunction "VDD_IO_H5") (pintype "bidirectional"))
    )
    (net (code "165") (name "VDD_B_1V8_IMG_SD_EN") (class "Default")
      (node (ref "U10") (pin "3") (pinfunction "EN_3") (pintype "bidirectional"))
      (node (ref "U14") (pin "7") (pinfunction "PA.0/P1.0/UCB0STE/TA0CLK/A0/VEREF+_7") (pintype "bidirectional"))
    )
    (net (code "166") (name "VDD_B_1V8_STM") (class "Default")
      (node (ref "C64") (pin "1") (pinfunction "1_1") (pintype "bidirectional"))
      (node (ref "C67") (pin "1") (pinfunction "1_1") (pintype "bidirectional"))
      (node (ref "C68") (pin "1") (pinfunction "1_1") (pintype "bidirectional"))
      (node (ref "C69") (pin "1") (pinfunction "1_1") (pintype "bidirectional"))
      (node (ref "C70") (pin "1") (pinfunction "1_1") (pintype "bidirectional"))
      (node (ref "C71") (pin "1") (pinfunction "1_1") (pintype "bidirectional"))
      (node (ref "C72") (pin "1") (pinfunction "1_1") (pintype "bidirectional"))
      (node (ref "C73") (pin "1") (pinfunction "1_1") (pintype "bidirectional"))
      (node (ref "C74") (pin "1") (pinfunction "1_1") (pintype "bidirectional"))
      (node (ref "C77") (pin "1") (pinfunction "1_1") (pintype "bidirectional"))
      (node (ref "C78") (pin "1") (pinfunction "1_1") (pintype "bidirectional"))
      (node (ref "C79") (pin "1") (pinfunction "1_1") (pintype "bidirectional"))
      (node (ref "C80") (pin "1") (pinfunction "1_1") (pintype "bidirectional"))
      (node (ref "C81") (pin "1") (pinfunction "1_1") (pintype "bidirectional"))
      (node (ref "C86") (pin "1") (pinfunction "1_1") (pintype "bidirectional"))
      (node (ref "C87") (pin "1") (pinfunction "1_1") (pintype "bidirectional"))
      (node (ref "U12") (pin "5") (pinfunction "QOD_5") (pintype "bidirectional"))
      (node (ref "U12") (pin "6") (pinfunction "VOUT_6") (pintype "bidirectional"))
      (node (ref "U13") (pin "3") (pinfunction "EN_3") (pintype "bidirectional"))
      (node (ref "U26") (pin "C1") (pinfunction "VBAT_C1_C1") (pintype "bidirectional"))
      (node (ref "U26") (pin "C5") (pinfunction "VDD_C5_C5") (pintype "bidirectional"))
      (node (ref "U26") (pin "C6") (pinfunction "PDR_ON_C6_C6") (pintype "bidirectional"))
      (node (ref "U26") (pin "C7") (pinfunction "VDD_C7_C7") (pintype "bidirectional"))
      (node (ref "U26") (pin "C9") (pinfunction "VDD_C9_C9") (pintype "bidirectional"))
      (node (ref "U26") (pin "F3") (pinfunction "VDD_F3_F3") (pintype "bidirectional"))
      (node (ref "U26") (pin "G13") (pinfunction "VDD_G13_G13") (pintype "bidirectional"))
      (node (ref "U26") (pin "G3") (pinfunction "VDD_G3_G3") (pintype "bidirectional"))
      (node (ref "U26") (pin "J12") (pinfunction "VDD_J12_J12") (pintype "bidirectional"))
      (node (ref "U26") (pin "J13") (pinfunction "VDD_J13_J13") (pintype "bidirectional"))
      (node (ref "U26") (pin "K4") (pinfunction "VDD_K4_K4") (pintype "bidirectional"))
      (node (ref "U26") (pin "N10") (pinfunction "VDD_N10_N10") (pintype "bidirectional"))
      (node (ref "U26") (pin "N8") (pinfunction "VDD_N8_N8") (pintype "bidirectional"))
      (node (ref "U26") (pin "N9") (pinfunction "VDD_N9_N9") (pintype "bidirectional"))
      (node (ref "U26") (pin "P1") (pinfunction "VREF+_P1_P1") (pintype "bidirectional"))
      (node (ref "U26") (pin "R1") (pinfunction "VDDA_R1_R1") (pintype "bidirectional"))
      (node (ref "X3") (pin "3") (pinfunction "VDD_3") (pintype "bidirectional"))
    )
    (net (code "167") (name "VDD_B_2V8") (class "Default")
      (node (ref "C14") (pin "1") (pinfunction "1_1") (pintype "bidirectional"))
      (node (ref "C36") (pin "1") (pinfunction "1_1") (pintype "bidirectional"))
      (node (ref "C37") (pin "1") (pinfunction "1_1") (pintype "bidirectional"))
      (node (ref "J8") (pin "2") (pinfunction "2_2") (pintype "bidirectional"))
      (node (ref "U11") (pin "1") (pinfunction "VIN_1") (pintype "bidirectional"))
      (node (ref "U19") (pin "C10") (pinfunction "VPP_2V5_C10_C10") (pintype "bidirectional"))
    )
    (net (code "168") (name "VDD_B_2V8_IMG_SD") (class "Default")
      (node (ref "C45") (pin "1") (pinfunction "1_1") (pintype "bidirectional"))
      (node (ref "C46") (pin "1") (pinfunction "1_1") (pintype "bidirectional"))
      (node (ref "C47") (pin "1") (pinfunction "1_1") (pintype "bidirectional"))
      (node (ref "C48") (pin "1") (pinfunction "1_1") (pintype "bidirectional"))
      (node (ref "C56") (pin "1") (pinfunction "1_1") (pintype "bidirectional"))
      (node (ref "C57") (pin "1") (pinfunction "1_1") (pintype "bidirectional"))
      (node (ref "C62") (pin "1") (pinfunction "1_1") (pintype "bidirectional"))
      (node (ref "C63") (pin "1") (pinfunction "1_1") (pintype "bidirectional"))
      (node (ref "J9") (pin "VDD") (pinfunction "VDD_VDD") (pintype "bidirectional"))
      (node (ref "Q6") (pin "S") (pinfunction "S_S") (pintype "bidirectional"))
      (node (ref "R30") (pin "2") (pinfunction "2_2") (pintype "bidirectional"))
      (node (ref "U11") (pin "5") (pinfunction "QOD_5") (pintype "bidirectional"))
      (node (ref "U11") (pin "6") (pinfunction "VOUT_6") (pintype "bidirectional"))
      (node (ref "U23") (pin "A1") (pinfunction "VAA_A1") (pintype "bidirectional"))
      (node (ref "U23") (pin "A5") (pinfunction "VAA_PIX_A5") (pintype "bidirectional"))
      (node (ref "U23") (pin "A6") (pinfunction "VAA_A6") (pintype "bidirectional"))
      (node (ref "U23") (pin "F8") (pinfunction "VDD_PLL_F8") (pintype "bidirectional"))
      (node (ref "U23") (pin "H6") (pinfunction "VDD_MIPI_H6") (pintype "bidirectional"))
      (node (ref "U23") (pin "H8") (pinfunction "VDD_MIPI_H8") (pintype "bidirectional"))
      (node (ref "U25") (pin "5") (pinfunction "VDD_5") (pintype "bidirectional"))
    )
    (net (code "169") (name "VDD_B_2V8_IMG_SD_EN") (class "Default")
      (node (ref "U11") (pin "3") (pinfunction "EN_3") (pintype "bidirectional"))
      (node (ref "U14") (pin "13") (pinfunction "PA.B/P2.3_13") (pintype "bidirectional"))
    )
    (net (code "170") (name "VDD_B_3V3_STM") (class "Default")
      (node (ref "C75") (pin "1") (pinfunction "1_1") (pintype "bidirectional"))
      (node (ref "C76") (pin "1") (pinfunction "1_1") (pintype "bidirectional"))
      (node (ref "C84") (pin "1") (pinfunction "1_1") (pintype "bidirectional"))
      (node (ref "C85") (pin "1") (pinfunction "1_1") (pintype "bidirectional"))
      (node (ref "R37") (pin "2") (pinfunction "2_2") (pintype "bidirectional"))
      (node (ref "R38") (pin "2") (pinfunction "2_2") (pintype "bidirectional"))
      (node (ref "U13") (pin "5") (pinfunction "QOD_5") (pintype "bidirectional"))
      (node (ref "U13") (pin "6") (pinfunction "VOUT_6") (pintype "bidirectional"))
      (node (ref "U14") (pin "19") (pinfunction "PA.F/P2.7_19") (pintype "bidirectional"))
      (node (ref "U26") (pin "C8") (pinfunction "VDDSDMMC_C8_C8") (pintype "bidirectional"))
      (node (ref "U26") (pin "H13") (pinfunction "VDDUSB_H13_H13") (pintype "bidirectional"))
    )
    (net (code "171") (name "VDD_B_EN") (class "Default")
      (node (ref "R5") (pin "1") (pinfunction "1_1") (pintype "bidirectional"))
      (node (ref "U14") (pin "14") (pinfunction "PB.1/P3.1/UCA1STE_14") (pintype "bidirectional"))
      (node (ref "U3") (pin "6") (pinfunction "IN2_6") (pintype "bidirectional"))
    )
    (net (code "172") (name "VDD_USB") (class "Default")
      (node (ref "C1") (pin "1") (pinfunction "1_1") (pintype "bidirectional"))
      (node (ref "C5") (pin "1") (pinfunction "1_1") (pintype "bidirectional"))
      (node (ref "J1") (pin "2") (pinfunction "2_2") (pintype "bidirectional"))
      (node (ref "R1") (pin "1") (pinfunction "1_1") (pintype "bidirectional"))
      (node (ref "R2") (pin "1") (pinfunction "1_1") (pintype "bidirectional"))
      (node (ref "R3") (pin "1") (pinfunction "1_1") (pintype "bidirectional"))
      (node (ref "U1") (pin "3") (pinfunction "VIN1_3") (pintype "bidirectional"))
      (node (ref "U1") (pin "5") (pinfunction "MODE_5") (pintype "bidirectional"))
      (node (ref "U4") (pin "4") (pinfunction "VDD_4") (pintype "bidirectional"))
    )
    (net (code "173") (name "VDD_USB_EN") (class "Default")
      (node (ref "R3") (pin "2") (pinfunction "2_2") (pintype "bidirectional"))
      (node (ref "U1") (pin "8") (pinfunction "ST_8") (pintype "bidirectional"))
      (node (ref "U12") (pin "3") (pinfunction "EN_3") (pintype "bidirectional"))
      (node (ref "U3") (pin "1") (pinfunction "IN1_1") (pintype "bidirectional"))
    )
    (net (code "174") (name "VDD_USB_IN") (class "Default")
      (node (ref "FB1") (pin "2") (pinfunction "P$2_2") (pintype "bidirectional"))
      (node (ref "H1") (pin "1") (pinfunction "1_1") (pintype "bidirectional"))
      (node (ref "J1") (pin "1") (pinfunction "1_1") (pintype "bidirectional"))
    )
    (net (code "175") (name "unconnected-(H1-Pad2)") (class "Default")
      (node (ref "H1") (pin "2") (pinfunction "2_2") (pintype "bidirectional"))
    )
    (net (code "176") (name "unconnected-(H1-Pad4)") (class "Default")
      (node (ref "H1") (pin "4") (pinfunction "4_4") (pintype "bidirectional"))
    )
    (net (code "177") (name "unconnected-(J9-PadDET)") (class "Default")
      (node (ref "J9") (pin "DET") (pinfunction "DET_DET") (pintype "bidirectional"))
    )
    (net (code "178") (name "unconnected-(J10-SBU1-PadA8)") (class "Default")
      (node (ref "J10") (pin "A8") (pinfunction "SBU1_A8") (pintype "bidirectional"))
    )
    (net (code "179") (name "unconnected-(J10-SBU2-PadB8)") (class "Default")
      (node (ref "J10") (pin "B8") (pinfunction "SBU2_B8") (pintype "bidirectional"))
    )
    (net (code "180") (name "unconnected-(U14C-PB.2{slash}P3.2-Pad20)") (class "Default")
      (node (ref "U14") (pin "20") (pinfunction "PB.2/P3.2_20") (pintype "bidirectional"))
    )
    (net (code "181") (name "unconnected-(U19-PadA10)") (class "Default")
      (node (ref "U19") (pin "A10") (pinfunction "A10_A10") (pintype "bidirectional"))
    )
    (net (code "182") (name "unconnected-(U19-PadA11)") (class "Default")
      (node (ref "U19") (pin "A11") (pinfunction "A11_A11") (pintype "bidirectional"))
    )
    (net (code "183") (name "unconnected-(U19-PadC8)") (class "Default")
      (node (ref "U19") (pin "C8") (pinfunction "C8_C8") (pintype "bidirectional"))
    )
    (net (code "184") (name "unconnected-(U19-PadE3)") (class "Default")
      (node (ref "U19") (pin "E3") (pinfunction "E3_E3") (pintype "bidirectional"))
    )
    (net (code "185") (name "unconnected-(U19-PadE8)") (class "Default")
      (node (ref "U19") (pin "E8") (pinfunction "E8_E8") (pintype "bidirectional"))
    )
    (net (code "186") (name "unconnected-(U19-PadF3)") (class "Default")
      (node (ref "U19") (pin "F3") (pinfunction "F3_F3") (pintype "bidirectional"))
    )
    (net (code "187") (name "unconnected-(U19-PadF4)") (class "Default")
      (node (ref "U19") (pin "F4") (pinfunction "F4_F4") (pintype "bidirectional"))
    )
    (net (code "188") (name "unconnected-(U19-PadG3)") (class "Default")
      (node (ref "U19") (pin "G3") (pinfunction "G3_G3") (pintype "bidirectional"))
    )
    (net (code "189") (name "unconnected-(U19-PadH3)") (class "Default")
      (node (ref "U19") (pin "H3") (pinfunction "H3_H3") (pintype "bidirectional"))
    )
    (net (code "190") (name "unconnected-(U19-PadH7)") (class "Default")
      (node (ref "U19") (pin "H7") (pinfunction "H7_H7") (pintype "bidirectional"))
    )
    (net (code "191") (name "unconnected-(U19-PadH9)") (class "Default")
      (node (ref "U19") (pin "H9") (pinfunction "H9_H9") (pintype "bidirectional"))
    )
    (net (code "192") (name "unconnected-(U19-PadJ4)") (class "Default")
      (node (ref "U19") (pin "J4") (pinfunction "J4_J4") (pintype "bidirectional"))
    )
    (net (code "193") (name "unconnected-(U19-PadJ5)") (class "Default")
      (node (ref "U19") (pin "J5") (pinfunction "J5_J5") (pintype "bidirectional"))
    )
    (net (code "194") (name "unconnected-(U19-PadK1)") (class "Default")
      (node (ref "U19") (pin "K1") (pinfunction "K1_K1") (pintype "bidirectional"))
    )
    (net (code "195") (name "unconnected-(U19E-VPP_FAST_B10-PadB10)") (class "Default")
      (node (ref "U19") (pin "B10") (pinfunction "VPP_FAST_B10_B10") (pintype "bidirectional"))
    )
    (net (code "196") (name "unconnected-(U23A-VAAHV_NPIX-PadA2)") (class "Default")
      (node (ref "U23") (pin "A2") (pinfunction "VAAHV_NPIX_A2") (pintype "bidirectional"))
    )
    (net (code "197") (name "unconnected-(U23B-CLK_N-PadE7)") (class "Default")
      (node (ref "U23") (pin "E7") (pinfunction "CLK_N_E7") (pintype "bidirectional"))
    )
    (net (code "198") (name "unconnected-(U23B-CLK_P-PadF7)") (class "Default")
      (node (ref "U23") (pin "F7") (pinfunction "CLK_P_F7") (pintype "bidirectional"))
    )
    (net (code "199") (name "unconnected-(U23B-DATA2_N-PadG7)") (class "Default")
      (node (ref "U23") (pin "G7") (pinfunction "DATA2_N_G7") (pintype "bidirectional"))
    )
    (net (code "200") (name "unconnected-(U23B-DATA2_P-PadH7)") (class "Default")
      (node (ref "U23") (pin "H7") (pinfunction "DATA2_P_H7") (pintype "bidirectional"))
    )
    (net (code "201") (name "unconnected-(U23B-DATA_N-PadD8)") (class "Default")
      (node (ref "U23") (pin "D8") (pinfunction "DATA_N_D8") (pintype "bidirectional"))
    )
    (net (code "202") (name "unconnected-(U23B-DATA_P-PadE8)") (class "Default")
      (node (ref "U23") (pin "E8") (pinfunction "DATA_P_E8") (pintype "bidirectional"))
    )
    (net (code "203") (name "unconnected-(U23B-FLASH-PadC2)") (class "Default")
      (node (ref "U23") (pin "C2") (pinfunction "FLASH_C2") (pintype "bidirectional"))
    )
    (net (code "204") (name "unconnected-(U23B-SHUTTER-PadB8)") (class "Default")
      (node (ref "U23") (pin "B8") (pinfunction "SHUTTER_B8") (pintype "bidirectional"))
    )
    (net (code "205") (name "unconnected-(U23B-TRIGGER-PadC7)") (class "Default")
      (node (ref "U23") (pin "C7") (pinfunction "TRIGGER_C7") (pintype "bidirectional"))
    )
    (net (code "206") (name "unconnected-(U26A-PA0_N3-PadN3)") (class "Default")
      (node (ref "U26") (pin "N3") (pinfunction "PA0_N3_N3") (pintype "bidirectional"))
    )
    (net (code "207") (name "unconnected-(U26A-PA1_N2-PadN2)") (class "Default")
      (node (ref "U26") (pin "N2") (pinfunction "PA1_N2_N2") (pintype "bidirectional"))
    )
    (net (code "208") (name "unconnected-(U26A-PA2_P2-PadP2)") (class "Default")
      (node (ref "U26") (pin "P2") (pinfunction "PA2_P2_P2") (pintype "bidirectional"))
    )
    (net (code "209") (name "unconnected-(U26A-PA4_N4-PadN4)") (class "Default")
      (node (ref "U26") (pin "N4") (pinfunction "PA4_N4_N4") (pintype "bidirectional"))
    )
    (net (code "210") (name "unconnected-(U26A-PA5_P4-PadP4)") (class "Default")
      (node (ref "U26") (pin "P4") (pinfunction "PA5_P4_P4") (pintype "bidirectional"))
    )
    (net (code "211") (name "unconnected-(U26A-PA6_P3-PadP3)") (class "Default")
      (node (ref "U26") (pin "P3") (pinfunction "PA6_P3_P3") (pintype "bidirectional"))
    )
    (net (code "212") (name "unconnected-(U26A-PA7_R3-PadR3)") (class "Default")
      (node (ref "U26") (pin "R3") (pinfunction "PA7_R3_R3") (pintype "bidirectional"))
    )
    (net (code "213") (name "unconnected-(U26A-PA8_F15-PadF15)") (class "Default")
      (node (ref "U26") (pin "F15") (pinfunction "PA8_F15_F15") (pintype "bidirectional"))
    )
    (net (code "214") (name "unconnected-(U26A-PA9_E15-PadE15)") (class "Default")
      (node (ref "U26") (pin "E15") (pinfunction "PA9_E15_E15") (pintype "bidirectional"))
    )
    (net (code "215") (name "unconnected-(U26A-PA10_D15-PadD15)") (class "Default")
      (node (ref "U26") (pin "D15") (pinfunction "PA10_D15_D15") (pintype "bidirectional"))
    )
    (net (code "216") (name "unconnected-(U26A-PA11_C15-PadC15)") (class "Default")
      (node (ref "U26") (pin "C15") (pinfunction "PA11_C15_C15") (pintype "bidirectional"))
    )
    (net (code "217") (name "unconnected-(U26A-PA12_B15-PadB15)") (class "Default")
      (node (ref "U26") (pin "B15") (pinfunction "PA12_B15_B15") (pintype "bidirectional"))
    )
    (net (code "218") (name "unconnected-(U26A-PA15_A13-PadA13)") (class "Default")
      (node (ref "U26") (pin "A13") (pinfunction "PA15_A13_A13") (pintype "bidirectional"))
    )
    (net (code "219") (name "unconnected-(U26B-PB0_R5-PadR5)") (class "Default")
      (node (ref "U26") (pin "R5") (pinfunction "PB0_R5_R5") (pintype "bidirectional"))
    )
    (net (code "220") (name "unconnected-(U26B-PB3_A10-PadA10)") (class "Default")
      (node (ref "U26") (pin "A10") (pinfunction "PB3_A10_A10") (pintype "bidirectional"))
    )
    (net (code "221") (name "unconnected-(U26B-PB4_A9-PadA9)") (class "Default")
      (node (ref "U26") (pin "A9") (pinfunction "PB4_A9_A9") (pintype "bidirectional"))
    )
    (net (code "222") (name "unconnected-(U26B-PB5_A6-PadA6)") (class "Default")
      (node (ref "U26") (pin "A6") (pinfunction "PB5_A6_A6") (pintype "bidirectional"))
    )
    (net (code "223") (name "unconnected-(U26B-PB6_B6-PadB6)") (class "Default")
      (node (ref "U26") (pin "B6") (pinfunction "PB6_B6_B6") (pintype "bidirectional"))
    )
    (net (code "224") (name "unconnected-(U26B-PB7_B5-PadB5)") (class "Default")
      (node (ref "U26") (pin "B5") (pinfunction "PB7_B5_B5") (pintype "bidirectional"))
    )
    (net (code "225") (name "unconnected-(U26B-PB12_P12-PadP12)") (class "Default")
      (node (ref "U26") (pin "P12") (pinfunction "PB12_P12_P12") (pintype "bidirectional"))
    )
    (net (code "226") (name "unconnected-(U26C-PC0_M2-PadM2)") (class "Default")
      (node (ref "U26") (pin "M2") (pinfunction "PC0_M2_M2") (pintype "bidirectional"))
    )
    (net (code "227") (name "unconnected-(U26C-PC1_M3-PadM3)") (class "Default")
      (node (ref "U26") (pin "M3") (pinfunction "PC1_M3_M3") (pintype "bidirectional"))
    )
    (net (code "228") (name "unconnected-(U26C-PC2_M4-PadM4)") (class "Default")
      (node (ref "U26") (pin "M4") (pinfunction "PC2_M4_M4") (pintype "bidirectional"))
    )
    (net (code "229") (name "unconnected-(U26C-PC3_M5-PadM5)") (class "Default")
      (node (ref "U26") (pin "M5") (pinfunction "PC3_M5_M5") (pintype "bidirectional"))
    )
    (net (code "230") (name "unconnected-(U26C-PC4_N5-PadN5)") (class "Default")
      (node (ref "U26") (pin "N5") (pinfunction "PC4_N5_N5") (pintype "bidirectional"))
    )
    (net (code "231") (name "unconnected-(U26C-PC5_P5-PadP5)") (class "Default")
      (node (ref "U26") (pin "P5") (pinfunction "PC5_P5_P5") (pintype "bidirectional"))
    )
    (net (code "232") (name "unconnected-(U26C-PC6_H15-PadH15)") (class "Default")
      (node (ref "U26") (pin "H15") (pinfunction "PC6_H15_H15") (pintype "bidirectional"))
    )
    (net (code "233") (name "unconnected-(U26C-PC7_G15-PadG15)") (class "Default")
      (node (ref "U26") (pin "G15") (pinfunction "PC7_G15_G15") (pintype "bidirectional"))
    )
    (net (code "234") (name "unconnected-(U26C-PC8_G14-PadG14)") (class "Default")
      (node (ref "U26") (pin "G14") (pinfunction "PC8_G14_G14") (pintype "bidirectional"))
    )
    (net (code "235") (name "unconnected-(U26C-PC9_F14-PadF14)") (class "Default")
      (node (ref "U26") (pin "F14") (pinfunction "PC9_F14_F14") (pintype "bidirectional"))
    )
    (net (code "236") (name "unconnected-(U26C-PC10_B14-PadB14)") (class "Default")
      (node (ref "U26") (pin "B14") (pinfunction "PC10_B14_B14") (pintype "bidirectional"))
    )
    (net (code "237") (name "unconnected-(U26C-PC11_B13-PadB13)") (class "Default")
      (node (ref "U26") (pin "B13") (pinfunction "PC11_B13_B13") (pintype "bidirectional"))
    )
    (net (code "238") (name "unconnected-(U26C-PC12_A12-PadA12)") (class "Default")
      (node (ref "U26") (pin "A12") (pinfunction "PC12_A12_A12") (pintype "bidirectional"))
    )
    (net (code "239") (name "unconnected-(U26C-PC13_D1-PadD1)") (class "Default")
      (node (ref "U26") (pin "D1") (pinfunction "PC13_D1_D1") (pintype "bidirectional"))
    )
    (net (code "240") (name "unconnected-(U26C-PC14_E1-PadE1)") (class "Default")
      (node (ref "U26") (pin "E1") (pinfunction "PC14_E1_E1") (pintype "bidirectional"))
    )
    (net (code "241") (name "unconnected-(U26C-PC15_F1-PadF1)") (class "Default")
      (node (ref "U26") (pin "F1") (pinfunction "PC15_F1_F1") (pintype "bidirectional"))
    )
    (net (code "242") (name "unconnected-(U26D-PD0_B12-PadB12)") (class "Default")
      (node (ref "U26") (pin "B12") (pinfunction "PD0_B12_B12") (pintype "bidirectional"))
    )
    (net (code "243") (name "unconnected-(U26D-PD1_C12-PadC12)") (class "Default")
      (node (ref "U26") (pin "C12") (pinfunction "PD1_C12_C12") (pintype "bidirectional"))
    )
    (net (code "244") (name "unconnected-(U26D-PD2_D12-PadD12)") (class "Default")
      (node (ref "U26") (pin "D12") (pinfunction "PD2_D12_D12") (pintype "bidirectional"))
    )
    (net (code "245") (name "unconnected-(U26D-PD3_D11-PadD11)") (class "Default")
      (node (ref "U26") (pin "D11") (pinfunction "PD3_D11_D11") (pintype "bidirectional"))
    )
    (net (code "246") (name "unconnected-(U26D-PD4_D10-PadD10)") (class "Default")
      (node (ref "U26") (pin "D10") (pinfunction "PD4_D10_D10") (pintype "bidirectional"))
    )
    (net (code "247") (name "unconnected-(U26D-PD5_C11-PadC11)") (class "Default")
      (node (ref "U26") (pin "C11") (pinfunction "PD5_C11_C11") (pintype "bidirectional"))
    )
    (net (code "248") (name "unconnected-(U26D-PD6_B11-PadB11)") (class "Default")
      (node (ref "U26") (pin "B11") (pinfunction "PD6_B11_B11") (pintype "bidirectional"))
    )
    (net (code "249") (name "unconnected-(U26D-PD7_A11-PadA11)") (class "Default")
      (node (ref "U26") (pin "A11") (pinfunction "PD7_A11_A11") (pintype "bidirectional"))
    )
    (net (code "250") (name "unconnected-(U26D-PD8_P15-PadP15)") (class "Default")
      (node (ref "U26") (pin "P15") (pinfunction "PD8_P15_P15") (pintype "bidirectional"))
    )
    (net (code "251") (name "unconnected-(U26D-PD9_P14-PadP14)") (class "Default")
      (node (ref "U26") (pin "P14") (pinfunction "PD9_P14_P14") (pintype "bidirectional"))
    )
    (net (code "252") (name "unconnected-(U26D-PD10_N15-PadN15)") (class "Default")
      (node (ref "U26") (pin "N15") (pinfunction "PD10_N15_N15") (pintype "bidirectional"))
    )
    (net (code "253") (name "unconnected-(U26D-PD11_N14-PadN14)") (class "Default")
      (node (ref "U26") (pin "N14") (pinfunction "PD11_N14_N14") (pintype "bidirectional"))
    )
    (net (code "254") (name "unconnected-(U26D-PD12_N13-PadN13)") (class "Default")
      (node (ref "U26") (pin "N13") (pinfunction "PD12_N13_N13") (pintype "bidirectional"))
    )
    (net (code "255") (name "unconnected-(U26D-PD13_M15-PadM15)") (class "Default")
      (node (ref "U26") (pin "M15") (pinfunction "PD13_M15_M15") (pintype "bidirectional"))
    )
    (net (code "256") (name "unconnected-(U26D-PD14_M14-PadM14)") (class "Default")
      (node (ref "U26") (pin "M14") (pinfunction "PD14_M14_M14") (pintype "bidirectional"))
    )
    (net (code "257") (name "unconnected-(U26D-PD15_L14-PadL14)") (class "Default")
      (node (ref "U26") (pin "L14") (pinfunction "PD15_L14_L14") (pintype "bidirectional"))
    )
    (net (code "258") (name "unconnected-(U26E-PE0_A4-PadA4)") (class "Default")
      (node (ref "U26") (pin "A4") (pinfunction "PE0_A4_A4") (pintype "bidirectional"))
    )
    (net (code "259") (name "unconnected-(U26E-PE1_A3-PadA3)") (class "Default")
      (node (ref "U26") (pin "A3") (pinfunction "PE1_A3_A3") (pintype "bidirectional"))
    )
    (net (code "260") (name "unconnected-(U26E-PE2_A2-PadA2)") (class "Default")
      (node (ref "U26") (pin "A2") (pinfunction "PE2_A2_A2") (pintype "bidirectional"))
    )
    (net (code "261") (name "unconnected-(U26E-PE3_A1-PadA1)") (class "Default")
      (node (ref "U26") (pin "A1") (pinfunction "PE3_A1_A1") (pintype "bidirectional"))
    )
    (net (code "262") (name "unconnected-(U26E-PE4_B1-PadB1)") (class "Default")
      (node (ref "U26") (pin "B1") (pinfunction "PE4_B1_B1") (pintype "bidirectional"))
    )
    (net (code "263") (name "unconnected-(U26E-PE5_B2-PadB2)") (class "Default")
      (node (ref "U26") (pin "B2") (pinfunction "PE5_B2_B2") (pintype "bidirectional"))
    )
    (net (code "264") (name "unconnected-(U26E-PE6_B3-PadB3)") (class "Default")
      (node (ref "U26") (pin "B3") (pinfunction "PE6_B3_B3") (pintype "bidirectional"))
    )
    (net (code "265") (name "unconnected-(U26E-PE11_P10-PadP10)") (class "Default")
      (node (ref "U26") (pin "P10") (pinfunction "PE11_P10_P10") (pintype "bidirectional"))
    )
    (net (code "266") (name "unconnected-(U26E-PE13_N11-PadN11)") (class "Default")
      (node (ref "U26") (pin "N11") (pinfunction "PE13_N11_N11") (pintype "bidirectional"))
    )
    (net (code "267") (name "unconnected-(U26E-PE14_P11-PadP11)") (class "Default")
      (node (ref "U26") (pin "P11") (pinfunction "PE14_P11_P11") (pintype "bidirectional"))
    )
    (net (code "268") (name "unconnected-(U26F-PF0_E2-PadE2)") (class "Default")
      (node (ref "U26") (pin "E2") (pinfunction "PF0_E2_E2") (pintype "bidirectional"))
    )
    (net (code "269") (name "unconnected-(U26F-PF1_H3-PadH3)") (class "Default")
      (node (ref "U26") (pin "H3") (pinfunction "PF1_H3_H3") (pintype "bidirectional"))
    )
    (net (code "270") (name "unconnected-(U26F-PF2_H2-PadH2)") (class "Default")
      (node (ref "U26") (pin "H2") (pinfunction "PF2_H2_H2") (pintype "bidirectional"))
    )
    (net (code "271") (name "unconnected-(U26F-PF3_J2-PadJ2)") (class "Default")
      (node (ref "U26") (pin "J2") (pinfunction "PF3_J2_J2") (pintype "bidirectional"))
    )
    (net (code "272") (name "unconnected-(U26F-PF4_J3-PadJ3)") (class "Default")
      (node (ref "U26") (pin "J3") (pinfunction "PF4_J3_J3") (pintype "bidirectional"))
    )
    (net (code "273") (name "unconnected-(U26F-PF10_L1-PadL1)") (class "Default")
      (node (ref "U26") (pin "L1") (pinfunction "PF10_L1_L1") (pintype "bidirectional"))
    )
    (net (code "274") (name "unconnected-(U26F-PF12_P6-PadP6)") (class "Default")
      (node (ref "U26") (pin "P6") (pinfunction "PF12_P6_P6") (pintype "bidirectional"))
    )
    (net (code "275") (name "unconnected-(U26F-PF13_N6-PadN6)") (class "Default")
      (node (ref "U26") (pin "N6") (pinfunction "PF13_N6_N6") (pintype "bidirectional"))
    )
    (net (code "276") (name "unconnected-(U26F-PF14_R7-PadR7)") (class "Default")
      (node (ref "U26") (pin "R7") (pinfunction "PF14_R7_R7") (pintype "bidirectional"))
    )
    (net (code "277") (name "unconnected-(U26F-PF15_P7-PadP7)") (class "Default")
      (node (ref "U26") (pin "P7") (pinfunction "PF15_P7_P7") (pintype "bidirectional"))
    )
    (net (code "278") (name "unconnected-(U26G-PG0_N7-PadN7)") (class "Default")
      (node (ref "U26") (pin "N7") (pinfunction "PG0_N7_N7") (pintype "bidirectional"))
    )
    (net (code "279") (name "unconnected-(U26G-PG1_M7-PadM7)") (class "Default")
      (node (ref "U26") (pin "M7") (pinfunction "PG1_M7_M7") (pintype "bidirectional"))
    )
    (net (code "280") (name "unconnected-(U26G-PG2_L15-PadL15)") (class "Default")
      (node (ref "U26") (pin "L15") (pinfunction "PG2_L15_L15") (pintype "bidirectional"))
    )
    (net (code "281") (name "unconnected-(U26G-PG3_K15-PadK15)") (class "Default")
      (node (ref "U26") (pin "K15") (pinfunction "PG3_K15_K15") (pintype "bidirectional"))
    )
    (net (code "282") (name "unconnected-(U26G-PG4_K14-PadK14)") (class "Default")
      (node (ref "U26") (pin "K14") (pinfunction "PG4_K14_K14") (pintype "bidirectional"))
    )
    (net (code "283") (name "unconnected-(U26G-PG5_K13-PadK13)") (class "Default")
      (node (ref "U26") (pin "K13") (pinfunction "PG5_K13_K13") (pintype "bidirectional"))
    )
    (net (code "284") (name "unconnected-(U26G-PG8_H14-PadH14)") (class "Default")
      (node (ref "U26") (pin "H14") (pinfunction "PG8_H14_H14") (pintype "bidirectional"))
    )
    (net (code "285") (name "unconnected-(U26G-PG9_C10-PadC10)") (class "Default")
      (node (ref "U26") (pin "C10") (pinfunction "PG9_C10_C10") (pintype "bidirectional"))
    )
    (net (code "286") (name "unconnected-(U26G-PG10_B10-PadB10)") (class "Default")
      (node (ref "U26") (pin "B10") (pinfunction "PG10_B10_B10") (pintype "bidirectional"))
    )
    (net (code "287") (name "unconnected-(U26G-PG13_A8-PadA8)") (class "Default")
      (node (ref "U26") (pin "A8") (pinfunction "PG13_A8_A8") (pintype "bidirectional"))
    )
    (net (code "288") (name "unconnected-(U26G-PG14_A7-PadA7)") (class "Default")
      (node (ref "U26") (pin "A7") (pinfunction "PG14_A7_A7") (pintype "bidirectional"))
    )
    (net (code "289") (name "unconnected-(U26G-PG15_B7-PadB7)") (class "Default")
      (node (ref "U26") (pin "B7") (pinfunction "PG15_B7_B7") (pintype "bidirectional"))
    )
    (net (code "290") (name "unconnected-(U26H-PH1_H1-PadH1)") (class "Default")
      (node (ref "U26") (pin "H1") (pinfunction "PH1_H1_H1") (pintype "bidirectional"))
    )
    (net (code "291") (name "unconnected-(U26H-PH2_F4-PadF4)") (class "Default")
      (node (ref "U26") (pin "F4") (pinfunction "PH2_F4_F4") (pintype "bidirectional"))
    )
    (net (code "292") (name "unconnected-(U26H-PH3_G4-PadG4)") (class "Default")
      (node (ref "U26") (pin "G4") (pinfunction "PH3_G4_G4") (pintype "bidirectional"))
    )
    (net (code "293") (name "unconnected-(U26H-PH4_H4-PadH4)") (class "Default")
      (node (ref "U26") (pin "H4") (pinfunction "PH4_H4_H4") (pintype "bidirectional"))
    )
    (net (code "294") (name "unconnected-(U26H-PH5_J4-PadJ4)") (class "Default")
      (node (ref "U26") (pin "J4") (pinfunction "PH5_J4_J4") (pintype "bidirectional"))
    )
    (net (code "295") (name "unconnected-(U26H-PH6_M11-PadM11)") (class "Default")
      (node (ref "U26") (pin "M11") (pinfunction "PH6_M11_M11") (pintype "bidirectional"))
    )
    (net (code "296") (name "unconnected-(U26H-PH7_N12-PadN12)") (class "Default")
      (node (ref "U26") (pin "N12") (pinfunction "PH7_N12_N12") (pintype "bidirectional"))
    )
    (net (code "297") (name "unconnected-(U26H-PH8_M12-PadM12)") (class "Default")
      (node (ref "U26") (pin "M12") (pinfunction "PH8_M12_M12") (pintype "bidirectional"))
    )
    (net (code "298") (name "unconnected-(U26H-PH9_M13-PadM13)") (class "Default")
      (node (ref "U26") (pin "M13") (pinfunction "PH9_M13_M13") (pintype "bidirectional"))
    )
    (net (code "299") (name "unconnected-(U26H-PH10_L13-PadL13)") (class "Default")
      (node (ref "U26") (pin "L13") (pinfunction "PH10_L13_L13") (pintype "bidirectional"))
    )
    (net (code "300") (name "unconnected-(U26H-PH11_L12-PadL12)") (class "Default")
      (node (ref "U26") (pin "L12") (pinfunction "PH11_L12_L12") (pintype "bidirectional"))
    )
    (net (code "301") (name "unconnected-(U26H-PH12_K12-PadK12)") (class "Default")
      (node (ref "U26") (pin "K12") (pinfunction "PH12_K12_K12") (pintype "bidirectional"))
    )
    (net (code "302") (name "unconnected-(U26H-PH13_E12-PadE12)") (class "Default")
      (node (ref "U26") (pin "E12") (pinfunction "PH13_E12_E12") (pintype "bidirectional"))
    )
    (net (code "303") (name "unconnected-(U26H-PH14_E13-PadE13)") (class "Default")
      (node (ref "U26") (pin "E13") (pinfunction "PH14_E13_E13") (pintype "bidirectional"))
    )
    (net (code "304") (name "unconnected-(U26H-PH15_D13-PadD13)") (class "Default")
      (node (ref "U26") (pin "D13") (pinfunction "PH15_D13_D13") (pintype "bidirectional"))
    )
    (net (code "305") (name "unconnected-(U26I-PI0_E14-PadE14)") (class "Default")
      (node (ref "U26") (pin "E14") (pinfunction "PI0_E14_E14") (pintype "bidirectional"))
    )
    (net (code "306") (name "unconnected-(U26I-PI1_D14-PadD14)") (class "Default")
      (node (ref "U26") (pin "D14") (pinfunction "PI1_D14_D14") (pintype "bidirectional"))
    )
    (net (code "307") (name "unconnected-(U26I-PI2_C14-PadC14)") (class "Default")
      (node (ref "U26") (pin "C14") (pinfunction "PI2_C14_C14") (pintype "bidirectional"))
    )
    (net (code "308") (name "unconnected-(U26I-PI3_C13-PadC13)") (class "Default")
      (node (ref "U26") (pin "C13") (pinfunction "PI3_C13_C13") (pintype "bidirectional"))
    )
    (net (code "309") (name "unconnected-(U26I-PI4_D4-PadD4)") (class "Default")
      (node (ref "U26") (pin "D4") (pinfunction "PI4_D4_D4") (pintype "bidirectional"))
    )
    (net (code "310") (name "unconnected-(U26I-PI5_C4-PadC4)") (class "Default")
      (node (ref "U26") (pin "C4") (pinfunction "PI5_C4_C4") (pintype "bidirectional"))
    )
    (net (code "311") (name "unconnected-(U26I-PI6_C3-PadC3)") (class "Default")
      (node (ref "U26") (pin "C3") (pinfunction "PI6_C3_C3") (pintype "bidirectional"))
    )
    (net (code "312") (name "unconnected-(U26I-PI7_C2-PadC2)") (class "Default")
      (node (ref "U26") (pin "C2") (pinfunction "PI7_C2_C2") (pintype "bidirectional"))
    )
    (net (code "313") (name "unconnected-(U26I-PI8_D2-PadD2)") (class "Default")
      (node (ref "U26") (pin "D2") (pinfunction "PI8_D2_D2") (pintype "bidirectional"))
    )
    (net (code "314") (name "unconnected-(U26I-PI9_D3-PadD3)") (class "Default")
      (node (ref "U26") (pin "D3") (pinfunction "PI9_D3_D3") (pintype "bidirectional"))
    )
    (net (code "315") (name "unconnected-(U26I-PI10_E3-PadE3)") (class "Default")
      (node (ref "U26") (pin "E3") (pinfunction "PI10_E3_E3") (pintype "bidirectional"))
    )
    (net (code "316") (name "unconnected-(U26I-PI11_E4-PadE4)") (class "Default")
      (node (ref "U26") (pin "E4") (pinfunction "PI11_E4_E4") (pintype "bidirectional"))
    )
  )
)
